# Flexboard.net
KiCad netlist of a schematic drawn in EAGLE
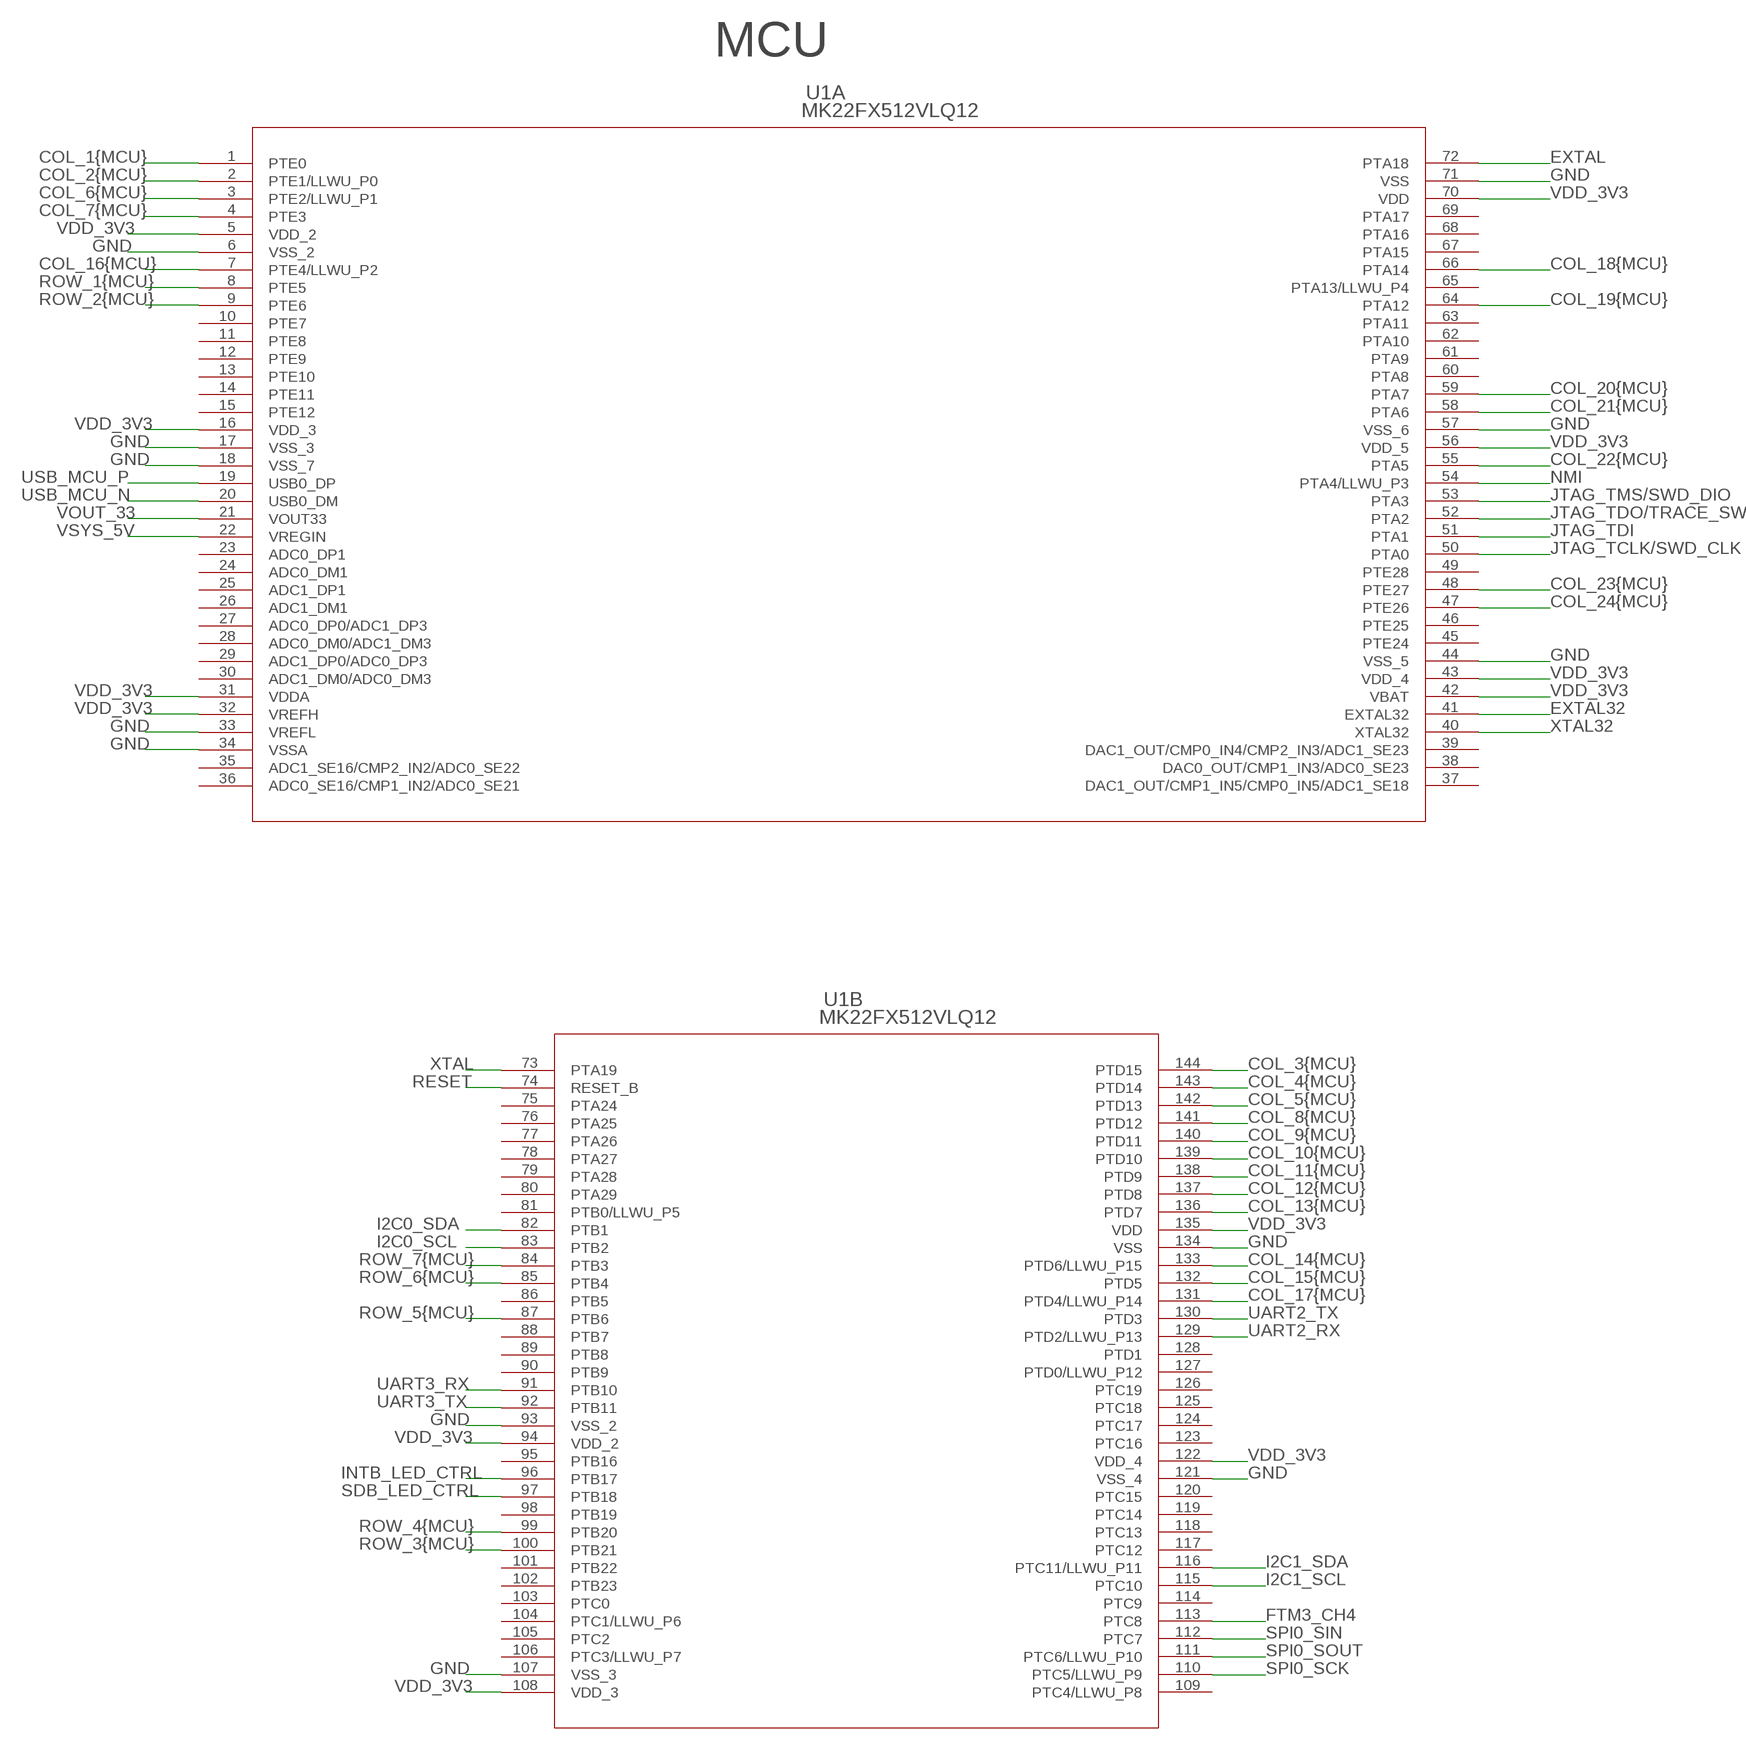
[diagram p0: schematic, sheet 1]
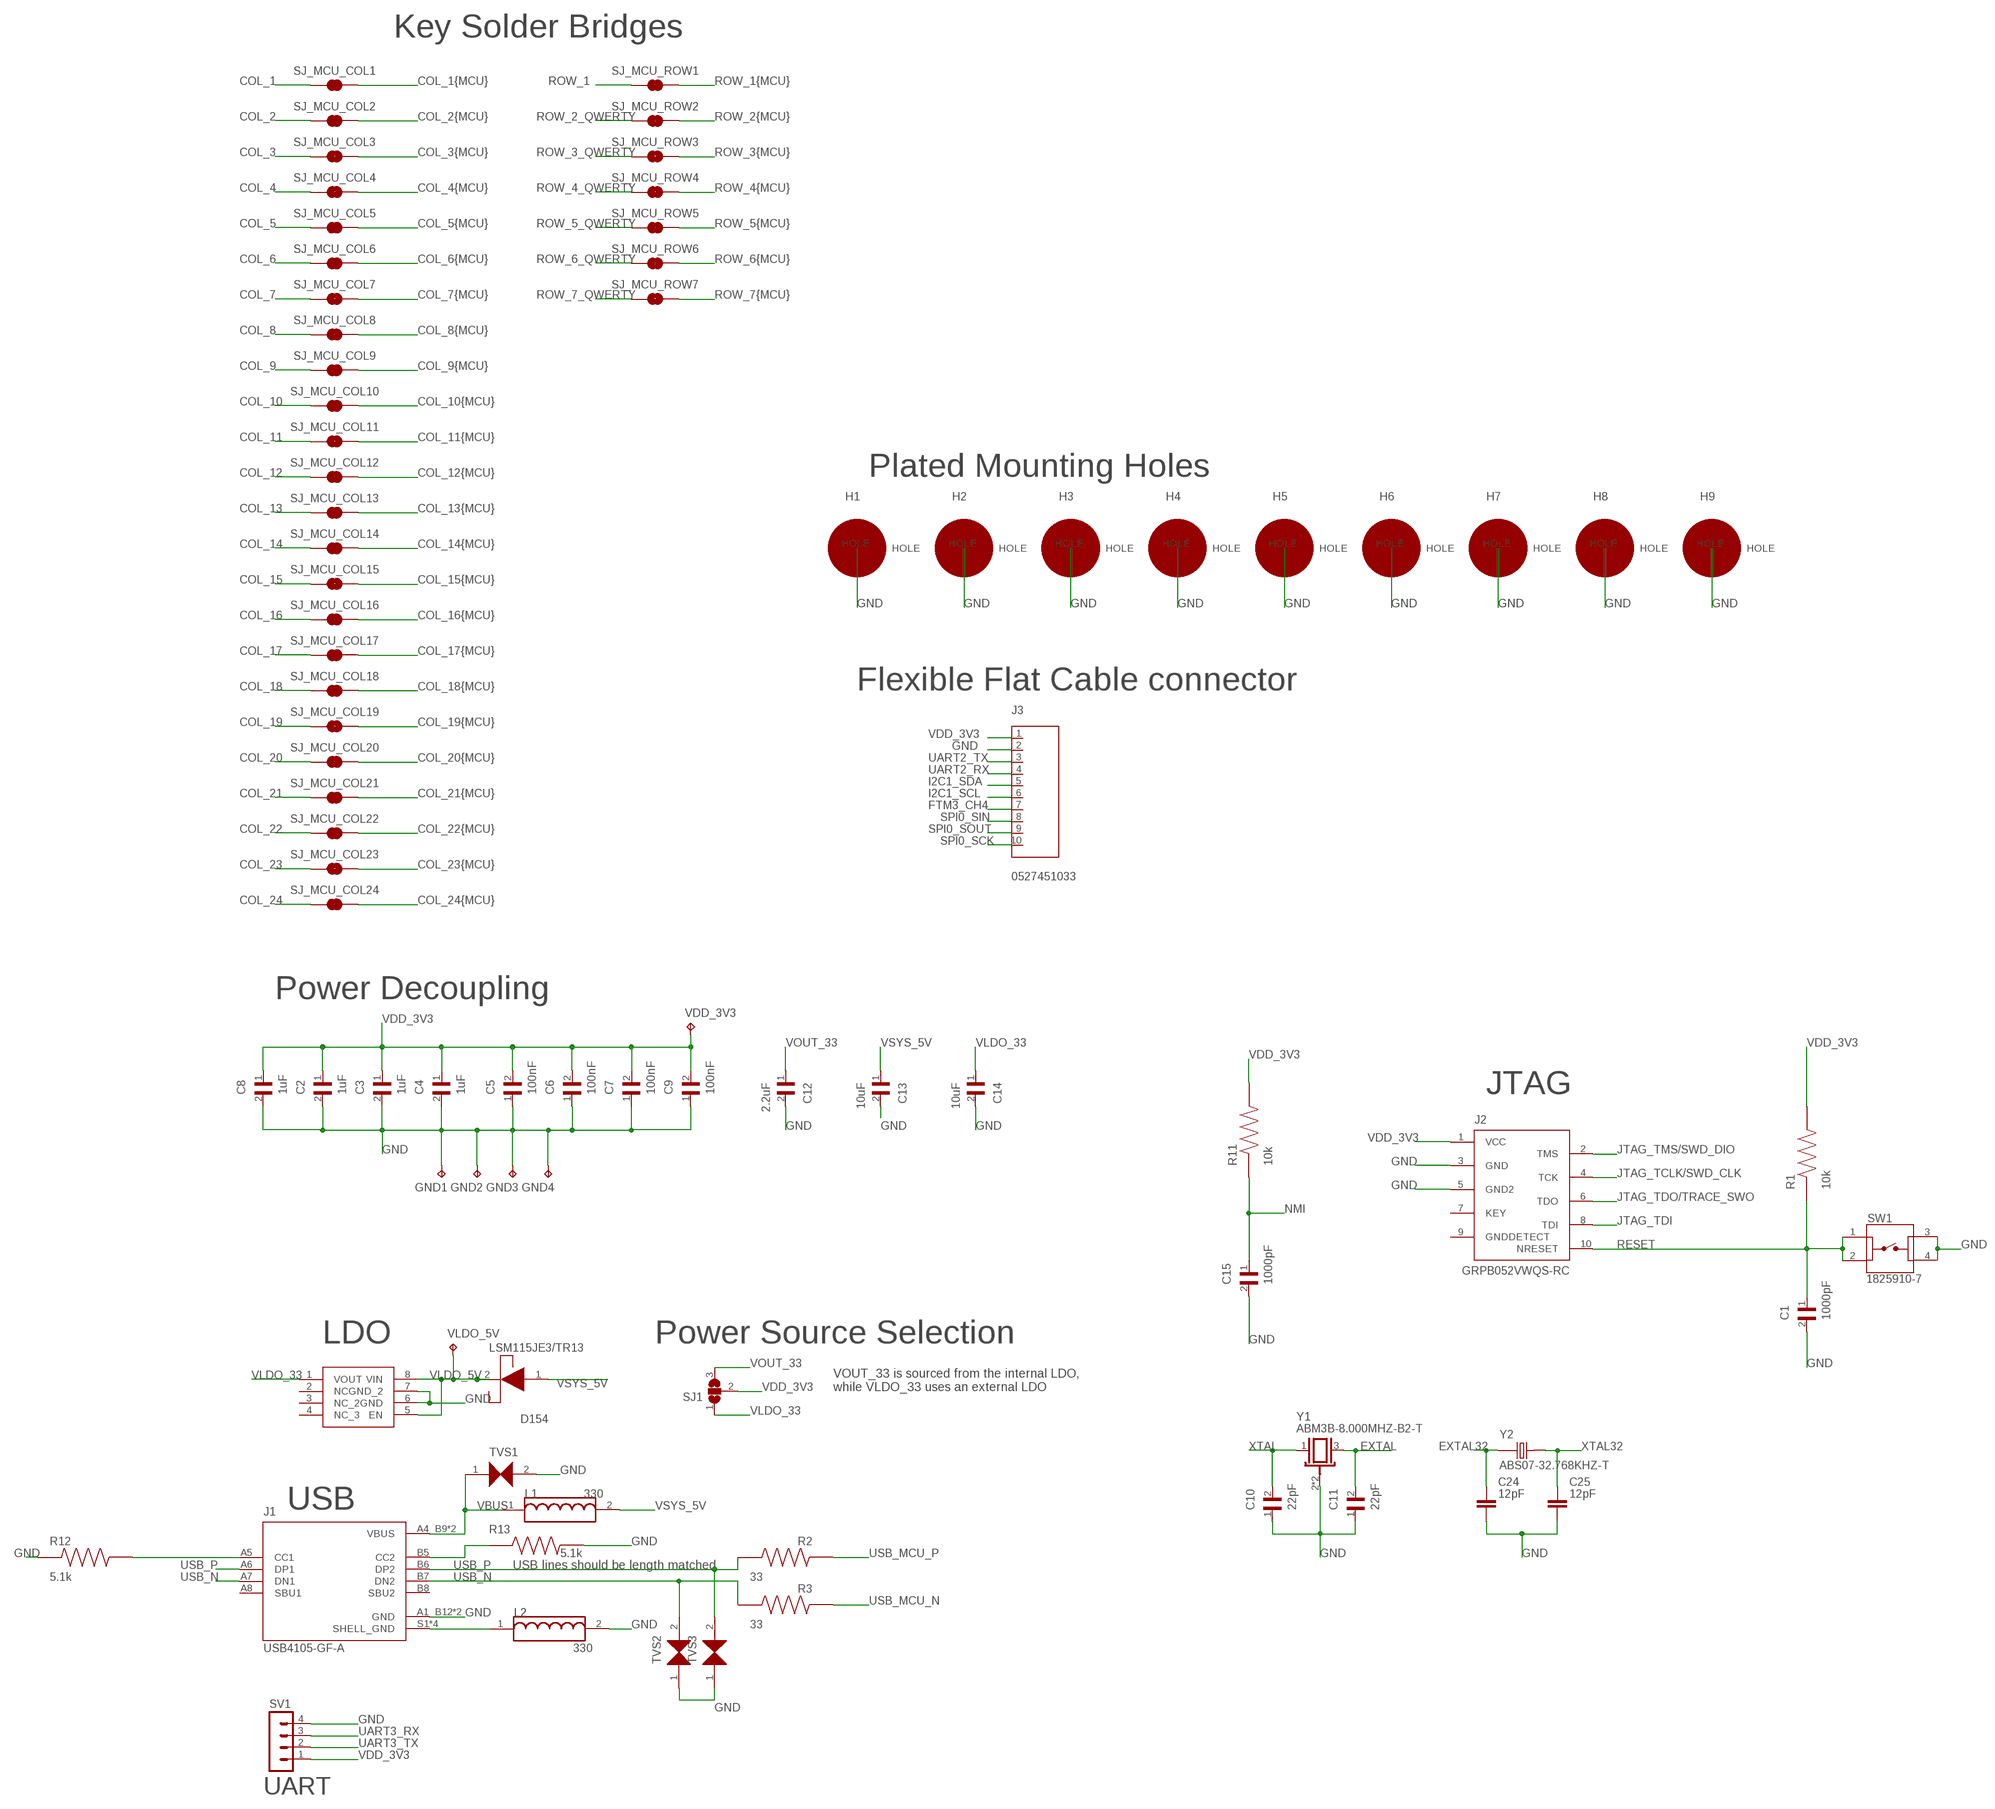
[diagram p1: schematic, sheet 2]
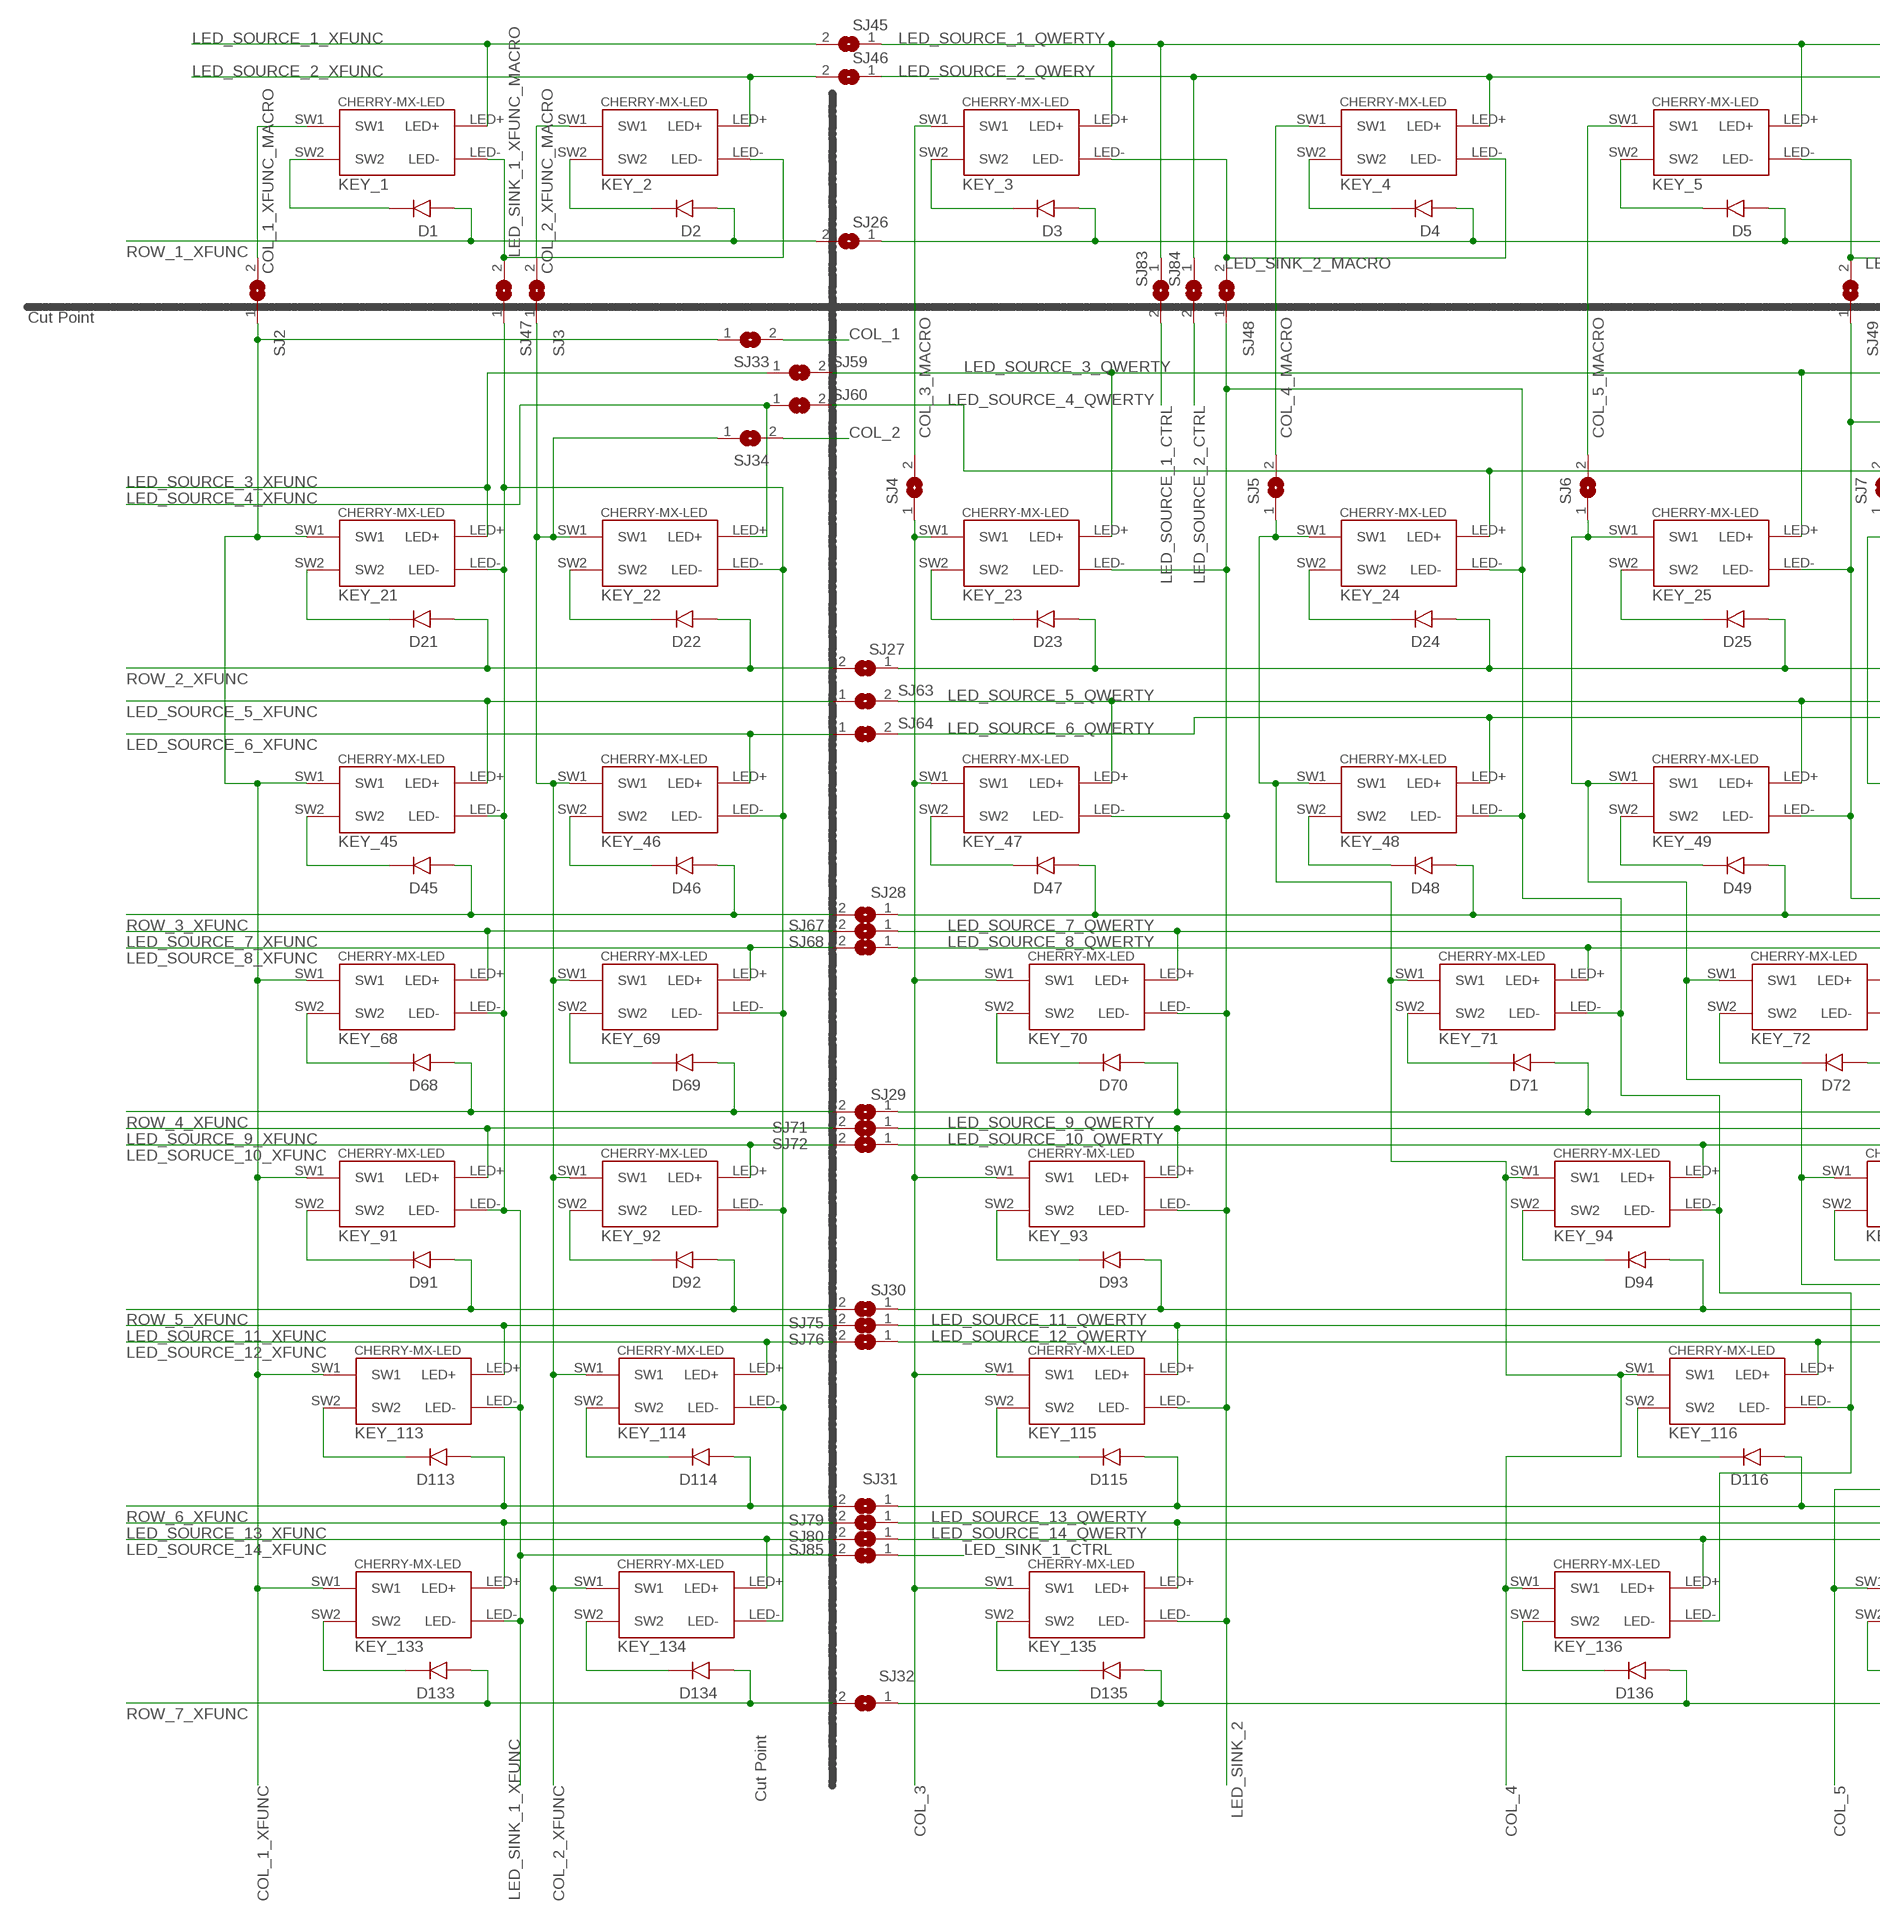
[diagram p2: schematic, sheet 3, part 1 of 3]
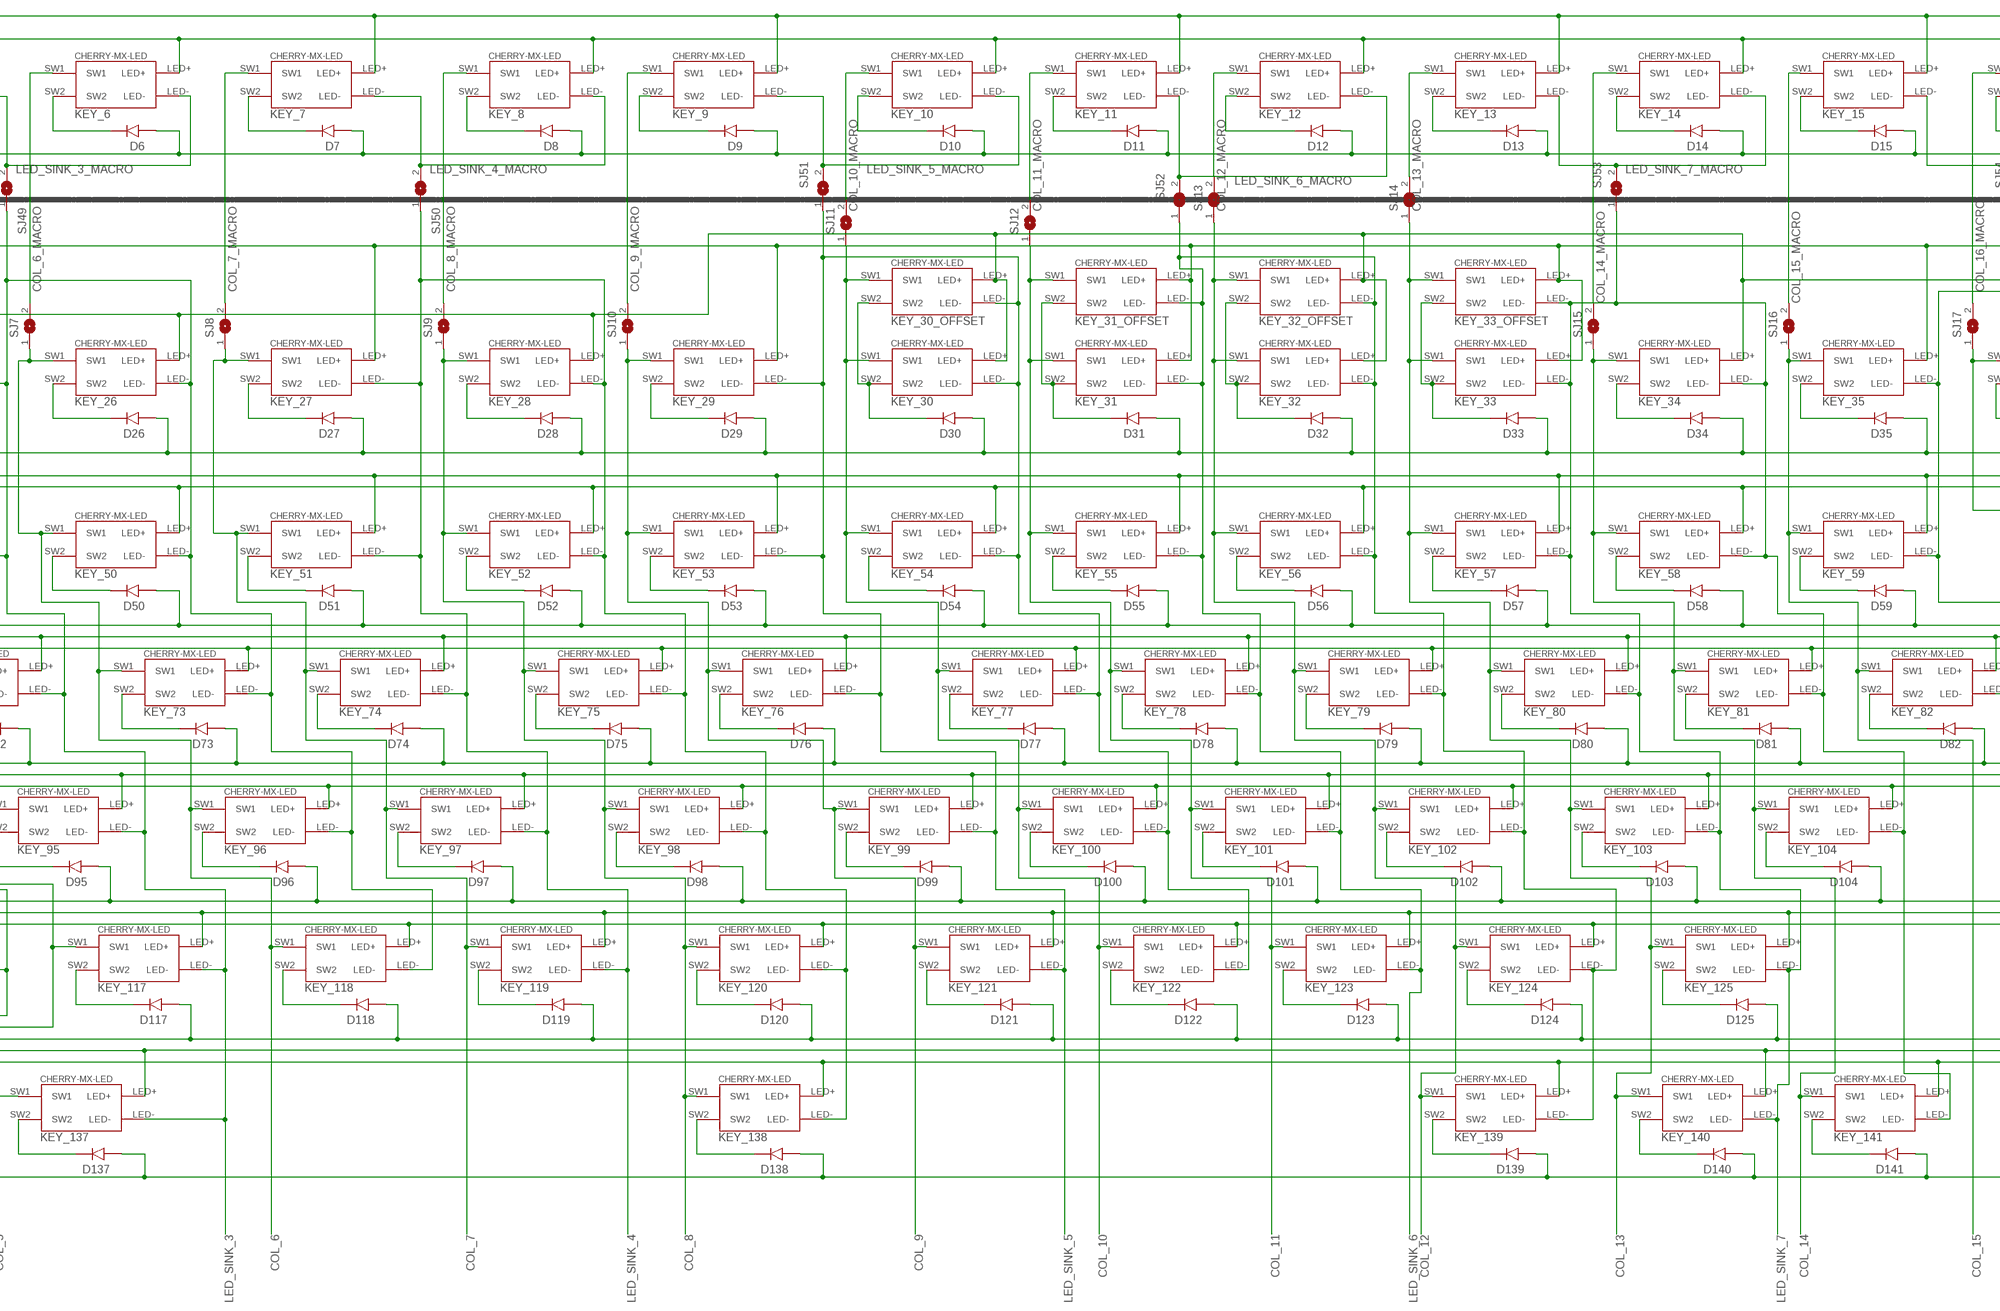
[diagram p3: schematic, sheet 3, part 2 of 3]
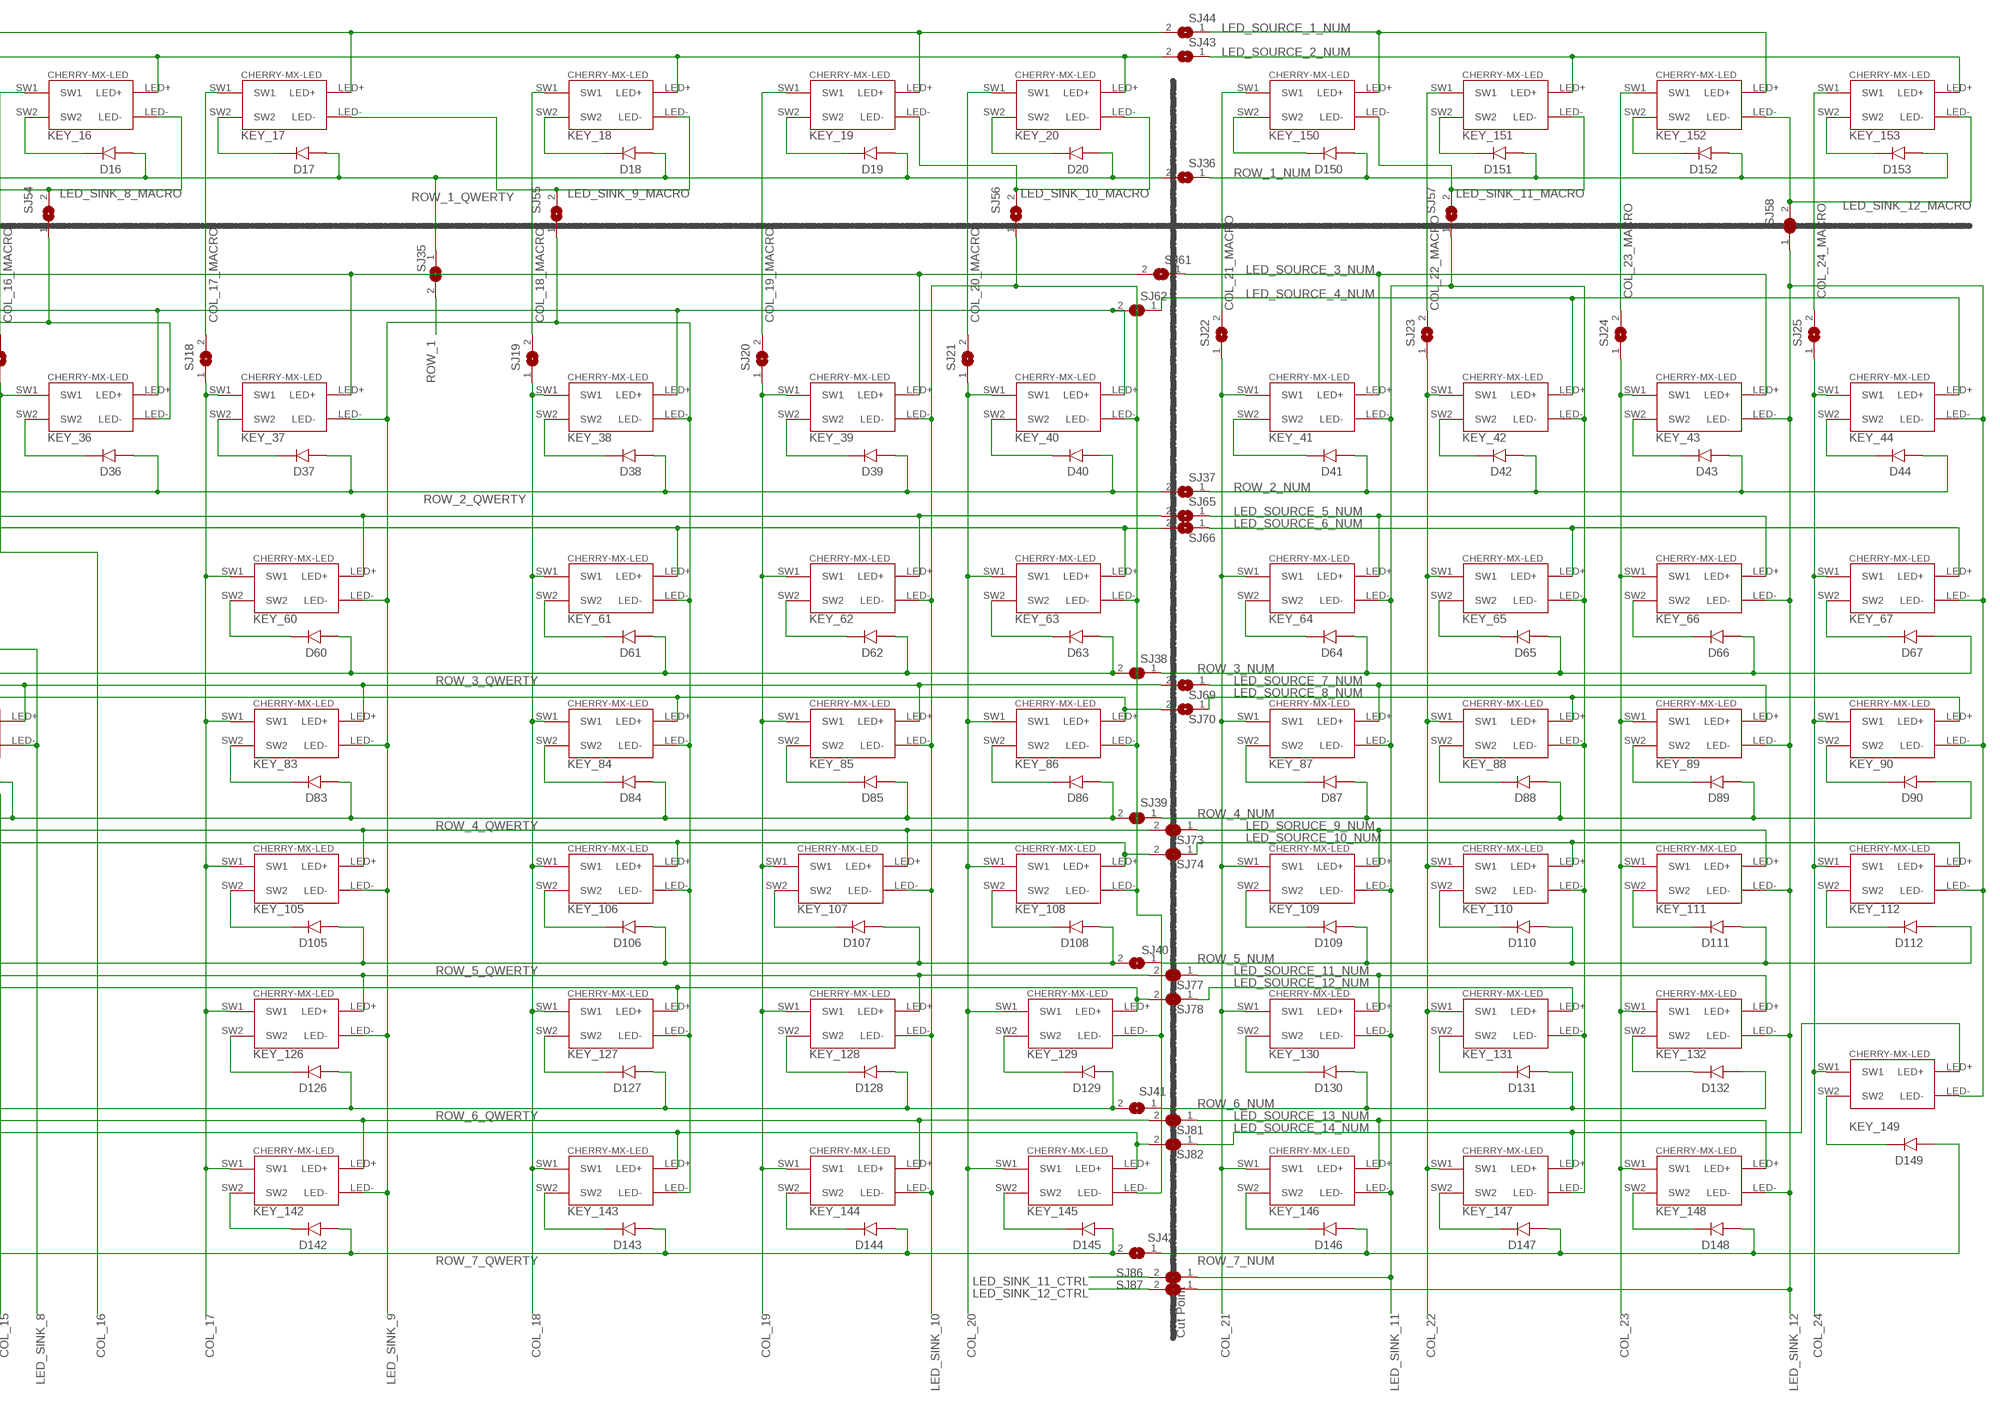
[diagram p4: schematic, sheet 3, part 3 of 3]
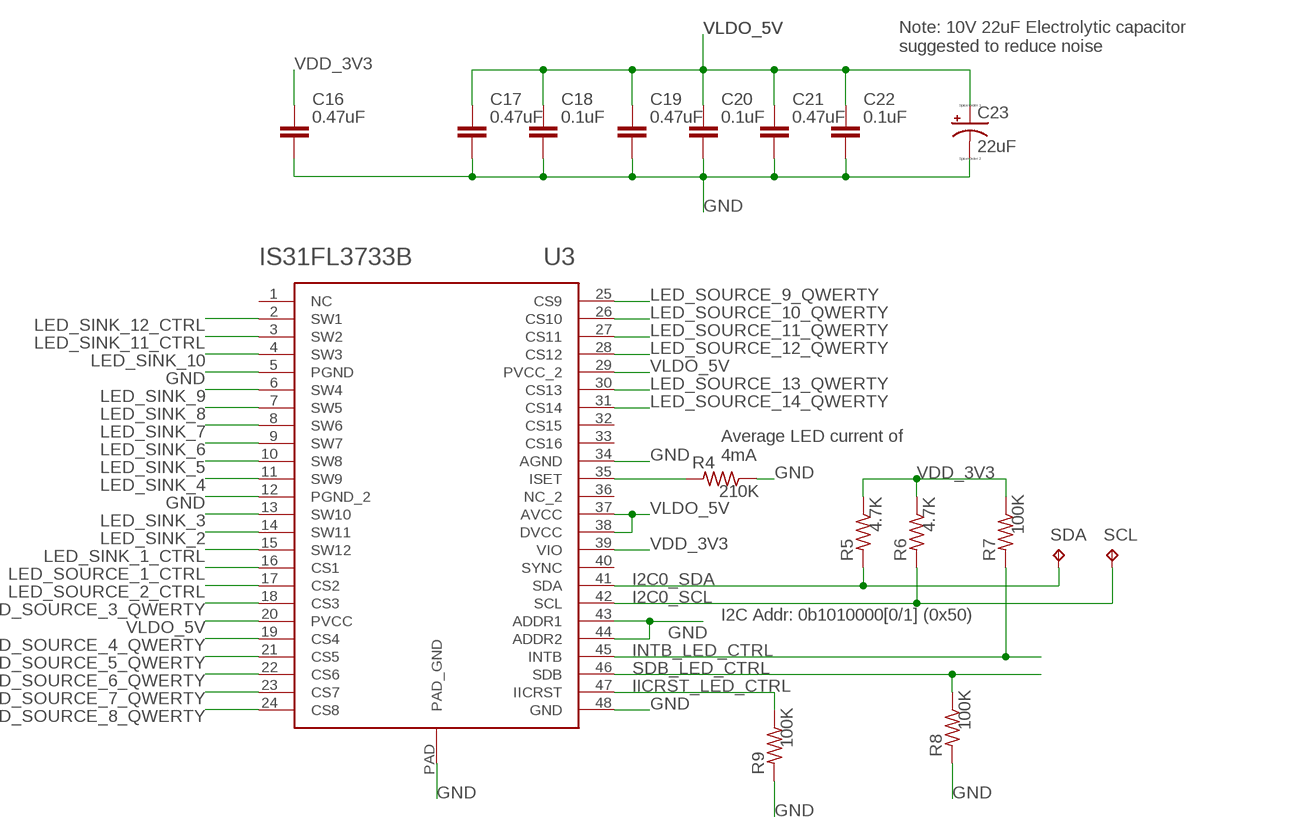
[diagram p5: schematic, sheet 4]

(export (version "E")
  (design (tool "Eeschema 10.0.6"))
  (components
    (comp (ref "C16")
      (value "0.47uF")
      (footprint "eagle-import:CAPC2012X110")
      (libsource (lib "eagle-import") (part "CCHIP-0805(2012-METRIC)_"))
    )
    (comp (ref "C17")
      (value "0.47uF")
      (footprint "eagle-import:CAPC2012X110")
      (libsource (lib "eagle-import") (part "CCHIP-0805(2012-METRIC)_"))
    )
    (comp (ref "C18")
      (value "0.1uF")
      (footprint "eagle-import:CAPC2012X110")
      (libsource (lib "eagle-import") (part "CCHIP-0805(2012-METRIC)_"))
    )
    (comp (ref "C19")
      (value "0.47uF")
      (footprint "eagle-import:CAPC2012X110")
      (libsource (lib "eagle-import") (part "CCHIP-0805(2012-METRIC)_"))
    )
    (comp (ref "C20")
      (value "0.1uF")
      (footprint "eagle-import:CAPC2012X110")
      (libsource (lib "eagle-import") (part "CCHIP-0805(2012-METRIC)_"))
    )
    (comp (ref "C21")
      (value "0.47uF")
      (footprint "eagle-import:CAPC2012X110")
      (libsource (lib "eagle-import") (part "CCHIP-0805(2012-METRIC)_"))
    )
    (comp (ref "C22")
      (value "0.1uF")
      (footprint "eagle-import:CAPC2012X110")
      (libsource (lib "eagle-import") (part "CCHIP-0805(2012-METRIC)_"))
    )
    (comp (ref "C23")
      (value "22uF")
      (footprint "eagle-import:860020672011")
      (libsource (lib "eagle-import") (part "860020672011"))
    )
    (comp (ref "R4")
      (value "210K")
      (footprint "eagle-import:RESC2012X65")
      (libsource (lib "eagle-import") (part "R-USCHIP-0805(2012-METRIC)_"))
    )
    (comp (ref "R5")
      (value "4.7K")
      (footprint "eagle-import:RESC2012X65")
      (libsource (lib "eagle-import") (part "R-USCHIP-0805(2012-METRIC)_"))
    )
    (comp (ref "R6")
      (value "4.7K")
      (footprint "eagle-import:RESC2012X65")
      (libsource (lib "eagle-import") (part "R-USCHIP-0805(2012-METRIC)_"))
    )
    (comp (ref "R7")
      (value "100K")
      (footprint "eagle-import:RESC2012X65")
      (libsource (lib "eagle-import") (part "R-USCHIP-0805(2012-METRIC)_"))
    )
    (comp (ref "R8")
      (value "100K")
      (footprint "eagle-import:RESC2012X65")
      (libsource (lib "eagle-import") (part "R-USCHIP-0805(2012-METRIC)_"))
    )
    (comp (ref "R9")
      (value "100K")
      (footprint "eagle-import:RESC2012X65")
      (libsource (lib "eagle-import") (part "R-USCHIP-0805(2012-METRIC)_"))
    )
    (comp (ref "SCL")
      (value "TPB2,54")
      (footprint "eagle-import:B2,54")
      (libsource (lib "eagle-import") (part "TPB2,54"))
    )
    (comp (ref "SDA")
      (value "TPB2,54")
      (footprint "eagle-import:B2,54")
      (libsource (lib "eagle-import") (part "TPB2,54"))
    )
    (comp (ref "U3")
      (value "IS31FL3733B-TQLS4")
      (footprint "eagle-import:IS31FL3733B-TQLS4")
      (libsource (lib "eagle-import") (part "IS31FL3733B-TQLS4"))
    )
    (comp (ref "C1")
      (value "1000pF")
      (footprint "eagle-import:CAPC3216X110N")
      (fields (field (name "MF") "KEMET") (field (name "MP") "C1206C102K1RACAUTO"))
      (libsource (lib "eagle-import") (part "C1206C102K1RACAUTO"))
    )
    (comp (ref "C2")
      (value "1uF")
      (footprint "eagle-import:CAPC3216X125N")
      (fields (field (name "MF") "Murata") (field (name "MP") "GCM31MR71H105KA55L"))
      (libsource (lib "eagle-import") (part "GCM31MR71H105KA55L"))
    )
    (comp (ref "C3")
      (value "1uF")
      (footprint "eagle-import:CAPC3216X125N")
      (fields (field (name "MF") "Murata") (field (name "MP") "GCM31MR71H105KA55L"))
      (libsource (lib "eagle-import") (part "GCM31MR71H105KA55L"))
    )
    (comp (ref "C4")
      (value "1uF")
      (footprint "eagle-import:CAPC3216X125N")
      (fields (field (name "MF") "Murata") (field (name "MP") "GCM31MR71H105KA55L"))
      (libsource (lib "eagle-import") (part "GCM31MR71H105KA55L"))
    )
    (comp (ref "C5")
      (value "100nF")
      (footprint "eagle-import:CAPC3216X88N")
      (fields (field (name "MF") "KEMET") (field (name "MP") "C1206C104K5RAC7800"))
      (libsource (lib "eagle-import") (part "C1206C104K5RAC7800"))
    )
    (comp (ref "C6")
      (value "100nF")
      (footprint "eagle-import:CAPC3216X88N")
      (fields (field (name "MF") "KEMET") (field (name "MP") "C1206C104K5RAC7800"))
      (libsource (lib "eagle-import") (part "C1206C104K5RAC7800"))
    )
    (comp (ref "C7")
      (value "100nF")
      (footprint "eagle-import:CAPC3216X88N")
      (fields (field (name "MF") "KEMET") (field (name "MP") "C1206C104K5RAC7800"))
      (libsource (lib "eagle-import") (part "C1206C104K5RAC7800"))
    )
    (comp (ref "C8")
      (value "1uF")
      (footprint "eagle-import:CAPC3216X125N")
      (fields (field (name "MF") "Murata") (field (name "MP") "GCM31MR71H105KA55L"))
      (libsource (lib "eagle-import") (part "GCM31MR71H105KA55L"))
    )
    (comp (ref "C9")
      (value "100nF")
      (footprint "eagle-import:CAPC3216X88N")
      (fields (field (name "MF") "KEMET") (field (name "MP") "C1206C104K5RAC7800"))
      (libsource (lib "eagle-import") (part "C1206C104K5RAC7800"))
    )
    (comp (ref "C10")
      (value "22pF")
      (footprint "eagle-import:CAPC3216X110N")
      (fields (field (name "MF") "KEMET") (field (name "MP") "C1206C220JGGAC7800"))
      (libsource (lib "eagle-import") (part "C1206C220JGGAC7800"))
    )
    (comp (ref "C11")
      (value "22pF")
      (footprint "eagle-import:CAPC3216X110N")
      (fields (field (name "MF") "KEMET") (field (name "MP") "C1206C220JGGAC7800"))
      (libsource (lib "eagle-import") (part "C1206C220JGGAC7800"))
    )
    (comp (ref "C12")
      (value "2.2uF")
      (footprint "eagle-import:CAPC3216X178N")
      (fields (field (name "MF") "AVX") (field (name "MP") "1206ZC225MAT2A"))
      (libsource (lib "eagle-import") (part "1206ZC225MAT2A"))
    )
    (comp (ref "C13")
      (value "10uF")
      (footprint "eagle-import:CAPC2012X145N")
      (fields
        (field (name "DIGI-KEY_PART_NUMBER") "490-10505-2-ND")
        (field (name "MF") "Murata")
        (field (name "MP") "GRM21BC8YA106ME11L")
      )
      (libsource (lib "eagle-import") (part "GRM21BC8YA106ME11L"))
    )
    (comp (ref "C14")
      (value "10uF")
      (footprint "eagle-import:CAPC2012X145N")
      (fields
        (field (name "DIGI-KEY_PART_NUMBER") "490-10505-2-ND")
        (field (name "MF") "Murata")
        (field (name "MP") "GRM21BC8YA106ME11L")
      )
      (libsource (lib "eagle-import") (part "GRM21BC8YA106ME11L"))
    )
    (comp (ref "C15")
      (value "1000pF")
      (footprint "eagle-import:CAPC3216X110N")
      (fields (field (name "MF") "KEMET") (field (name "MP") "C1206C102K1RACAUTO"))
      (libsource (lib "eagle-import") (part "C1206C102K1RACAUTO"))
    )
    (comp (ref "C24")
      (value "12pF")
      (footprint "eagle-import:CAPC2012X110")
      (libsource (lib "eagle-import") (part "CCHIP-0805(2012-METRIC)_"))
    )
    (comp (ref "C25")
      (value "12pF")
      (footprint "eagle-import:CAPC2012X110")
      (libsource (lib "eagle-import") (part "CCHIP-0805(2012-METRIC)_"))
    )
    (comp (ref "D154")
      (value "LSM115JE3/TR13")
      (footprint "eagle-import:LSM115JE3_TR13")
      (libsource (lib "eagle-import") (part "LSM115JE3/TR13"))
    )
    (comp (ref "GND1")
      (value "TPB2,54")
      (footprint "eagle-import:B2,54")
      (libsource (lib "eagle-import") (part "TPB2,54"))
    )
    (comp (ref "GND2")
      (value "TPB2,54")
      (footprint "eagle-import:B2,54")
      (libsource (lib "eagle-import") (part "TPB2,54"))
    )
    (comp (ref "GND3")
      (value "TPB2,54")
      (footprint "eagle-import:B2,54")
      (libsource (lib "eagle-import") (part "TPB2,54"))
    )
    (comp (ref "GND4")
      (value "TPB2,54")
      (footprint "eagle-import:B2,54")
      (libsource (lib "eagle-import") (part "TPB2,54"))
    )
    (comp (ref "H1")
      (value "PTH")
      (footprint "eagle-import:PTH")
      (libsource (lib "eagle-import") (part "PTH"))
    )
    (comp (ref "H2")
      (value "PTH")
      (footprint "eagle-import:PTH")
      (libsource (lib "eagle-import") (part "PTH"))
    )
    (comp (ref "H3")
      (value "PTH")
      (footprint "eagle-import:PTH")
      (libsource (lib "eagle-import") (part "PTH"))
    )
    (comp (ref "H4")
      (value "PTH")
      (footprint "eagle-import:PTH")
      (libsource (lib "eagle-import") (part "PTH"))
    )
    (comp (ref "H5")
      (value "PTH")
      (footprint "eagle-import:PTH")
      (libsource (lib "eagle-import") (part "PTH"))
    )
    (comp (ref "H6")
      (value "PTH")
      (footprint "eagle-import:PTH")
      (libsource (lib "eagle-import") (part "PTH"))
    )
    (comp (ref "H7")
      (value "PTH")
      (footprint "eagle-import:PTH")
      (libsource (lib "eagle-import") (part "PTH"))
    )
    (comp (ref "H8")
      (value "PTH")
      (footprint "eagle-import:PTH")
      (libsource (lib "eagle-import") (part "PTH"))
    )
    (comp (ref "H9")
      (value "PTH")
      (footprint "eagle-import:PTH")
      (libsource (lib "eagle-import") (part "PTH"))
    )
    (comp (ref "J1")
      (value "USB4105-GF-A")
      (footprint "eagle-import:GCT_USB4105-GF-A")
      (fields (field (name "MF") "GCT"))
      (libsource (lib "eagle-import") (part "USB4105-GF-A"))
    )
    (comp (ref "J2")
      (value "GRPB052VWQS-RC")
      (footprint "eagle-import:DEBUG")
      (fields (field (name "MF") "Sullins Connector"))
      (libsource (lib "eagle-import") (part "GRPB052VWQS-RC"))
    )
    (comp (ref "J3")
      (value "0527451033")
      (footprint "eagle-import:52745-1033")
      (libsource (lib "eagle-import") (part "0527451033"))
    )
    (comp (ref "L1")
      (value "330")
      (footprint "eagle-import:78285333")
      (libsource (lib "eagle-import") (part "782853331SMD"))
    )
    (comp (ref "L2")
      (value "330")
      (footprint "eagle-import:78285333")
      (libsource (lib "eagle-import") (part "782853331SMD"))
    )
    (comp (ref "R1")
      (value "10k")
      (footprint "eagle-import:RESC3115X65N")
      (fields
        (field (name "COMMENT") "2-2176344-5")
        (field (name "MF") "TE Connectivity")
        (field (name "MP") "CRGCQ1206J10K")
      )
      (libsource (lib "eagle-import") (part "CRGCQ1206J10K"))
    )
    (comp (ref "R2")
      (value "33")
      (footprint "eagle-import:RESC2012X65N")
      (fields
        (field (name "COMMENT") "1623198-1")
        (field (name "MF") "TE Connectivity")
        (field (name "MP") "CRG0805F33R")
      )
      (libsource (lib "eagle-import") (part "CRG0805F33R"))
    )
    (comp (ref "R3")
      (value "33")
      (footprint "eagle-import:RESC2012X65N")
      (fields
        (field (name "COMMENT") "1623198-1")
        (field (name "MF") "TE Connectivity")
        (field (name "MP") "CRG0805F33R")
      )
      (libsource (lib "eagle-import") (part "CRG0805F33R"))
    )
    (comp (ref "R11")
      (value "10k")
      (footprint "eagle-import:RESC3115X65N")
      (fields
        (field (name "COMMENT") "2-2176344-5")
        (field (name "MF") "TE Connectivity")
        (field (name "MP") "CRGCQ1206J10K")
      )
      (libsource (lib "eagle-import") (part "CRGCQ1206J10K"))
    )
    (comp (ref "R12")
      (value "5.1k")
      (footprint "eagle-import:RESC2012X60N")
      (fields (field (name "MF") "Stackpole Electronics Inc") (field (name "MP") "RNCP0805FTD20R0"))
      (libsource (lib "eagle-import") (part "RNCP0805FTD20R0"))
    )
    (comp (ref "R13")
      (value "5.1k")
      (footprint "eagle-import:RESC2012X60N")
      (fields (field (name "MF") "Stackpole Electronics Inc") (field (name "MP") "RNCP0805FTD20R0"))
      (libsource (lib "eagle-import") (part "RNCP0805FTD20R0"))
    )
    (comp (ref "SJ1")
      (value "SJ2W")
      (footprint "eagle-import:SJ_2")
      (libsource (lib "eagle-import") (part "SJ2W"))
    )
    (comp (ref "SJ_MCU_COL1")
      (value "JUMPER-SMT_2_NC_TRACE_NO-SILK")
      (footprint "eagle-import:SMT-JUMPER_2_NC_TRACE_NO-SILK")
      (libsource (lib "eagle-import") (part "JUMPER-SMT_2_NC_TRACE_NO-SILK"))
    )
    (comp (ref "SJ_MCU_COL2")
      (value "JUMPER-SMT_2_NC_TRACE_NO-SILK")
      (footprint "eagle-import:SMT-JUMPER_2_NC_TRACE_NO-SILK")
      (libsource (lib "eagle-import") (part "JUMPER-SMT_2_NC_TRACE_NO-SILK"))
    )
    (comp (ref "SJ_MCU_COL3")
      (value "JUMPER-SMT_2_NC_TRACE_NO-SILK")
      (footprint "eagle-import:SMT-JUMPER_2_NC_TRACE_NO-SILK")
      (libsource (lib "eagle-import") (part "JUMPER-SMT_2_NC_TRACE_NO-SILK"))
    )
    (comp (ref "SJ_MCU_COL4")
      (value "JUMPER-SMT_2_NC_TRACE_NO-SILK")
      (footprint "eagle-import:SMT-JUMPER_2_NC_TRACE_NO-SILK")
      (libsource (lib "eagle-import") (part "JUMPER-SMT_2_NC_TRACE_NO-SILK"))
    )
    (comp (ref "SJ_MCU_COL5")
      (value "JUMPER-SMT_2_NC_TRACE_NO-SILK")
      (footprint "eagle-import:SMT-JUMPER_2_NC_TRACE_NO-SILK")
      (libsource (lib "eagle-import") (part "JUMPER-SMT_2_NC_TRACE_NO-SILK"))
    )
    (comp (ref "SJ_MCU_COL6")
      (value "JUMPER-SMT_2_NC_TRACE_NO-SILK")
      (footprint "eagle-import:SMT-JUMPER_2_NC_TRACE_NO-SILK")
      (libsource (lib "eagle-import") (part "JUMPER-SMT_2_NC_TRACE_NO-SILK"))
    )
    (comp (ref "SJ_MCU_COL7")
      (value "JUMPER-SMT_2_NC_TRACE_NO-SILK")
      (footprint "eagle-import:SMT-JUMPER_2_NC_TRACE_NO-SILK")
      (libsource (lib "eagle-import") (part "JUMPER-SMT_2_NC_TRACE_NO-SILK"))
    )
    (comp (ref "SJ_MCU_COL8")
      (value "JUMPER-SMT_2_NC_TRACE_NO-SILK")
      (footprint "eagle-import:SMT-JUMPER_2_NC_TRACE_NO-SILK")
      (libsource (lib "eagle-import") (part "JUMPER-SMT_2_NC_TRACE_NO-SILK"))
    )
    (comp (ref "SJ_MCU_COL9")
      (value "JUMPER-SMT_2_NC_TRACE_NO-SILK")
      (footprint "eagle-import:SMT-JUMPER_2_NC_TRACE_NO-SILK")
      (libsource (lib "eagle-import") (part "JUMPER-SMT_2_NC_TRACE_NO-SILK"))
    )
    (comp (ref "SJ_MCU_COL10")
      (value "JUMPER-SMT_2_NC_TRACE_NO-SILK")
      (footprint "eagle-import:SMT-JUMPER_2_NC_TRACE_NO-SILK")
      (libsource (lib "eagle-import") (part "JUMPER-SMT_2_NC_TRACE_NO-SILK"))
    )
    (comp (ref "SJ_MCU_COL11")
      (value "JUMPER-SMT_2_NC_TRACE_NO-SILK")
      (footprint "eagle-import:SMT-JUMPER_2_NC_TRACE_NO-SILK")
      (libsource (lib "eagle-import") (part "JUMPER-SMT_2_NC_TRACE_NO-SILK"))
    )
    (comp (ref "SJ_MCU_COL12")
      (value "JUMPER-SMT_2_NC_TRACE_NO-SILK")
      (footprint "eagle-import:SMT-JUMPER_2_NC_TRACE_NO-SILK")
      (libsource (lib "eagle-import") (part "JUMPER-SMT_2_NC_TRACE_NO-SILK"))
    )
    (comp (ref "SJ_MCU_COL13")
      (value "JUMPER-SMT_2_NC_TRACE_NO-SILK")
      (footprint "eagle-import:SMT-JUMPER_2_NC_TRACE_NO-SILK")
      (libsource (lib "eagle-import") (part "JUMPER-SMT_2_NC_TRACE_NO-SILK"))
    )
    (comp (ref "SJ_MCU_COL14")
      (value "JUMPER-SMT_2_NC_TRACE_NO-SILK")
      (footprint "eagle-import:SMT-JUMPER_2_NC_TRACE_NO-SILK")
      (libsource (lib "eagle-import") (part "JUMPER-SMT_2_NC_TRACE_NO-SILK"))
    )
    (comp (ref "SJ_MCU_COL15")
      (value "JUMPER-SMT_2_NC_TRACE_NO-SILK")
      (footprint "eagle-import:SMT-JUMPER_2_NC_TRACE_NO-SILK")
      (libsource (lib "eagle-import") (part "JUMPER-SMT_2_NC_TRACE_NO-SILK"))
    )
    (comp (ref "SJ_MCU_COL16")
      (value "JUMPER-SMT_2_NC_TRACE_NO-SILK")
      (footprint "eagle-import:SMT-JUMPER_2_NC_TRACE_NO-SILK")
      (libsource (lib "eagle-import") (part "JUMPER-SMT_2_NC_TRACE_NO-SILK"))
    )
    (comp (ref "SJ_MCU_COL17")
      (value "JUMPER-SMT_2_NC_TRACE_NO-SILK")
      (footprint "eagle-import:SMT-JUMPER_2_NC_TRACE_NO-SILK")
      (libsource (lib "eagle-import") (part "JUMPER-SMT_2_NC_TRACE_NO-SILK"))
    )
    (comp (ref "SJ_MCU_COL18")
      (value "JUMPER-SMT_2_NC_TRACE_NO-SILK")
      (footprint "eagle-import:SMT-JUMPER_2_NC_TRACE_NO-SILK")
      (libsource (lib "eagle-import") (part "JUMPER-SMT_2_NC_TRACE_NO-SILK"))
    )
    (comp (ref "SJ_MCU_COL19")
      (value "JUMPER-SMT_2_NC_TRACE_NO-SILK")
      (footprint "eagle-import:SMT-JUMPER_2_NC_TRACE_NO-SILK")
      (libsource (lib "eagle-import") (part "JUMPER-SMT_2_NC_TRACE_NO-SILK"))
    )
    (comp (ref "SJ_MCU_COL20")
      (value "JUMPER-SMT_2_NC_TRACE_NO-SILK")
      (footprint "eagle-import:SMT-JUMPER_2_NC_TRACE_NO-SILK")
      (libsource (lib "eagle-import") (part "JUMPER-SMT_2_NC_TRACE_NO-SILK"))
    )
    (comp (ref "SJ_MCU_COL21")
      (value "JUMPER-SMT_2_NC_TRACE_NO-SILK")
      (footprint "eagle-import:SMT-JUMPER_2_NC_TRACE_NO-SILK")
      (libsource (lib "eagle-import") (part "JUMPER-SMT_2_NC_TRACE_NO-SILK"))
    )
    (comp (ref "SJ_MCU_COL22")
      (value "JUMPER-SMT_2_NC_TRACE_NO-SILK")
      (footprint "eagle-import:SMT-JUMPER_2_NC_TRACE_NO-SILK")
      (libsource (lib "eagle-import") (part "JUMPER-SMT_2_NC_TRACE_NO-SILK"))
    )
    (comp (ref "SJ_MCU_COL23")
      (value "JUMPER-SMT_2_NC_TRACE_NO-SILK")
      (footprint "eagle-import:SMT-JUMPER_2_NC_TRACE_NO-SILK")
      (libsource (lib "eagle-import") (part "JUMPER-SMT_2_NC_TRACE_NO-SILK"))
    )
    (comp (ref "SJ_MCU_COL24")
      (value "JUMPER-SMT_2_NC_TRACE_NO-SILK")
      (footprint "eagle-import:SMT-JUMPER_2_NC_TRACE_NO-SILK")
      (libsource (lib "eagle-import") (part "JUMPER-SMT_2_NC_TRACE_NO-SILK"))
    )
    (comp (ref "SJ_MCU_ROW1")
      (value "JUMPER-SMT_2_NC_TRACE_NO-SILK")
      (footprint "eagle-import:SMT-JUMPER_2_NC_TRACE_NO-SILK")
      (libsource (lib "eagle-import") (part "JUMPER-SMT_2_NC_TRACE_NO-SILK"))
    )
    (comp (ref "SJ_MCU_ROW2")
      (value "JUMPER-SMT_2_NC_TRACE_NO-SILK")
      (footprint "eagle-import:SMT-JUMPER_2_NC_TRACE_NO-SILK")
      (libsource (lib "eagle-import") (part "JUMPER-SMT_2_NC_TRACE_NO-SILK"))
    )
    (comp (ref "SJ_MCU_ROW3")
      (value "JUMPER-SMT_2_NC_TRACE_NO-SILK")
      (footprint "eagle-import:SMT-JUMPER_2_NC_TRACE_NO-SILK")
      (libsource (lib "eagle-import") (part "JUMPER-SMT_2_NC_TRACE_NO-SILK"))
    )
    (comp (ref "SJ_MCU_ROW4")
      (value "JUMPER-SMT_2_NC_TRACE_NO-SILK")
      (footprint "eagle-import:SMT-JUMPER_2_NC_TRACE_NO-SILK")
      (libsource (lib "eagle-import") (part "JUMPER-SMT_2_NC_TRACE_NO-SILK"))
    )
    (comp (ref "SJ_MCU_ROW5")
      (value "JUMPER-SMT_2_NC_TRACE_NO-SILK")
      (footprint "eagle-import:SMT-JUMPER_2_NC_TRACE_NO-SILK")
      (libsource (lib "eagle-import") (part "JUMPER-SMT_2_NC_TRACE_NO-SILK"))
    )
    (comp (ref "SJ_MCU_ROW6")
      (value "JUMPER-SMT_2_NC_TRACE_NO-SILK")
      (footprint "eagle-import:SMT-JUMPER_2_NC_TRACE_NO-SILK")
      (libsource (lib "eagle-import") (part "JUMPER-SMT_2_NC_TRACE_NO-SILK"))
    )
    (comp (ref "SJ_MCU_ROW7")
      (value "JUMPER-SMT_2_NC_TRACE_NO-SILK")
      (footprint "eagle-import:SMT-JUMPER_2_NC_TRACE_NO-SILK")
      (libsource (lib "eagle-import") (part "JUMPER-SMT_2_NC_TRACE_NO-SILK"))
    )
    (comp (ref "SV1")
      (value "MA04-1")
      (footprint "eagle-import:MA04-1")
      (libsource (lib "eagle-import") (part "MA04-1"))
    )
    (comp (ref "SW1")
      (value "1825910-7")
      (footprint "eagle-import:SW_1825910-7")
      (fields (field (name "MF") "TE Connectivity"))
      (libsource (lib "eagle-import") (part "1825910-7"))
    )
    (comp (ref "TVS1")
      (value "0603ESDA2-TR2")
      (footprint "eagle-import:0603ESDA2-TR2")
      (libsource (lib "eagle-import") (part "0603ESDA2-TR2"))
    )
    (comp (ref "TVS2")
      (value "0603ESDA2-TR2")
      (footprint "eagle-import:0603ESDA2-TR2")
      (libsource (lib "eagle-import") (part "0603ESDA2-TR2"))
    )
    (comp (ref "TVS3")
      (value "0603ESDA2-TR2")
      (footprint "eagle-import:0603ESDA2-TR2")
      (libsource (lib "eagle-import") (part "0603ESDA2-TR2"))
    )
    (comp (ref "U2")
      (value "AP2115M-3.3TRG1")
      (footprint "eagle-import:SOIC127P600X175-8N")
      (libsource (lib "eagle-import") (part "AP2115M-3.3TRG1"))
    )
    (comp (ref "VDD_3V3")
      (value "TPB2,54")
      (footprint "eagle-import:B2,54")
      (libsource (lib "eagle-import") (part "TPB2,54"))
    )
    (comp (ref "VLDO_5V")
      (value "TPB2,54")
      (footprint "eagle-import:B2,54")
      (libsource (lib "eagle-import") (part "TPB2,54"))
    )
    (comp (ref "Y1")
      (value "ABM3B-8.000MHZ-B2-T")
      (footprint "eagle-import:OSC_ABM3B-8.000MHZ-B2-T")
      (fields (field (name "MF") "Abracon"))
      (libsource (lib "eagle-import") (part "ABM3B-8.000MHZ-B2-T"))
    )
    (comp (ref "Y2")
      (value "ABS07-32.768KHZ-T")
      (footprint "eagle-import:XTAL_ABS07-32.768KHZ-T")
      (fields (field (name "MF") "Abracon"))
      (libsource (lib "eagle-import") (part "ABS07-32.768KHZ-T"))
    )
    (comp (ref "U1")
      (value "MK22FX512VLQ12")
      (footprint "eagle-import:LQFP-144_20X20X1.6")
      (fields (field (name "MANUFACTURER_PART_NUMBER") "MK22FX512AVLQ12"))
      (libsource (lib "eagle-import") (part "MK22FX512AVLQ12"))
    )
    (comp (ref "D1")
      (value "BAS16LT3G")
      (footprint "eagle-import:SOT95P240X111-3N")
      (fields (field (name "MF") "ON Semiconductor"))
      (libsource (lib "eagle-import") (part "BAS16LT3G"))
    )
    (comp (ref "D2")
      (value "BAS16LT3G")
      (footprint "eagle-import:SOT95P240X111-3N")
      (fields (field (name "MF") "ON Semiconductor"))
      (libsource (lib "eagle-import") (part "BAS16LT3G"))
    )
    (comp (ref "D3")
      (value "BAS16LT3G")
      (footprint "eagle-import:SOT95P240X111-3N")
      (fields (field (name "MF") "ON Semiconductor"))
      (libsource (lib "eagle-import") (part "BAS16LT3G"))
    )
    (comp (ref "D4")
      (value "BAS16LT3G")
      (footprint "eagle-import:SOT95P240X111-3N")
      (fields (field (name "MF") "ON Semiconductor"))
      (libsource (lib "eagle-import") (part "BAS16LT3G"))
    )
    (comp (ref "D5")
      (value "BAS16LT3G")
      (footprint "eagle-import:SOT95P240X111-3N")
      (fields (field (name "MF") "ON Semiconductor"))
      (libsource (lib "eagle-import") (part "BAS16LT3G"))
    )
    (comp (ref "D6")
      (value "BAS16LT3G")
      (footprint "eagle-import:SOT95P240X111-3N")
      (fields (field (name "MF") "ON Semiconductor"))
      (libsource (lib "eagle-import") (part "BAS16LT3G"))
    )
    (comp (ref "D7")
      (value "BAS16LT3G")
      (footprint "eagle-import:SOT95P240X111-3N")
      (fields (field (name "MF") "ON Semiconductor"))
      (libsource (lib "eagle-import") (part "BAS16LT3G"))
    )
    (comp (ref "D8")
      (value "BAS16LT3G")
      (footprint "eagle-import:SOT95P240X111-3N")
      (fields (field (name "MF") "ON Semiconductor"))
      (libsource (lib "eagle-import") (part "BAS16LT3G"))
    )
    (comp (ref "D9")
      (value "BAS16LT3G")
      (footprint "eagle-import:SOT95P240X111-3N")
      (fields (field (name "MF") "ON Semiconductor"))
      (libsource (lib "eagle-import") (part "BAS16LT3G"))
    )
    (comp (ref "D10")
      (value "BAS16LT3G")
      (footprint "eagle-import:SOT95P240X111-3N")
      (fields (field (name "MF") "ON Semiconductor"))
      (libsource (lib "eagle-import") (part "BAS16LT3G"))
    )
    (comp (ref "D11")
      (value "BAS16LT3G")
      (footprint "eagle-import:SOT95P240X111-3N")
      (fields (field (name "MF") "ON Semiconductor"))
      (libsource (lib "eagle-import") (part "BAS16LT3G"))
    )
    (comp (ref "D12")
      (value "BAS16LT3G")
      (footprint "eagle-import:SOT95P240X111-3N")
      (fields (field (name "MF") "ON Semiconductor"))
      (libsource (lib "eagle-import") (part "BAS16LT3G"))
    )
    (comp (ref "D13")
      (value "BAS16LT3G")
      (footprint "eagle-import:SOT95P240X111-3N")
      (fields (field (name "MF") "ON Semiconductor"))
      (libsource (lib "eagle-import") (part "BAS16LT3G"))
    )
    (comp (ref "D14")
      (value "BAS16LT3G")
      (footprint "eagle-import:SOT95P240X111-3N")
      (fields (field (name "MF") "ON Semiconductor"))
      (libsource (lib "eagle-import") (part "BAS16LT3G"))
    )
    (comp (ref "D15")
      (value "BAS16LT3G")
      (footprint "eagle-import:SOT95P240X111-3N")
      (fields (field (name "MF") "ON Semiconductor"))
      (libsource (lib "eagle-import") (part "BAS16LT3G"))
    )
    (comp (ref "D16")
      (value "BAS16LT3G")
      (footprint "eagle-import:SOT95P240X111-3N")
      (fields (field (name "MF") "ON Semiconductor"))
      (libsource (lib "eagle-import") (part "BAS16LT3G"))
    )
    (comp (ref "D17")
      (value "BAS16LT3G")
      (footprint "eagle-import:SOT95P240X111-3N")
      (fields (field (name "MF") "ON Semiconductor"))
      (libsource (lib "eagle-import") (part "BAS16LT3G"))
    )
    (comp (ref "D18")
      (value "BAS16LT3G")
      (footprint "eagle-import:SOT95P240X111-3N")
      (fields (field (name "MF") "ON Semiconductor"))
      (libsource (lib "eagle-import") (part "BAS16LT3G"))
    )
    (comp (ref "D19")
      (value "BAS16LT3G")
      (footprint "eagle-import:SOT95P240X111-3N")
      (fields (field (name "MF") "ON Semiconductor"))
      (libsource (lib "eagle-import") (part "BAS16LT3G"))
    )
    (comp (ref "D20")
      (value "BAS16LT3G")
      (footprint "eagle-import:SOT95P240X111-3N")
      (fields (field (name "MF") "ON Semiconductor"))
      (libsource (lib "eagle-import") (part "BAS16LT3G"))
    )
    (comp (ref "D21")
      (value "BAS16LT3G")
      (footprint "eagle-import:SOT95P240X111-3N")
      (fields (field (name "MF") "ON Semiconductor"))
      (libsource (lib "eagle-import") (part "BAS16LT3G"))
    )
    (comp (ref "D22")
      (value "BAS16LT3G")
      (footprint "eagle-import:SOT95P240X111-3N")
      (fields (field (name "MF") "ON Semiconductor"))
      (libsource (lib "eagle-import") (part "BAS16LT3G"))
    )
    (comp (ref "D23")
      (value "BAS16LT3G")
      (footprint "eagle-import:SOT95P240X111-3N")
      (fields (field (name "MF") "ON Semiconductor"))
      (libsource (lib "eagle-import") (part "BAS16LT3G"))
    )
    (comp (ref "D24")
      (value "BAS16LT3G")
      (footprint "eagle-import:SOT95P240X111-3N")
      (fields (field (name "MF") "ON Semiconductor"))
      (libsource (lib "eagle-import") (part "BAS16LT3G"))
    )
    (comp (ref "D25")
      (value "BAS16LT3G")
      (footprint "eagle-import:SOT95P240X111-3N")
      (fields (field (name "MF") "ON Semiconductor"))
      (libsource (lib "eagle-import") (part "BAS16LT3G"))
    )
    (comp (ref "D26")
      (value "BAS16LT3G")
      (footprint "eagle-import:SOT95P240X111-3N")
      (fields (field (name "MF") "ON Semiconductor"))
      (libsource (lib "eagle-import") (part "BAS16LT3G"))
    )
    (comp (ref "D27")
      (value "BAS16LT3G")
      (footprint "eagle-import:SOT95P240X111-3N")
      (fields (field (name "MF") "ON Semiconductor"))
      (libsource (lib "eagle-import") (part "BAS16LT3G"))
    )
    (comp (ref "D28")
      (value "BAS16LT3G")
      (footprint "eagle-import:SOT95P240X111-3N")
      (fields (field (name "MF") "ON Semiconductor"))
      (libsource (lib "eagle-import") (part "BAS16LT3G"))
    )
    (comp (ref "D29")
      (value "BAS16LT3G")
      (footprint "eagle-import:SOT95P240X111-3N")
      (fields (field (name "MF") "ON Semiconductor"))
      (libsource (lib "eagle-import") (part "BAS16LT3G"))
    )
    (comp (ref "D30")
      (value "BAS16LT3G")
      (footprint "eagle-import:SOT95P240X111-3N")
      (fields (field (name "MF") "ON Semiconductor"))
      (libsource (lib "eagle-import") (part "BAS16LT3G"))
    )
    (comp (ref "D31")
      (value "BAS16LT3G")
      (footprint "eagle-import:SOT95P240X111-3N")
      (fields (field (name "MF") "ON Semiconductor"))
      (libsource (lib "eagle-import") (part "BAS16LT3G"))
    )
    (comp (ref "D32")
      (value "BAS16LT3G")
      (footprint "eagle-import:SOT95P240X111-3N")
      (fields (field (name "MF") "ON Semiconductor"))
      (libsource (lib "eagle-import") (part "BAS16LT3G"))
    )
    (comp (ref "D33")
      (value "BAS16LT3G")
      (footprint "eagle-import:SOT95P240X111-3N")
      (fields (field (name "MF") "ON Semiconductor"))
      (libsource (lib "eagle-import") (part "BAS16LT3G"))
    )
    (comp (ref "D34")
      (value "BAS16LT3G")
      (footprint "eagle-import:SOT95P240X111-3N")
      (fields (field (name "MF") "ON Semiconductor"))
      (libsource (lib "eagle-import") (part "BAS16LT3G"))
    )
    (comp (ref "D35")
      (value "BAS16LT3G")
      (footprint "eagle-import:SOT95P240X111-3N")
      (fields (field (name "MF") "ON Semiconductor"))
      (libsource (lib "eagle-import") (part "BAS16LT3G"))
    )
    (comp (ref "D36")
      (value "BAS16LT3G")
      (footprint "eagle-import:SOT95P240X111-3N")
      (fields (field (name "MF") "ON Semiconductor"))
      (libsource (lib "eagle-import") (part "BAS16LT3G"))
    )
    (comp (ref "D37")
      (value "BAS16LT3G")
      (footprint "eagle-import:SOT95P240X111-3N")
      (fields (field (name "MF") "ON Semiconductor"))
      (libsource (lib "eagle-import") (part "BAS16LT3G"))
    )
    (comp (ref "D38")
      (value "BAS16LT3G")
      (footprint "eagle-import:SOT95P240X111-3N")
      (fields (field (name "MF") "ON Semiconductor"))
      (libsource (lib "eagle-import") (part "BAS16LT3G"))
    )
    (comp (ref "D39")
      (value "BAS16LT3G")
      (footprint "eagle-import:SOT95P240X111-3N")
      (fields (field (name "MF") "ON Semiconductor"))
      (libsource (lib "eagle-import") (part "BAS16LT3G"))
    )
    (comp (ref "D40")
      (value "BAS16LT3G")
      (footprint "eagle-import:SOT95P240X111-3N")
      (fields (field (name "MF") "ON Semiconductor"))
      (libsource (lib "eagle-import") (part "BAS16LT3G"))
    )
    (comp (ref "D41")
      (value "BAS16LT3G")
      (footprint "eagle-import:SOT95P240X111-3N")
      (fields (field (name "MF") "ON Semiconductor"))
      (libsource (lib "eagle-import") (part "BAS16LT3G"))
    )
    (comp (ref "D42")
      (value "BAS16LT3G")
      (footprint "eagle-import:SOT95P240X111-3N")
      (fields (field (name "MF") "ON Semiconductor"))
      (libsource (lib "eagle-import") (part "BAS16LT3G"))
    )
    (comp (ref "D43")
      (value "BAS16LT3G")
      (footprint "eagle-import:SOT95P240X111-3N")
      (fields (field (name "MF") "ON Semiconductor"))
      (libsource (lib "eagle-import") (part "BAS16LT3G"))
    )
    (comp (ref "D44")
      (value "BAS16LT3G")
      (footprint "eagle-import:SOT95P240X111-3N")
      (fields (field (name "MF") "ON Semiconductor"))
      (libsource (lib "eagle-import") (part "BAS16LT3G"))
    )
    (comp (ref "D45")
      (value "BAS16LT3G")
      (footprint "eagle-import:SOT95P240X111-3N")
      (fields (field (name "MF") "ON Semiconductor"))
      (libsource (lib "eagle-import") (part "BAS16LT3G"))
    )
    (comp (ref "D46")
      (value "BAS16LT3G")
      (footprint "eagle-import:SOT95P240X111-3N")
      (fields (field (name "MF") "ON Semiconductor"))
      (libsource (lib "eagle-import") (part "BAS16LT3G"))
    )
    (comp (ref "D47")
      (value "BAS16LT3G")
      (footprint "eagle-import:SOT95P240X111-3N")
      (fields (field (name "MF") "ON Semiconductor"))
      (libsource (lib "eagle-import") (part "BAS16LT3G"))
    )
    (comp (ref "D48")
      (value "BAS16LT3G")
      (footprint "eagle-import:SOT95P240X111-3N")
      (fields (field (name "MF") "ON Semiconductor"))
      (libsource (lib "eagle-import") (part "BAS16LT3G"))
    )
    (comp (ref "D49")
      (value "BAS16LT3G")
      (footprint "eagle-import:SOT95P240X111-3N")
      (fields (field (name "MF") "ON Semiconductor"))
      (libsource (lib "eagle-import") (part "BAS16LT3G"))
    )
    (comp (ref "D50")
      (value "BAS16LT3G")
      (footprint "eagle-import:SOT95P240X111-3N")
      (fields (field (name "MF") "ON Semiconductor"))
      (libsource (lib "eagle-import") (part "BAS16LT3G"))
    )
    (comp (ref "D51")
      (value "BAS16LT3G")
      (footprint "eagle-import:SOT95P240X111-3N")
      (fields (field (name "MF") "ON Semiconductor"))
      (libsource (lib "eagle-import") (part "BAS16LT3G"))
    )
    (comp (ref "D52")
      (value "BAS16LT3G")
      (footprint "eagle-import:SOT95P240X111-3N")
      (fields (field (name "MF") "ON Semiconductor"))
      (libsource (lib "eagle-import") (part "BAS16LT3G"))
    )
    (comp (ref "D53")
      (value "BAS16LT3G")
      (footprint "eagle-import:SOT95P240X111-3N")
      (fields (field (name "MF") "ON Semiconductor"))
      (libsource (lib "eagle-import") (part "BAS16LT3G"))
    )
    (comp (ref "D54")
      (value "BAS16LT3G")
      (footprint "eagle-import:SOT95P240X111-3N")
      (fields (field (name "MF") "ON Semiconductor"))
      (libsource (lib "eagle-import") (part "BAS16LT3G"))
    )
    (comp (ref "D55")
      (value "BAS16LT3G")
      (footprint "eagle-import:SOT95P240X111-3N")
      (fields (field (name "MF") "ON Semiconductor"))
      (libsource (lib "eagle-import") (part "BAS16LT3G"))
    )
    (comp (ref "D56")
      (value "BAS16LT3G")
      (footprint "eagle-import:SOT95P240X111-3N")
      (fields (field (name "MF") "ON Semiconductor"))
      (libsource (lib "eagle-import") (part "BAS16LT3G"))
    )
    (comp (ref "D57")
      (value "BAS16LT3G")
      (footprint "eagle-import:SOT95P240X111-3N")
      (fields (field (name "MF") "ON Semiconductor"))
      (libsource (lib "eagle-import") (part "BAS16LT3G"))
    )
    (comp (ref "D58")
      (value "BAS16LT3G")
      (footprint "eagle-import:SOT95P240X111-3N")
      (fields (field (name "MF") "ON Semiconductor"))
      (libsource (lib "eagle-import") (part "BAS16LT3G"))
    )
    (comp (ref "D59")
      (value "BAS16LT3G")
      (footprint "eagle-import:SOT95P240X111-3N")
      (fields (field (name "MF") "ON Semiconductor"))
      (libsource (lib "eagle-import") (part "BAS16LT3G"))
    )
    (comp (ref "D60")
      (value "BAS16LT3G")
      (footprint "eagle-import:SOT95P240X111-3N")
      (fields (field (name "MF") "ON Semiconductor"))
      (libsource (lib "eagle-import") (part "BAS16LT3G"))
    )
    (comp (ref "D61")
      (value "BAS16LT3G")
      (footprint "eagle-import:SOT95P240X111-3N")
      (fields (field (name "MF") "ON Semiconductor"))
      (libsource (lib "eagle-import") (part "BAS16LT3G"))
    )
    (comp (ref "D62")
      (value "BAS16LT3G")
      (footprint "eagle-import:SOT95P240X111-3N")
      (fields (field (name "MF") "ON Semiconductor"))
      (libsource (lib "eagle-import") (part "BAS16LT3G"))
    )
    (comp (ref "D63")
      (value "BAS16LT3G")
      (footprint "eagle-import:SOT95P240X111-3N")
      (fields (field (name "MF") "ON Semiconductor"))
      (libsource (lib "eagle-import") (part "BAS16LT3G"))
    )
    (comp (ref "D64")
      (value "BAS16LT3G")
      (footprint "eagle-import:SOT95P240X111-3N")
      (fields (field (name "MF") "ON Semiconductor"))
      (libsource (lib "eagle-import") (part "BAS16LT3G"))
    )
    (comp (ref "D65")
      (value "BAS16LT3G")
      (footprint "eagle-import:SOT95P240X111-3N")
      (fields (field (name "MF") "ON Semiconductor"))
      (libsource (lib "eagle-import") (part "BAS16LT3G"))
    )
    (comp (ref "D66")
      (value "BAS16LT3G")
      (footprint "eagle-import:SOT95P240X111-3N")
      (fields (field (name "MF") "ON Semiconductor"))
      (libsource (lib "eagle-import") (part "BAS16LT3G"))
    )
    (comp (ref "D67")
      (value "BAS16LT3G")
      (footprint "eagle-import:SOT95P240X111-3N")
      (fields (field (name "MF") "ON Semiconductor"))
      (libsource (lib "eagle-import") (part "BAS16LT3G"))
    )
    (comp (ref "D68")
      (value "BAS16LT3G")
      (footprint "eagle-import:SOT95P240X111-3N")
      (fields (field (name "MF") "ON Semiconductor"))
      (libsource (lib "eagle-import") (part "BAS16LT3G"))
    )
    (comp (ref "D69")
      (value "BAS16LT3G")
      (footprint "eagle-import:SOT95P240X111-3N")
      (fields (field (name "MF") "ON Semiconductor"))
      (libsource (lib "eagle-import") (part "BAS16LT3G"))
    )
    (comp (ref "D70")
      (value "BAS16LT3G")
      (footprint "eagle-import:SOT95P240X111-3N")
      (fields (field (name "MF") "ON Semiconductor"))
      (libsource (lib "eagle-import") (part "BAS16LT3G"))
    )
    (comp (ref "D71")
      (value "BAS16LT3G")
      (footprint "eagle-import:SOT95P240X111-3N")
      (fields (field (name "MF") "ON Semiconductor"))
      (libsource (lib "eagle-import") (part "BAS16LT3G"))
    )
    (comp (ref "D72")
      (value "BAS16LT3G")
      (footprint "eagle-import:SOT95P240X111-3N")
      (fields (field (name "MF") "ON Semiconductor"))
      (libsource (lib "eagle-import") (part "BAS16LT3G"))
    )
    (comp (ref "D73")
      (value "BAS16LT3G")
      (footprint "eagle-import:SOT95P240X111-3N")
      (fields (field (name "MF") "ON Semiconductor"))
      (libsource (lib "eagle-import") (part "BAS16LT3G"))
    )
    (comp (ref "D74")
      (value "BAS16LT3G")
      (footprint "eagle-import:SOT95P240X111-3N")
      (fields (field (name "MF") "ON Semiconductor"))
      (libsource (lib "eagle-import") (part "BAS16LT3G"))
    )
    (comp (ref "D75")
      (value "BAS16LT3G")
      (footprint "eagle-import:SOT95P240X111-3N")
      (fields (field (name "MF") "ON Semiconductor"))
      (libsource (lib "eagle-import") (part "BAS16LT3G"))
    )
    (comp (ref "D76")
      (value "BAS16LT3G")
      (footprint "eagle-import:SOT95P240X111-3N")
      (fields (field (name "MF") "ON Semiconductor"))
      (libsource (lib "eagle-import") (part "BAS16LT3G"))
    )
    (comp (ref "D77")
      (value "BAS16LT3G")
      (footprint "eagle-import:SOT95P240X111-3N")
      (fields (field (name "MF") "ON Semiconductor"))
      (libsource (lib "eagle-import") (part "BAS16LT3G"))
    )
    (comp (ref "D78")
      (value "BAS16LT3G")
      (footprint "eagle-import:SOT95P240X111-3N")
      (fields (field (name "MF") "ON Semiconductor"))
      (libsource (lib "eagle-import") (part "BAS16LT3G"))
    )
    (comp (ref "D79")
      (value "BAS16LT3G")
      (footprint "eagle-import:SOT95P240X111-3N")
      (fields (field (name "MF") "ON Semiconductor"))
      (libsource (lib "eagle-import") (part "BAS16LT3G"))
    )
    (comp (ref "D80")
      (value "BAS16LT3G")
      (footprint "eagle-import:SOT95P240X111-3N")
      (fields (field (name "MF") "ON Semiconductor"))
      (libsource (lib "eagle-import") (part "BAS16LT3G"))
    )
    (comp (ref "D81")
      (value "BAS16LT3G")
      (footprint "eagle-import:SOT95P240X111-3N")
      (fields (field (name "MF") "ON Semiconductor"))
      (libsource (lib "eagle-import") (part "BAS16LT3G"))
    )
    (comp (ref "D82")
      (value "BAS16LT3G")
      (footprint "eagle-import:SOT95P240X111-3N")
      (fields (field (name "MF") "ON Semiconductor"))
      (libsource (lib "eagle-import") (part "BAS16LT3G"))
    )
    (comp (ref "D83")
      (value "BAS16LT3G")
      (footprint "eagle-import:SOT95P240X111-3N")
      (fields (field (name "MF") "ON Semiconductor"))
      (libsource (lib "eagle-import") (part "BAS16LT3G"))
    )
    (comp (ref "D84")
      (value "BAS16LT3G")
      (footprint "eagle-import:SOT95P240X111-3N")
      (fields (field (name "MF") "ON Semiconductor"))
      (libsource (lib "eagle-import") (part "BAS16LT3G"))
    )
    (comp (ref "D85")
      (value "BAS16LT3G")
      (footprint "eagle-import:SOT95P240X111-3N")
      (fields (field (name "MF") "ON Semiconductor"))
      (libsource (lib "eagle-import") (part "BAS16LT3G"))
    )
    (comp (ref "D86")
      (value "BAS16LT3G")
      (footprint "eagle-import:SOT95P240X111-3N")
      (fields (field (name "MF") "ON Semiconductor"))
      (libsource (lib "eagle-import") (part "BAS16LT3G"))
    )
    (comp (ref "D87")
      (value "BAS16LT3G")
      (footprint "eagle-import:SOT95P240X111-3N")
      (fields (field (name "MF") "ON Semiconductor"))
      (libsource (lib "eagle-import") (part "BAS16LT3G"))
    )
    (comp (ref "D88")
      (value "BAS16LT3G")
      (footprint "eagle-import:SOT95P240X111-3N")
      (fields (field (name "MF") "ON Semiconductor"))
      (libsource (lib "eagle-import") (part "BAS16LT3G"))
    )
    (comp (ref "D89")
      (value "BAS16LT3G")
      (footprint "eagle-import:SOT95P240X111-3N")
      (fields (field (name "MF") "ON Semiconductor"))
      (libsource (lib "eagle-import") (part "BAS16LT3G"))
    )
    (comp (ref "D90")
      (value "BAS16LT3G")
      (footprint "eagle-import:SOT95P240X111-3N")
      (fields (field (name "MF") "ON Semiconductor"))
      (libsource (lib "eagle-import") (part "BAS16LT3G"))
    )
    (comp (ref "D91")
      (value "BAS16LT3G")
      (footprint "eagle-import:SOT95P240X111-3N")
      (fields (field (name "MF") "ON Semiconductor"))
      (libsource (lib "eagle-import") (part "BAS16LT3G"))
    )
    (comp (ref "D92")
      (value "BAS16LT3G")
      (footprint "eagle-import:SOT95P240X111-3N")
      (fields (field (name "MF") "ON Semiconductor"))
      (libsource (lib "eagle-import") (part "BAS16LT3G"))
    )
    (comp (ref "D93")
      (value "BAS16LT3G")
      (footprint "eagle-import:SOT95P240X111-3N")
      (fields (field (name "MF") "ON Semiconductor"))
      (libsource (lib "eagle-import") (part "BAS16LT3G"))
    )
    (comp (ref "D94")
      (value "BAS16LT3G")
      (footprint "eagle-import:SOT95P240X111-3N")
      (fields (field (name "MF") "ON Semiconductor"))
      (libsource (lib "eagle-import") (part "BAS16LT3G"))
    )
    (comp (ref "D95")
      (value "BAS16LT3G")
      (footprint "eagle-import:SOT95P240X111-3N")
      (fields (field (name "MF") "ON Semiconductor"))
      (libsource (lib "eagle-import") (part "BAS16LT3G"))
    )
    (comp (ref "D96")
      (value "BAS16LT3G")
      (footprint "eagle-import:SOT95P240X111-3N")
      (fields (field (name "MF") "ON Semiconductor"))
      (libsource (lib "eagle-import") (part "BAS16LT3G"))
    )
    (comp (ref "D97")
      (value "BAS16LT3G")
      (footprint "eagle-import:SOT95P240X111-3N")
      (fields (field (name "MF") "ON Semiconductor"))
      (libsource (lib "eagle-import") (part "BAS16LT3G"))
    )
    (comp (ref "D98")
      (value "BAS16LT3G")
      (footprint "eagle-import:SOT95P240X111-3N")
      (fields (field (name "MF") "ON Semiconductor"))
      (libsource (lib "eagle-import") (part "BAS16LT3G"))
    )
    (comp (ref "D99")
      (value "BAS16LT3G")
      (footprint "eagle-import:SOT95P240X111-3N")
      (fields (field (name "MF") "ON Semiconductor"))
      (libsource (lib "eagle-import") (part "BAS16LT3G"))
    )
    (comp (ref "D100")
      (value "BAS16LT3G")
      (footprint "eagle-import:SOT95P240X111-3N")
      (fields (field (name "MF") "ON Semiconductor"))
      (libsource (lib "eagle-import") (part "BAS16LT3G"))
    )
    (comp (ref "D101")
      (value "BAS16LT3G")
      (footprint "eagle-import:SOT95P240X111-3N")
      (fields (field (name "MF") "ON Semiconductor"))
      (libsource (lib "eagle-import") (part "BAS16LT3G"))
    )
    (comp (ref "D102")
      (value "BAS16LT3G")
      (footprint "eagle-import:SOT95P240X111-3N")
      (fields (field (name "MF") "ON Semiconductor"))
      (libsource (lib "eagle-import") (part "BAS16LT3G"))
    )
    (comp (ref "D103")
      (value "BAS16LT3G")
      (footprint "eagle-import:SOT95P240X111-3N")
      (fields (field (name "MF") "ON Semiconductor"))
      (libsource (lib "eagle-import") (part "BAS16LT3G"))
    )
    (comp (ref "D104")
      (value "BAS16LT3G")
      (footprint "eagle-import:SOT95P240X111-3N")
      (fields (field (name "MF") "ON Semiconductor"))
      (libsource (lib "eagle-import") (part "BAS16LT3G"))
    )
    (comp (ref "D105")
      (value "BAS16LT3G")
      (footprint "eagle-import:SOT95P240X111-3N")
      (fields (field (name "MF") "ON Semiconductor"))
      (libsource (lib "eagle-import") (part "BAS16LT3G"))
    )
    (comp (ref "D106")
      (value "BAS16LT3G")
      (footprint "eagle-import:SOT95P240X111-3N")
      (fields (field (name "MF") "ON Semiconductor"))
      (libsource (lib "eagle-import") (part "BAS16LT3G"))
    )
    (comp (ref "D107")
      (value "BAS16LT3G")
      (footprint "eagle-import:SOT95P240X111-3N")
      (fields (field (name "MF") "ON Semiconductor"))
      (libsource (lib "eagle-import") (part "BAS16LT3G"))
    )
    (comp (ref "D108")
      (value "BAS16LT3G")
      (footprint "eagle-import:SOT95P240X111-3N")
      (fields (field (name "MF") "ON Semiconductor"))
      (libsource (lib "eagle-import") (part "BAS16LT3G"))
    )
    (comp (ref "D109")
      (value "BAS16LT3G")
      (footprint "eagle-import:SOT95P240X111-3N")
      (fields (field (name "MF") "ON Semiconductor"))
      (libsource (lib "eagle-import") (part "BAS16LT3G"))
    )
    (comp (ref "D110")
      (value "BAS16LT3G")
      (footprint "eagle-import:SOT95P240X111-3N")
      (fields (field (name "MF") "ON Semiconductor"))
      (libsource (lib "eagle-import") (part "BAS16LT3G"))
    )
    (comp (ref "D111")
      (value "BAS16LT3G")
      (footprint "eagle-import:SOT95P240X111-3N")
      (fields (field (name "MF") "ON Semiconductor"))
      (libsource (lib "eagle-import") (part "BAS16LT3G"))
    )
    (comp (ref "D112")
      (value "BAS16LT3G")
      (footprint "eagle-import:SOT95P240X111-3N")
      (fields (field (name "MF") "ON Semiconductor"))
      (libsource (lib "eagle-import") (part "BAS16LT3G"))
    )
    (comp (ref "D113")
      (value "BAS16LT3G")
      (footprint "eagle-import:SOT95P240X111-3N")
      (fields (field (name "MF") "ON Semiconductor"))
      (libsource (lib "eagle-import") (part "BAS16LT3G"))
    )
    (comp (ref "D114")
      (value "BAS16LT3G")
      (footprint "eagle-import:SOT95P240X111-3N")
      (fields (field (name "MF") "ON Semiconductor"))
      (libsource (lib "eagle-import") (part "BAS16LT3G"))
    )
    (comp (ref "D115")
      (value "BAS16LT3G")
      (footprint "eagle-import:SOT95P240X111-3N")
      (fields (field (name "MF") "ON Semiconductor"))
      (libsource (lib "eagle-import") (part "BAS16LT3G"))
    )
    (comp (ref "D116")
      (value "BAS16LT3G")
      (footprint "eagle-import:SOT95P240X111-3N")
      (fields (field (name "MF") "ON Semiconductor"))
      (libsource (lib "eagle-import") (part "BAS16LT3G"))
    )
    (comp (ref "D117")
      (value "BAS16LT3G")
      (footprint "eagle-import:SOT95P240X111-3N")
      (fields (field (name "MF") "ON Semiconductor"))
      (libsource (lib "eagle-import") (part "BAS16LT3G"))
    )
    (comp (ref "D118")
      (value "BAS16LT3G")
      (footprint "eagle-import:SOT95P240X111-3N")
      (fields (field (name "MF") "ON Semiconductor"))
      (libsource (lib "eagle-import") (part "BAS16LT3G"))
    )
    (comp (ref "D119")
      (value "BAS16LT3G")
      (footprint "eagle-import:SOT95P240X111-3N")
      (fields (field (name "MF") "ON Semiconductor"))
      (libsource (lib "eagle-import") (part "BAS16LT3G"))
    )
    (comp (ref "D120")
      (value "BAS16LT3G")
      (footprint "eagle-import:SOT95P240X111-3N")
      (fields (field (name "MF") "ON Semiconductor"))
      (libsource (lib "eagle-import") (part "BAS16LT3G"))
    )
    (comp (ref "D121")
      (value "BAS16LT3G")
      (footprint "eagle-import:SOT95P240X111-3N")
      (fields (field (name "MF") "ON Semiconductor"))
      (libsource (lib "eagle-import") (part "BAS16LT3G"))
    )
    (comp (ref "D122")
      (value "BAS16LT3G")
      (footprint "eagle-import:SOT95P240X111-3N")
      (fields (field (name "MF") "ON Semiconductor"))
      (libsource (lib "eagle-import") (part "BAS16LT3G"))
    )
    (comp (ref "D123")
      (value "BAS16LT3G")
      (footprint "eagle-import:SOT95P240X111-3N")
      (fields (field (name "MF") "ON Semiconductor"))
      (libsource (lib "eagle-import") (part "BAS16LT3G"))
    )
    (comp (ref "D124")
      (value "BAS16LT3G")
      (footprint "eagle-import:SOT95P240X111-3N")
      (fields (field (name "MF") "ON Semiconductor"))
      (libsource (lib "eagle-import") (part "BAS16LT3G"))
    )
    (comp (ref "D125")
      (value "BAS16LT3G")
      (footprint "eagle-import:SOT95P240X111-3N")
      (fields (field (name "MF") "ON Semiconductor"))
      (libsource (lib "eagle-import") (part "BAS16LT3G"))
    )
    (comp (ref "D126")
      (value "BAS16LT3G")
      (footprint "eagle-import:SOT95P240X111-3N")
      (fields (field (name "MF") "ON Semiconductor"))
      (libsource (lib "eagle-import") (part "BAS16LT3G"))
    )
    (comp (ref "D127")
      (value "BAS16LT3G")
      (footprint "eagle-import:SOT95P240X111-3N")
      (fields (field (name "MF") "ON Semiconductor"))
      (libsource (lib "eagle-import") (part "BAS16LT3G"))
    )
    (comp (ref "D128")
      (value "BAS16LT3G")
      (footprint "eagle-import:SOT95P240X111-3N")
      (fields (field (name "MF") "ON Semiconductor"))
      (libsource (lib "eagle-import") (part "BAS16LT3G"))
    )
    (comp (ref "D129")
      (value "BAS16LT3G")
      (footprint "eagle-import:SOT95P240X111-3N")
      (fields (field (name "MF") "ON Semiconductor"))
      (libsource (lib "eagle-import") (part "BAS16LT3G"))
    )
    (comp (ref "D130")
      (value "BAS16LT3G")
      (footprint "eagle-import:SOT95P240X111-3N")
      (fields (field (name "MF") "ON Semiconductor"))
      (libsource (lib "eagle-import") (part "BAS16LT3G"))
    )
    (comp (ref "D131")
      (value "BAS16LT3G")
      (footprint "eagle-import:SOT95P240X111-3N")
      (fields (field (name "MF") "ON Semiconductor"))
      (libsource (lib "eagle-import") (part "BAS16LT3G"))
    )
    (comp (ref "D132")
      (value "BAS16LT3G")
      (footprint "eagle-import:SOT95P240X111-3N")
      (fields (field (name "MF") "ON Semiconductor"))
      (libsource (lib "eagle-import") (part "BAS16LT3G"))
    )
    (comp (ref "D133")
      (value "BAS16LT3G")
      (footprint "eagle-import:SOT95P240X111-3N")
      (fields (field (name "MF") "ON Semiconductor"))
      (libsource (lib "eagle-import") (part "BAS16LT3G"))
    )
    (comp (ref "D134")
      (value "BAS16LT3G")
      (footprint "eagle-import:SOT95P240X111-3N")
      (fields (field (name "MF") "ON Semiconductor"))
      (libsource (lib "eagle-import") (part "BAS16LT3G"))
    )
    (comp (ref "D135")
      (value "BAS16LT3G")
      (footprint "eagle-import:SOT95P240X111-3N")
      (fields (field (name "MF") "ON Semiconductor"))
      (libsource (lib "eagle-import") (part "BAS16LT3G"))
    )
    (comp (ref "D136")
      (value "BAS16LT3G")
      (footprint "eagle-import:SOT95P240X111-3N")
      (fields (field (name "MF") "ON Semiconductor"))
      (libsource (lib "eagle-import") (part "BAS16LT3G"))
    )
    (comp (ref "D137")
      (value "BAS16LT3G")
      (footprint "eagle-import:SOT95P240X111-3N")
      (fields (field (name "MF") "ON Semiconductor"))
      (libsource (lib "eagle-import") (part "BAS16LT3G"))
    )
    (comp (ref "D138")
      (value "BAS16LT3G")
      (footprint "eagle-import:SOT95P240X111-3N")
      (fields (field (name "MF") "ON Semiconductor"))
      (libsource (lib "eagle-import") (part "BAS16LT3G"))
    )
    (comp (ref "D139")
      (value "BAS16LT3G")
      (footprint "eagle-import:SOT95P240X111-3N")
      (fields (field (name "MF") "ON Semiconductor"))
      (libsource (lib "eagle-import") (part "BAS16LT3G"))
    )
    (comp (ref "D140")
      (value "BAS16LT3G")
      (footprint "eagle-import:SOT95P240X111-3N")
      (fields (field (name "MF") "ON Semiconductor"))
      (libsource (lib "eagle-import") (part "BAS16LT3G"))
    )
    (comp (ref "D141")
      (value "BAS16LT3G")
      (footprint "eagle-import:SOT95P240X111-3N")
      (fields (field (name "MF") "ON Semiconductor"))
      (libsource (lib "eagle-import") (part "BAS16LT3G"))
    )
    (comp (ref "D142")
      (value "BAS16LT3G")
      (footprint "eagle-import:SOT95P240X111-3N")
      (fields (field (name "MF") "ON Semiconductor"))
      (libsource (lib "eagle-import") (part "BAS16LT3G"))
    )
    (comp (ref "D143")
      (value "BAS16LT3G")
      (footprint "eagle-import:SOT95P240X111-3N")
      (fields (field (name "MF") "ON Semiconductor"))
      (libsource (lib "eagle-import") (part "BAS16LT3G"))
    )
    (comp (ref "D144")
      (value "BAS16LT3G")
      (footprint "eagle-import:SOT95P240X111-3N")
      (fields (field (name "MF") "ON Semiconductor"))
      (libsource (lib "eagle-import") (part "BAS16LT3G"))
    )
    (comp (ref "D145")
      (value "BAS16LT3G")
      (footprint "eagle-import:SOT95P240X111-3N")
      (fields (field (name "MF") "ON Semiconductor"))
      (libsource (lib "eagle-import") (part "BAS16LT3G"))
    )
    (comp (ref "D146")
      (value "BAS16LT3G")
      (footprint "eagle-import:SOT95P240X111-3N")
      (fields (field (name "MF") "ON Semiconductor"))
      (libsource (lib "eagle-import") (part "BAS16LT3G"))
    )
    (comp (ref "D147")
      (value "BAS16LT3G")
      (footprint "eagle-import:SOT95P240X111-3N")
      (fields (field (name "MF") "ON Semiconductor"))
      (libsource (lib "eagle-import") (part "BAS16LT3G"))
    )
    (comp (ref "D148")
      (value "BAS16LT3G")
      (footprint "eagle-import:SOT95P240X111-3N")
      (fields (field (name "MF") "ON Semiconductor"))
      (libsource (lib "eagle-import") (part "BAS16LT3G"))
    )
    (comp (ref "D149")
      (value "BAS16LT3G")
      (footprint "eagle-import:SOT95P240X111-3N")
      (fields (field (name "MF") "ON Semiconductor"))
      (libsource (lib "eagle-import") (part "BAS16LT3G"))
    )
    (comp (ref "D150")
      (value "BAS16LT3G")
      (footprint "eagle-import:SOT95P240X111-3N")
      (fields (field (name "MF") "ON Semiconductor"))
      (libsource (lib "eagle-import") (part "BAS16LT3G"))
    )
    (comp (ref "D151")
      (value "BAS16LT3G")
      (footprint "eagle-import:SOT95P240X111-3N")
      (fields (field (name "MF") "ON Semiconductor"))
      (libsource (lib "eagle-import") (part "BAS16LT3G"))
    )
    (comp (ref "D152")
      (value "BAS16LT3G")
      (footprint "eagle-import:SOT95P240X111-3N")
      (fields (field (name "MF") "ON Semiconductor"))
      (libsource (lib "eagle-import") (part "BAS16LT3G"))
    )
    (comp (ref "D153")
      (value "BAS16LT3G")
      (footprint "eagle-import:SOT95P240X111-3N")
      (fields (field (name "MF") "ON Semiconductor"))
      (libsource (lib "eagle-import") (part "BAS16LT3G"))
    )
    (comp (ref "KEY_1")
      (value "CHERRY-MX-LED")
      (footprint "eagle-import:CHERRY-MX-LED")
      (libsource (lib "eagle-import") (part "CHERRY-MX-LED"))
    )
    (comp (ref "KEY_2")
      (value "CHERRY-MX-LED")
      (footprint "eagle-import:CHERRY-MX-LED")
      (libsource (lib "eagle-import") (part "CHERRY-MX-LED"))
    )
    (comp (ref "KEY_3")
      (value "CHERRY-MX-LED")
      (footprint "eagle-import:CHERRY-MX-LED")
      (libsource (lib "eagle-import") (part "CHERRY-MX-LED"))
    )
    (comp (ref "KEY_4")
      (value "CHERRY-MX-LED")
      (footprint "eagle-import:CHERRY-MX-LED")
      (libsource (lib "eagle-import") (part "CHERRY-MX-LED"))
    )
    (comp (ref "KEY_5")
      (value "CHERRY-MX-LED")
      (footprint "eagle-import:CHERRY-MX-LED")
      (libsource (lib "eagle-import") (part "CHERRY-MX-LED"))
    )
    (comp (ref "KEY_6")
      (value "CHERRY-MX-LED")
      (footprint "eagle-import:CHERRY-MX-LED")
      (libsource (lib "eagle-import") (part "CHERRY-MX-LED"))
    )
    (comp (ref "KEY_7")
      (value "CHERRY-MX-LED")
      (footprint "eagle-import:CHERRY-MX-LED")
      (libsource (lib "eagle-import") (part "CHERRY-MX-LED"))
    )
    (comp (ref "KEY_8")
      (value "CHERRY-MX-LED")
      (footprint "eagle-import:CHERRY-MX-LED")
      (libsource (lib "eagle-import") (part "CHERRY-MX-LED"))
    )
    (comp (ref "KEY_9")
      (value "CHERRY-MX-LED")
      (footprint "eagle-import:CHERRY-MX-LED")
      (libsource (lib "eagle-import") (part "CHERRY-MX-LED"))
    )
    (comp (ref "KEY_10")
      (value "CHERRY-MX-LED")
      (footprint "eagle-import:CHERRY-MX-LED")
      (libsource (lib "eagle-import") (part "CHERRY-MX-LED"))
    )
    (comp (ref "KEY_11")
      (value "CHERRY-MX-LED")
      (footprint "eagle-import:CHERRY-MX-LED")
      (libsource (lib "eagle-import") (part "CHERRY-MX-LED"))
    )
    (comp (ref "KEY_12")
      (value "CHERRY-MX-LED")
      (footprint "eagle-import:CHERRY-MX-LED")
      (libsource (lib "eagle-import") (part "CHERRY-MX-LED"))
    )
    (comp (ref "KEY_13")
      (value "CHERRY-MX-LED")
      (footprint "eagle-import:CHERRY-MX-LED")
      (libsource (lib "eagle-import") (part "CHERRY-MX-LED"))
    )
    (comp (ref "KEY_14")
      (value "CHERRY-MX-LED")
      (footprint "eagle-import:CHERRY-MX-LED")
      (libsource (lib "eagle-import") (part "CHERRY-MX-LED"))
    )
    (comp (ref "KEY_15")
      (value "CHERRY-MX-LED")
      (footprint "eagle-import:CHERRY-MX-LED")
      (libsource (lib "eagle-import") (part "CHERRY-MX-LED"))
    )
    (comp (ref "KEY_16")
      (value "CHERRY-MX-LED")
      (footprint "eagle-import:CHERRY-MX-LED")
      (libsource (lib "eagle-import") (part "CHERRY-MX-LED"))
    )
    (comp (ref "KEY_17")
      (value "CHERRY-MX-LED")
      (footprint "eagle-import:CHERRY-MX-LED")
      (libsource (lib "eagle-import") (part "CHERRY-MX-LED"))
    )
    (comp (ref "KEY_18")
      (value "CHERRY-MX-LED")
      (footprint "eagle-import:CHERRY-MX-LED")
      (libsource (lib "eagle-import") (part "CHERRY-MX-LED"))
    )
    (comp (ref "KEY_19")
      (value "CHERRY-MX-LED")
      (footprint "eagle-import:CHERRY-MX-LED")
      (libsource (lib "eagle-import") (part "CHERRY-MX-LED"))
    )
    (comp (ref "KEY_20")
      (value "CHERRY-MX-LED")
      (footprint "eagle-import:CHERRY-MX-LED")
      (libsource (lib "eagle-import") (part "CHERRY-MX-LED"))
    )
    (comp (ref "KEY_21")
      (value "CHERRY-MX-LED")
      (footprint "eagle-import:CHERRY-MX-LED")
      (libsource (lib "eagle-import") (part "CHERRY-MX-LED"))
    )
    (comp (ref "KEY_22")
      (value "CHERRY-MX-LED")
      (footprint "eagle-import:CHERRY-MX-LED")
      (libsource (lib "eagle-import") (part "CHERRY-MX-LED"))
    )
    (comp (ref "KEY_23")
      (value "CHERRY-MX-LED")
      (footprint "eagle-import:CHERRY-MX-LED")
      (libsource (lib "eagle-import") (part "CHERRY-MX-LED"))
    )
    (comp (ref "KEY_24")
      (value "CHERRY-MX-LED")
      (footprint "eagle-import:CHERRY-MX-LED")
      (libsource (lib "eagle-import") (part "CHERRY-MX-LED"))
    )
    (comp (ref "KEY_25")
      (value "CHERRY-MX-LED")
      (footprint "eagle-import:CHERRY-MX-LED")
      (libsource (lib "eagle-import") (part "CHERRY-MX-LED"))
    )
    (comp (ref "KEY_26")
      (value "CHERRY-MX-LED")
      (footprint "eagle-import:CHERRY-MX-LED")
      (libsource (lib "eagle-import") (part "CHERRY-MX-LED"))
    )
    (comp (ref "KEY_27")
      (value "CHERRY-MX-LED")
      (footprint "eagle-import:CHERRY-MX-LED")
      (libsource (lib "eagle-import") (part "CHERRY-MX-LED"))
    )
    (comp (ref "KEY_28")
      (value "CHERRY-MX-LED")
      (footprint "eagle-import:CHERRY-MX-LED")
      (libsource (lib "eagle-import") (part "CHERRY-MX-LED"))
    )
    (comp (ref "KEY_29")
      (value "CHERRY-MX-LED")
      (footprint "eagle-import:CHERRY-MX-LED")
      (libsource (lib "eagle-import") (part "CHERRY-MX-LED"))
    )
    (comp (ref "KEY_30")
      (value "CHERRY-MX-LED")
      (footprint "eagle-import:CHERRY-MX-LED")
      (libsource (lib "eagle-import") (part "CHERRY-MX-LED"))
    )
    (comp (ref "KEY_30_OFFSET")
      (value "CHERRY-MX-LED-NOPIN")
      (footprint "eagle-import:CHERRY-MX-LED-NOPIN")
      (libsource (lib "eagle-import") (part "CHERRY-MX-LED-NOPIN"))
    )
    (comp (ref "KEY_31")
      (value "CHERRY-MX-LED")
      (footprint "eagle-import:CHERRY-MX-LED")
      (libsource (lib "eagle-import") (part "CHERRY-MX-LED"))
    )
    (comp (ref "KEY_31_OFFSET")
      (value "CHERRY-MX-LED-NOPIN")
      (footprint "eagle-import:CHERRY-MX-LED-NOPIN")
      (libsource (lib "eagle-import") (part "CHERRY-MX-LED-NOPIN"))
    )
    (comp (ref "KEY_32")
      (value "CHERRY-MX-LED")
      (footprint "eagle-import:CHERRY-MX-LED")
      (libsource (lib "eagle-import") (part "CHERRY-MX-LED"))
    )
    (comp (ref "KEY_32_OFFSET")
      (value "CHERRY-MX-LED-NOPIN")
      (footprint "eagle-import:CHERRY-MX-LED-NOPIN")
      (libsource (lib "eagle-import") (part "CHERRY-MX-LED-NOPIN"))
    )
    (comp (ref "KEY_33")
      (value "CHERRY-MX-LED")
      (footprint "eagle-import:CHERRY-MX-LED")
      (libsource (lib "eagle-import") (part "CHERRY-MX-LED"))
    )
    (comp (ref "KEY_33_OFFSET")
      (value "CHERRY-MX-LED-NOPIN")
      (footprint "eagle-import:CHERRY-MX-LED-NOPIN")
      (libsource (lib "eagle-import") (part "CHERRY-MX-LED-NOPIN"))
    )
    (comp (ref "KEY_34")
      (value "CHERRY-MX-LED")
      (footprint "eagle-import:CHERRY-MX-LED")
      (libsource (lib "eagle-import") (part "CHERRY-MX-LED"))
    )
    (comp (ref "KEY_35")
      (value "CHERRY-MX-LED")
      (footprint "eagle-import:CHERRY-MX-LED")
      (libsource (lib "eagle-import") (part "CHERRY-MX-LED"))
    )
    (comp (ref "KEY_36")
      (value "CHERRY-MX-LED")
      (footprint "eagle-import:CHERRY-MX-LED")
      (libsource (lib "eagle-import") (part "CHERRY-MX-LED"))
    )
    (comp (ref "KEY_37")
      (value "CHERRY-MX-LED")
      (footprint "eagle-import:CHERRY-MX-LED")
      (libsource (lib "eagle-import") (part "CHERRY-MX-LED"))
    )
    (comp (ref "KEY_38")
      (value "CHERRY-MX-LED")
      (footprint "eagle-import:CHERRY-MX-LED")
      (libsource (lib "eagle-import") (part "CHERRY-MX-LED"))
    )
    (comp (ref "KEY_39")
      (value "CHERRY-MX-LED")
      (footprint "eagle-import:CHERRY-MX-LED")
      (libsource (lib "eagle-import") (part "CHERRY-MX-LED"))
    )
    (comp (ref "KEY_40")
      (value "CHERRY-MX-LED")
      (footprint "eagle-import:CHERRY-MX-LED")
      (libsource (lib "eagle-import") (part "CHERRY-MX-LED"))
    )
    (comp (ref "KEY_41")
      (value "CHERRY-MX-LED")
      (footprint "eagle-import:CHERRY-MX-LED")
      (libsource (lib "eagle-import") (part "CHERRY-MX-LED"))
    )
    (comp (ref "KEY_42")
      (value "CHERRY-MX-LED")
      (footprint "eagle-import:CHERRY-MX-LED")
      (libsource (lib "eagle-import") (part "CHERRY-MX-LED"))
    )
    (comp (ref "KEY_43")
      (value "CHERRY-MX-LED")
      (footprint "eagle-import:CHERRY-MX-LED")
      (libsource (lib "eagle-import") (part "CHERRY-MX-LED"))
    )
    (comp (ref "KEY_44")
      (value "CHERRY-MX-LED")
      (footprint "eagle-import:CHERRY-MX-LED")
      (libsource (lib "eagle-import") (part "CHERRY-MX-LED"))
    )
    (comp (ref "KEY_45")
      (value "CHERRY-MX-LED")
      (footprint "eagle-import:CHERRY-MX-LED")
      (libsource (lib "eagle-import") (part "CHERRY-MX-LED"))
    )
    (comp (ref "KEY_46")
      (value "CHERRY-MX-LED")
      (footprint "eagle-import:CHERRY-MX-LED")
      (libsource (lib "eagle-import") (part "CHERRY-MX-LED"))
    )
    (comp (ref "KEY_47")
      (value "CHERRY-MX-LED")
      (footprint "eagle-import:CHERRY-MX-LED")
      (libsource (lib "eagle-import") (part "CHERRY-MX-LED"))
    )
    (comp (ref "KEY_48")
      (value "CHERRY-MX-LED")
      (footprint "eagle-import:CHERRY-MX-LED")
      (libsource (lib "eagle-import") (part "CHERRY-MX-LED"))
    )
    (comp (ref "KEY_49")
      (value "CHERRY-MX-LED")
      (footprint "eagle-import:CHERRY-MX-LED")
      (libsource (lib "eagle-import") (part "CHERRY-MX-LED"))
    )
    (comp (ref "KEY_50")
      (value "CHERRY-MX-LED")
      (footprint "eagle-import:CHERRY-MX-LED")
      (libsource (lib "eagle-import") (part "CHERRY-MX-LED"))
    )
    (comp (ref "KEY_51")
      (value "CHERRY-MX-LED")
      (footprint "eagle-import:CHERRY-MX-LED")
      (libsource (lib "eagle-import") (part "CHERRY-MX-LED"))
    )
    (comp (ref "KEY_52")
      (value "CHERRY-MX-LED")
      (footprint "eagle-import:CHERRY-MX-LED")
      (libsource (lib "eagle-import") (part "CHERRY-MX-LED"))
    )
    (comp (ref "KEY_53")
      (value "CHERRY-MX-LED")
      (footprint "eagle-import:CHERRY-MX-LED")
      (libsource (lib "eagle-import") (part "CHERRY-MX-LED"))
    )
    (comp (ref "KEY_54")
      (value "CHERRY-MX-LED")
      (footprint "eagle-import:CHERRY-MX-LED")
      (libsource (lib "eagle-import") (part "CHERRY-MX-LED"))
    )
    (comp (ref "KEY_55")
      (value "CHERRY-MX-LED")
      (footprint "eagle-import:CHERRY-MX-LED")
      (libsource (lib "eagle-import") (part "CHERRY-MX-LED"))
    )
    (comp (ref "KEY_56")
      (value "CHERRY-MX-LED")
      (footprint "eagle-import:CHERRY-MX-LED")
      (libsource (lib "eagle-import") (part "CHERRY-MX-LED"))
    )
    (comp (ref "KEY_57")
      (value "CHERRY-MX-LED")
      (footprint "eagle-import:CHERRY-MX-LED")
      (libsource (lib "eagle-import") (part "CHERRY-MX-LED"))
    )
    (comp (ref "KEY_58")
      (value "CHERRY-MX-LED")
      (footprint "eagle-import:CHERRY-MX-LED")
      (libsource (lib "eagle-import") (part "CHERRY-MX-LED"))
    )
    (comp (ref "KEY_59")
      (value "CHERRY-MX-LED")
      (footprint "eagle-import:CHERRY-MX-LED")
      (libsource (lib "eagle-import") (part "CHERRY-MX-LED"))
    )
    (comp (ref "KEY_60")
      (value "CHERRY-MX-LED")
      (footprint "eagle-import:CHERRY-MX-LED")
      (libsource (lib "eagle-import") (part "CHERRY-MX-LED"))
    )
    (comp (ref "KEY_61")
      (value "CHERRY-MX-LED")
      (footprint "eagle-import:CHERRY-MX-LED")
      (libsource (lib "eagle-import") (part "CHERRY-MX-LED"))
    )
    (comp (ref "KEY_62")
      (value "CHERRY-MX-LED")
      (footprint "eagle-import:CHERRY-MX-LED")
      (libsource (lib "eagle-import") (part "CHERRY-MX-LED"))
    )
    (comp (ref "KEY_63")
      (value "CHERRY-MX-LED")
      (footprint "eagle-import:CHERRY-MX-LED")
      (libsource (lib "eagle-import") (part "CHERRY-MX-LED"))
    )
    (comp (ref "KEY_64")
      (value "CHERRY-MX-LED")
      (footprint "eagle-import:CHERRY-MX-LED")
      (libsource (lib "eagle-import") (part "CHERRY-MX-LED"))
    )
    (comp (ref "KEY_65")
      (value "CHERRY-MX-LED")
      (footprint "eagle-import:CHERRY-MX-LED")
      (libsource (lib "eagle-import") (part "CHERRY-MX-LED"))
    )
    (comp (ref "KEY_66")
      (value "CHERRY-MX-LED")
      (footprint "eagle-import:CHERRY-MX-LED")
      (libsource (lib "eagle-import") (part "CHERRY-MX-LED"))
    )
    (comp (ref "KEY_67")
      (value "CHERRY-MX-LED")
      (footprint "eagle-import:CHERRY-MX-LED")
      (libsource (lib "eagle-import") (part "CHERRY-MX-LED"))
    )
    (comp (ref "KEY_68")
      (value "CHERRY-MX-LED")
      (footprint "eagle-import:CHERRY-MX-LED")
      (libsource (lib "eagle-import") (part "CHERRY-MX-LED"))
    )
    (comp (ref "KEY_69")
      (value "CHERRY-MX-LED")
      (footprint "eagle-import:CHERRY-MX-LED")
      (libsource (lib "eagle-import") (part "CHERRY-MX-LED"))
    )
    (comp (ref "KEY_70")
      (value "CHERRY-MX-LED")
      (footprint "eagle-import:CHERRY-MX-LED")
      (libsource (lib "eagle-import") (part "CHERRY-MX-LED"))
    )
    (comp (ref "KEY_71")
      (value "CHERRY-MX-LED")
      (footprint "eagle-import:CHERRY-MX-LED")
      (libsource (lib "eagle-import") (part "CHERRY-MX-LED"))
    )
    (comp (ref "KEY_72")
      (value "CHERRY-MX-LED")
      (footprint "eagle-import:CHERRY-MX-LED")
      (libsource (lib "eagle-import") (part "CHERRY-MX-LED"))
    )
    (comp (ref "KEY_73")
      (value "CHERRY-MX-LED")
      (footprint "eagle-import:CHERRY-MX-LED")
      (libsource (lib "eagle-import") (part "CHERRY-MX-LED"))
    )
    (comp (ref "KEY_74")
      (value "CHERRY-MX-LED")
      (footprint "eagle-import:CHERRY-MX-LED")
      (libsource (lib "eagle-import") (part "CHERRY-MX-LED"))
    )
    (comp (ref "KEY_75")
      (value "CHERRY-MX-LED")
      (footprint "eagle-import:CHERRY-MX-LED")
      (libsource (lib "eagle-import") (part "CHERRY-MX-LED"))
    )
    (comp (ref "KEY_76")
      (value "CHERRY-MX-LED")
      (footprint "eagle-import:CHERRY-MX-LED")
      (libsource (lib "eagle-import") (part "CHERRY-MX-LED"))
    )
    (comp (ref "KEY_77")
      (value "CHERRY-MX-LED")
      (footprint "eagle-import:CHERRY-MX-LED")
      (libsource (lib "eagle-import") (part "CHERRY-MX-LED"))
    )
    (comp (ref "KEY_78")
      (value "CHERRY-MX-LED")
      (footprint "eagle-import:CHERRY-MX-LED")
      (libsource (lib "eagle-import") (part "CHERRY-MX-LED"))
    )
    (comp (ref "KEY_79")
      (value "CHERRY-MX-LED")
      (footprint "eagle-import:CHERRY-MX-LED")
      (libsource (lib "eagle-import") (part "CHERRY-MX-LED"))
    )
    (comp (ref "KEY_80")
      (value "CHERRY-MX-LED")
      (footprint "eagle-import:CHERRY-MX-LED")
      (libsource (lib "eagle-import") (part "CHERRY-MX-LED"))
    )
    (comp (ref "KEY_81")
      (value "CHERRY-MX-LED")
      (footprint "eagle-import:CHERRY-MX-LED")
      (libsource (lib "eagle-import") (part "CHERRY-MX-LED"))
    )
    (comp (ref "KEY_82")
      (value "CHERRY-MX-LED")
      (footprint "eagle-import:CHERRY-MX-LED")
      (libsource (lib "eagle-import") (part "CHERRY-MX-LED"))
    )
    (comp (ref "KEY_83")
      (value "CHERRY-MX-LED")
      (footprint "eagle-import:CHERRY-MX-LED")
      (libsource (lib "eagle-import") (part "CHERRY-MX-LED"))
    )
    (comp (ref "KEY_84")
      (value "CHERRY-MX-LED")
      (footprint "eagle-import:CHERRY-MX-LED")
      (libsource (lib "eagle-import") (part "CHERRY-MX-LED"))
    )
    (comp (ref "KEY_85")
      (value "CHERRY-MX-LED")
      (footprint "eagle-import:CHERRY-MX-LED")
      (libsource (lib "eagle-import") (part "CHERRY-MX-LED"))
    )
    (comp (ref "KEY_86")
      (value "CHERRY-MX-LED")
      (footprint "eagle-import:CHERRY-MX-LED")
      (libsource (lib "eagle-import") (part "CHERRY-MX-LED"))
    )
    (comp (ref "KEY_87")
      (value "CHERRY-MX-LED")
      (footprint "eagle-import:CHERRY-MX-LED")
      (libsource (lib "eagle-import") (part "CHERRY-MX-LED"))
    )
    (comp (ref "KEY_88")
      (value "CHERRY-MX-LED")
      (footprint "eagle-import:CHERRY-MX-LED")
      (libsource (lib "eagle-import") (part "CHERRY-MX-LED"))
    )
    (comp (ref "KEY_89")
      (value "CHERRY-MX-LED")
      (footprint "eagle-import:CHERRY-MX-LED")
      (libsource (lib "eagle-import") (part "CHERRY-MX-LED"))
    )
    (comp (ref "KEY_90")
      (value "CHERRY-MX-LED")
      (footprint "eagle-import:CHERRY-MX-LED")
      (libsource (lib "eagle-import") (part "CHERRY-MX-LED"))
    )
    (comp (ref "KEY_91")
      (value "CHERRY-MX-LED")
      (footprint "eagle-import:CHERRY-MX-LED")
      (libsource (lib "eagle-import") (part "CHERRY-MX-LED"))
    )
    (comp (ref "KEY_92")
      (value "CHERRY-MX-LED")
      (footprint "eagle-import:CHERRY-MX-LED")
      (libsource (lib "eagle-import") (part "CHERRY-MX-LED"))
    )
    (comp (ref "KEY_93")
      (value "CHERRY-MX-LED")
      (footprint "eagle-import:CHERRY-MX-LED")
      (libsource (lib "eagle-import") (part "CHERRY-MX-LED"))
    )
    (comp (ref "KEY_94")
      (value "CHERRY-MX-LED")
      (footprint "eagle-import:CHERRY-MX-LED")
      (libsource (lib "eagle-import") (part "CHERRY-MX-LED"))
    )
    (comp (ref "KEY_95")
      (value "CHERRY-MX-LED")
      (footprint "eagle-import:CHERRY-MX-LED")
      (libsource (lib "eagle-import") (part "CHERRY-MX-LED"))
    )
    (comp (ref "KEY_96")
      (value "CHERRY-MX-LED")
      (footprint "eagle-import:CHERRY-MX-LED")
      (libsource (lib "eagle-import") (part "CHERRY-MX-LED"))
    )
    (comp (ref "KEY_97")
      (value "CHERRY-MX-LED")
      (footprint "eagle-import:CHERRY-MX-LED")
      (libsource (lib "eagle-import") (part "CHERRY-MX-LED"))
    )
    (comp (ref "KEY_98")
      (value "CHERRY-MX-LED")
      (footprint "eagle-import:CHERRY-MX-LED")
      (libsource (lib "eagle-import") (part "CHERRY-MX-LED"))
    )
    (comp (ref "KEY_99")
      (value "CHERRY-MX-LED")
      (footprint "eagle-import:CHERRY-MX-LED")
      (libsource (lib "eagle-import") (part "CHERRY-MX-LED"))
    )
    (comp (ref "KEY_100")
      (value "CHERRY-MX-LED")
      (footprint "eagle-import:CHERRY-MX-LED")
      (libsource (lib "eagle-import") (part "CHERRY-MX-LED"))
    )
    (comp (ref "KEY_101")
      (value "CHERRY-MX-LED")
      (footprint "eagle-import:CHERRY-MX-LED")
      (libsource (lib "eagle-import") (part "CHERRY-MX-LED"))
    )
    (comp (ref "KEY_102")
      (value "CHERRY-MX-LED")
      (footprint "eagle-import:CHERRY-MX-LED")
      (libsource (lib "eagle-import") (part "CHERRY-MX-LED"))
    )
    (comp (ref "KEY_103")
      (value "CHERRY-MX-LED")
      (footprint "eagle-import:CHERRY-MX-LED")
      (libsource (lib "eagle-import") (part "CHERRY-MX-LED"))
    )
    (comp (ref "KEY_104")
      (value "CHERRY-MX-LED")
      (footprint "eagle-import:CHERRY-MX-LED")
      (libsource (lib "eagle-import") (part "CHERRY-MX-LED"))
    )
    (comp (ref "KEY_105")
      (value "CHERRY-MX-LED")
      (footprint "eagle-import:CHERRY-MX-LED")
      (libsource (lib "eagle-import") (part "CHERRY-MX-LED"))
    )
    (comp (ref "KEY_106")
      (value "CHERRY-MX-LED")
      (footprint "eagle-import:CHERRY-MX-LED")
      (libsource (lib "eagle-import") (part "CHERRY-MX-LED"))
    )
    (comp (ref "KEY_107")
      (value "CHERRY-MX-LED")
      (footprint "eagle-import:CHERRY-MX-LED")
      (libsource (lib "eagle-import") (part "CHERRY-MX-LED"))
    )
    (comp (ref "KEY_108")
      (value "CHERRY-MX-LED")
      (footprint "eagle-import:CHERRY-MX-LED")
      (libsource (lib "eagle-import") (part "CHERRY-MX-LED"))
    )
    (comp (ref "KEY_109")
      (value "CHERRY-MX-LED")
      (footprint "eagle-import:CHERRY-MX-LED")
      (libsource (lib "eagle-import") (part "CHERRY-MX-LED"))
    )
    (comp (ref "KEY_110")
      (value "CHERRY-MX-LED")
      (footprint "eagle-import:CHERRY-MX-LED")
      (libsource (lib "eagle-import") (part "CHERRY-MX-LED"))
    )
    (comp (ref "KEY_111")
      (value "CHERRY-MX-LED")
      (footprint "eagle-import:CHERRY-MX-LED")
      (libsource (lib "eagle-import") (part "CHERRY-MX-LED"))
    )
    (comp (ref "KEY_112")
      (value "CHERRY-MX-LED")
      (footprint "eagle-import:CHERRY-MX-LED")
      (libsource (lib "eagle-import") (part "CHERRY-MX-LED"))
    )
    (comp (ref "KEY_113")
      (value "CHERRY-MX-LED")
      (footprint "eagle-import:CHERRY-MX-LED")
      (libsource (lib "eagle-import") (part "CHERRY-MX-LED"))
    )
    (comp (ref "KEY_114")
      (value "CHERRY-MX-LED")
      (footprint "eagle-import:CHERRY-MX-LED")
      (libsource (lib "eagle-import") (part "CHERRY-MX-LED"))
    )
    (comp (ref "KEY_115")
      (value "CHERRY-MX-LED")
      (footprint "eagle-import:CHERRY-MX-LED")
      (libsource (lib "eagle-import") (part "CHERRY-MX-LED"))
    )
    (comp (ref "KEY_116")
      (value "CHERRY-MX-LED")
      (footprint "eagle-import:CHERRY-MX-LED")
      (libsource (lib "eagle-import") (part "CHERRY-MX-LED"))
    )
    (comp (ref "KEY_117")
      (value "CHERRY-MX-LED")
      (footprint "eagle-import:CHERRY-MX-LED")
      (libsource (lib "eagle-import") (part "CHERRY-MX-LED"))
    )
    (comp (ref "KEY_118")
      (value "CHERRY-MX-LED")
      (footprint "eagle-import:CHERRY-MX-LED")
      (libsource (lib "eagle-import") (part "CHERRY-MX-LED"))
    )
    (comp (ref "KEY_119")
      (value "CHERRY-MX-LED")
      (footprint "eagle-import:CHERRY-MX-LED")
      (libsource (lib "eagle-import") (part "CHERRY-MX-LED"))
    )
    (comp (ref "KEY_120")
      (value "CHERRY-MX-LED")
      (footprint "eagle-import:CHERRY-MX-LED")
      (libsource (lib "eagle-import") (part "CHERRY-MX-LED"))
    )
    (comp (ref "KEY_121")
      (value "CHERRY-MX-LED")
      (footprint "eagle-import:CHERRY-MX-LED")
      (libsource (lib "eagle-import") (part "CHERRY-MX-LED"))
    )
    (comp (ref "KEY_122")
      (value "CHERRY-MX-LED")
      (footprint "eagle-import:CHERRY-MX-LED")
      (libsource (lib "eagle-import") (part "CHERRY-MX-LED"))
    )
    (comp (ref "KEY_123")
      (value "CHERRY-MX-LED")
      (footprint "eagle-import:CHERRY-MX-LED")
      (libsource (lib "eagle-import") (part "CHERRY-MX-LED"))
    )
    (comp (ref "KEY_124")
      (value "CHERRY-MX-LED")
      (footprint "eagle-import:CHERRY-MX-LED")
      (libsource (lib "eagle-import") (part "CHERRY-MX-LED"))
    )
    (comp (ref "KEY_125")
      (value "CHERRY-MX-LED")
      (footprint "eagle-import:CHERRY-MX-LED")
      (libsource (lib "eagle-import") (part "CHERRY-MX-LED"))
    )
    (comp (ref "KEY_126")
      (value "CHERRY-MX-LED")
      (footprint "eagle-import:CHERRY-MX-LED")
      (libsource (lib "eagle-import") (part "CHERRY-MX-LED"))
    )
    (comp (ref "KEY_127")
      (value "CHERRY-MX-LED")
      (footprint "eagle-import:CHERRY-MX-LED")
      (libsource (lib "eagle-import") (part "CHERRY-MX-LED"))
    )
    (comp (ref "KEY_128")
      (value "CHERRY-MX-LED")
      (footprint "eagle-import:CHERRY-MX-LED")
      (libsource (lib "eagle-import") (part "CHERRY-MX-LED"))
    )
    (comp (ref "KEY_129")
      (value "CHERRY-MX-LED")
      (footprint "eagle-import:CHERRY-MX-LED")
      (libsource (lib "eagle-import") (part "CHERRY-MX-LED"))
    )
    (comp (ref "KEY_130")
      (value "CHERRY-MX-LED")
      (footprint "eagle-import:CHERRY-MX-LED")
      (libsource (lib "eagle-import") (part "CHERRY-MX-LED"))
    )
    (comp (ref "KEY_131")
      (value "CHERRY-MX-LED")
      (footprint "eagle-import:CHERRY-MX-LED")
      (libsource (lib "eagle-import") (part "CHERRY-MX-LED"))
    )
    (comp (ref "KEY_132")
      (value "CHERRY-MX-LED")
      (footprint "eagle-import:CHERRY-MX-LED")
      (libsource (lib "eagle-import") (part "CHERRY-MX-LED"))
    )
    (comp (ref "KEY_133")
      (value "CHERRY-MX-LED")
      (footprint "eagle-import:CHERRY-MX-LED")
      (libsource (lib "eagle-import") (part "CHERRY-MX-LED"))
    )
    (comp (ref "KEY_134")
      (value "CHERRY-MX-LED")
      (footprint "eagle-import:CHERRY-MX-LED")
      (libsource (lib "eagle-import") (part "CHERRY-MX-LED"))
    )
    (comp (ref "KEY_135")
      (value "CHERRY-MX-LED")
      (footprint "eagle-import:CHERRY-MX-LED")
      (libsource (lib "eagle-import") (part "CHERRY-MX-LED"))
    )
    (comp (ref "KEY_136")
      (value "CHERRY-MX-LED")
      (footprint "eagle-import:CHERRY-MX-LED")
      (libsource (lib "eagle-import") (part "CHERRY-MX-LED"))
    )
    (comp (ref "KEY_137")
      (value "CHERRY-MX-LED")
      (footprint "eagle-import:CHERRY-MX-LED")
      (libsource (lib "eagle-import") (part "CHERRY-MX-LED"))
    )
    (comp (ref "KEY_138")
      (value "CHERRY-MX-LED")
      (footprint "eagle-import:CHERRY-MX-LED")
      (libsource (lib "eagle-import") (part "CHERRY-MX-LED"))
    )
    (comp (ref "KEY_139")
      (value "CHERRY-MX-LED")
      (footprint "eagle-import:CHERRY-MX-LED")
      (libsource (lib "eagle-import") (part "CHERRY-MX-LED"))
    )
    (comp (ref "KEY_140")
      (value "CHERRY-MX-LED")
      (footprint "eagle-import:CHERRY-MX-LED")
      (libsource (lib "eagle-import") (part "CHERRY-MX-LED"))
    )
    (comp (ref "KEY_141")
      (value "CHERRY-MX-LED")
      (footprint "eagle-import:CHERRY-MX-LED")
      (libsource (lib "eagle-import") (part "CHERRY-MX-LED"))
    )
    (comp (ref "KEY_142")
      (value "CHERRY-MX-LED")
      (footprint "eagle-import:CHERRY-MX-LED")
      (libsource (lib "eagle-import") (part "CHERRY-MX-LED"))
    )
    (comp (ref "KEY_143")
      (value "CHERRY-MX-LED")
      (footprint "eagle-import:CHERRY-MX-LED")
      (libsource (lib "eagle-import") (part "CHERRY-MX-LED"))
    )
    (comp (ref "KEY_144")
      (value "CHERRY-MX-LED")
      (footprint "eagle-import:CHERRY-MX-LED")
      (libsource (lib "eagle-import") (part "CHERRY-MX-LED"))
    )
    (comp (ref "KEY_145")
      (value "CHERRY-MX-LED")
      (footprint "eagle-import:CHERRY-MX-LED")
      (libsource (lib "eagle-import") (part "CHERRY-MX-LED"))
    )
    (comp (ref "KEY_146")
      (value "CHERRY-MX-LED")
      (footprint "eagle-import:CHERRY-MX-LED")
      (libsource (lib "eagle-import") (part "CHERRY-MX-LED"))
    )
    (comp (ref "KEY_147")
      (value "CHERRY-MX-LED")
      (footprint "eagle-import:CHERRY-MX-LED")
      (libsource (lib "eagle-import") (part "CHERRY-MX-LED"))
    )
    (comp (ref "KEY_148")
      (value "CHERRY-MX-LED")
      (footprint "eagle-import:CHERRY-MX-LED")
      (libsource (lib "eagle-import") (part "CHERRY-MX-LED"))
    )
    (comp (ref "KEY_149")
      (value "CHERRY-MX-LED")
      (footprint "eagle-import:CHERRY-MX-LED")
      (libsource (lib "eagle-import") (part "CHERRY-MX-LED"))
    )
    (comp (ref "KEY_150")
      (value "CHERRY-MX-LED")
      (footprint "eagle-import:CHERRY-MX-LED")
      (libsource (lib "eagle-import") (part "CHERRY-MX-LED"))
    )
    (comp (ref "KEY_151")
      (value "CHERRY-MX-LED")
      (footprint "eagle-import:CHERRY-MX-LED")
      (libsource (lib "eagle-import") (part "CHERRY-MX-LED"))
    )
    (comp (ref "KEY_152")
      (value "CHERRY-MX-LED")
      (footprint "eagle-import:CHERRY-MX-LED")
      (libsource (lib "eagle-import") (part "CHERRY-MX-LED"))
    )
    (comp (ref "KEY_153")
      (value "CHERRY-MX-LED")
      (footprint "eagle-import:CHERRY-MX-LED")
      (libsource (lib "eagle-import") (part "CHERRY-MX-LED"))
    )
    (comp (ref "SJ2")
      (value "SJW")
      (footprint "eagle-import:SJW")
      (libsource (lib "eagle-import") (part "SJW"))
    )
    (comp (ref "SJ3")
      (value "SJW")
      (footprint "eagle-import:SJW")
      (libsource (lib "eagle-import") (part "SJW"))
    )
    (comp (ref "SJ4")
      (value "SJW")
      (footprint "eagle-import:SJW")
      (libsource (lib "eagle-import") (part "SJW"))
    )
    (comp (ref "SJ5")
      (value "SJW")
      (footprint "eagle-import:SJW")
      (libsource (lib "eagle-import") (part "SJW"))
    )
    (comp (ref "SJ6")
      (value "SJW")
      (footprint "eagle-import:SJW")
      (libsource (lib "eagle-import") (part "SJW"))
    )
    (comp (ref "SJ7")
      (value "SJW")
      (footprint "eagle-import:SJW")
      (libsource (lib "eagle-import") (part "SJW"))
    )
    (comp (ref "SJ8")
      (value "SJW")
      (footprint "eagle-import:SJW")
      (libsource (lib "eagle-import") (part "SJW"))
    )
    (comp (ref "SJ9")
      (value "SJW")
      (footprint "eagle-import:SJW")
      (libsource (lib "eagle-import") (part "SJW"))
    )
    (comp (ref "SJ10")
      (value "SJW")
      (footprint "eagle-import:SJW")
      (libsource (lib "eagle-import") (part "SJW"))
    )
    (comp (ref "SJ11")
      (value "SJW")
      (footprint "eagle-import:SJW")
      (libsource (lib "eagle-import") (part "SJW"))
    )
    (comp (ref "SJ12")
      (value "SJW")
      (footprint "eagle-import:SJW")
      (libsource (lib "eagle-import") (part "SJW"))
    )
    (comp (ref "SJ13")
      (value "SJW")
      (footprint "eagle-import:SJW")
      (libsource (lib "eagle-import") (part "SJW"))
    )
    (comp (ref "SJ14")
      (value "SJW")
      (footprint "eagle-import:SJW")
      (libsource (lib "eagle-import") (part "SJW"))
    )
    (comp (ref "SJ15")
      (value "SJW")
      (footprint "eagle-import:SJW")
      (libsource (lib "eagle-import") (part "SJW"))
    )
    (comp (ref "SJ16")
      (value "SJW")
      (footprint "eagle-import:SJW")
      (libsource (lib "eagle-import") (part "SJW"))
    )
    (comp (ref "SJ17")
      (value "SJW")
      (footprint "eagle-import:SJW")
      (libsource (lib "eagle-import") (part "SJW"))
    )
    (comp (ref "SJ18")
      (value "SJW")
      (footprint "eagle-import:SJW")
      (libsource (lib "eagle-import") (part "SJW"))
    )
    (comp (ref "SJ19")
      (value "SJW")
      (footprint "eagle-import:SJW")
      (libsource (lib "eagle-import") (part "SJW"))
    )
    (comp (ref "SJ20")
      (value "SJW")
      (footprint "eagle-import:SJW")
      (libsource (lib "eagle-import") (part "SJW"))
    )
    (comp (ref "SJ21")
      (value "SJW")
      (footprint "eagle-import:SJW")
      (libsource (lib "eagle-import") (part "SJW"))
    )
    (comp (ref "SJ22")
      (value "SJW")
      (footprint "eagle-import:SJW")
      (libsource (lib "eagle-import") (part "SJW"))
    )
    (comp (ref "SJ23")
      (value "SJW")
      (footprint "eagle-import:SJW")
      (libsource (lib "eagle-import") (part "SJW"))
    )
    (comp (ref "SJ24")
      (value "SJW")
      (footprint "eagle-import:SJW")
      (libsource (lib "eagle-import") (part "SJW"))
    )
    (comp (ref "SJ25")
      (value "SJW")
      (footprint "eagle-import:SJW")
      (libsource (lib "eagle-import") (part "SJW"))
    )
    (comp (ref "SJ26")
      (value "SJW")
      (footprint "eagle-import:SJW")
      (libsource (lib "eagle-import") (part "SJW"))
    )
    (comp (ref "SJ27")
      (value "SJW")
      (footprint "eagle-import:SJW")
      (libsource (lib "eagle-import") (part "SJW"))
    )
    (comp (ref "SJ28")
      (value "SJW")
      (footprint "eagle-import:SJW")
      (libsource (lib "eagle-import") (part "SJW"))
    )
    (comp (ref "SJ29")
      (value "SJW")
      (footprint "eagle-import:SJW")
      (libsource (lib "eagle-import") (part "SJW"))
    )
    (comp (ref "SJ30")
      (value "SJW")
      (footprint "eagle-import:SJW")
      (libsource (lib "eagle-import") (part "SJW"))
    )
    (comp (ref "SJ31")
      (value "SJW")
      (footprint "eagle-import:SJW")
      (libsource (lib "eagle-import") (part "SJW"))
    )
    (comp (ref "SJ32")
      (value "SJW")
      (footprint "eagle-import:SJW")
      (libsource (lib "eagle-import") (part "SJW"))
    )
    (comp (ref "SJ33")
      (value "SJW")
      (footprint "eagle-import:SJW")
      (libsource (lib "eagle-import") (part "SJW"))
    )
    (comp (ref "SJ34")
      (value "SJW")
      (footprint "eagle-import:SJW")
      (libsource (lib "eagle-import") (part "SJW"))
    )
    (comp (ref "SJ35")
      (value "SJW")
      (footprint "eagle-import:SJW")
      (libsource (lib "eagle-import") (part "SJW"))
    )
    (comp (ref "SJ36")
      (value "SJW")
      (footprint "eagle-import:SJW")
      (libsource (lib "eagle-import") (part "SJW"))
    )
    (comp (ref "SJ37")
      (value "SJW")
      (footprint "eagle-import:SJW")
      (libsource (lib "eagle-import") (part "SJW"))
    )
    (comp (ref "SJ38")
      (value "SJW")
      (footprint "eagle-import:SJW")
      (libsource (lib "eagle-import") (part "SJW"))
    )
    (comp (ref "SJ39")
      (value "SJW")
      (footprint "eagle-import:SJW")
      (libsource (lib "eagle-import") (part "SJW"))
    )
    (comp (ref "SJ40")
      (value "SJW")
      (footprint "eagle-import:SJW")
      (libsource (lib "eagle-import") (part "SJW"))
    )
    (comp (ref "SJ41")
      (value "SJW")
      (footprint "eagle-import:SJW")
      (libsource (lib "eagle-import") (part "SJW"))
    )
    (comp (ref "SJ42")
      (value "SJW")
      (footprint "eagle-import:SJW")
      (libsource (lib "eagle-import") (part "SJW"))
    )
    (comp (ref "SJ43")
      (value "SJW")
      (footprint "eagle-import:SJW")
      (libsource (lib "eagle-import") (part "SJW"))
    )
    (comp (ref "SJ44")
      (value "SJW")
      (footprint "eagle-import:SJW")
      (libsource (lib "eagle-import") (part "SJW"))
    )
    (comp (ref "SJ45")
      (value "SJW")
      (footprint "eagle-import:SJW")
      (libsource (lib "eagle-import") (part "SJW"))
    )
    (comp (ref "SJ46")
      (value "SJW")
      (footprint "eagle-import:SJW")
      (libsource (lib "eagle-import") (part "SJW"))
    )
    (comp (ref "SJ47")
      (value "SJW")
      (footprint "eagle-import:SJW")
      (libsource (lib "eagle-import") (part "SJW"))
    )
    (comp (ref "SJ48")
      (value "SJW")
      (footprint "eagle-import:SJW")
      (libsource (lib "eagle-import") (part "SJW"))
    )
    (comp (ref "SJ49")
      (value "SJW")
      (footprint "eagle-import:SJW")
      (libsource (lib "eagle-import") (part "SJW"))
    )
    (comp (ref "SJ50")
      (value "SJW")
      (footprint "eagle-import:SJW")
      (libsource (lib "eagle-import") (part "SJW"))
    )
    (comp (ref "SJ51")
      (value "SJW")
      (footprint "eagle-import:SJW")
      (libsource (lib "eagle-import") (part "SJW"))
    )
    (comp (ref "SJ52")
      (value "SJW")
      (footprint "eagle-import:SJW")
      (libsource (lib "eagle-import") (part "SJW"))
    )
    (comp (ref "SJ53")
      (value "SJW")
      (footprint "eagle-import:SJW")
      (libsource (lib "eagle-import") (part "SJW"))
    )
    (comp (ref "SJ54")
      (value "SJW")
      (footprint "eagle-import:SJW")
      (libsource (lib "eagle-import") (part "SJW"))
    )
    (comp (ref "SJ55")
      (value "SJW")
      (footprint "eagle-import:SJW")
      (libsource (lib "eagle-import") (part "SJW"))
    )
    (comp (ref "SJ56")
      (value "SJW")
      (footprint "eagle-import:SJW")
      (libsource (lib "eagle-import") (part "SJW"))
    )
    (comp (ref "SJ57")
      (value "SJW")
      (footprint "eagle-import:SJW")
      (libsource (lib "eagle-import") (part "SJW"))
    )
    (comp (ref "SJ58")
      (value "SJW")
      (footprint "eagle-import:SJW")
      (libsource (lib "eagle-import") (part "SJW"))
    )
    (comp (ref "SJ59")
      (value "SJW")
      (footprint "eagle-import:SJW")
      (libsource (lib "eagle-import") (part "SJW"))
    )
    (comp (ref "SJ60")
      (value "SJW")
      (footprint "eagle-import:SJW")
      (libsource (lib "eagle-import") (part "SJW"))
    )
    (comp (ref "SJ61")
      (value "SJW")
      (footprint "eagle-import:SJW")
      (libsource (lib "eagle-import") (part "SJW"))
    )
    (comp (ref "SJ62")
      (value "SJW")
      (footprint "eagle-import:SJW")
      (libsource (lib "eagle-import") (part "SJW"))
    )
    (comp (ref "SJ63")
      (value "SJW")
      (footprint "eagle-import:SJW")
      (libsource (lib "eagle-import") (part "SJW"))
    )
    (comp (ref "SJ64")
      (value "SJW")
      (footprint "eagle-import:SJW")
      (libsource (lib "eagle-import") (part "SJW"))
    )
    (comp (ref "SJ65")
      (value "SJW")
      (footprint "eagle-import:SJW")
      (libsource (lib "eagle-import") (part "SJW"))
    )
    (comp (ref "SJ66")
      (value "SJW")
      (footprint "eagle-import:SJW")
      (libsource (lib "eagle-import") (part "SJW"))
    )
    (comp (ref "SJ67")
      (value "SJW")
      (footprint "eagle-import:SJW")
      (libsource (lib "eagle-import") (part "SJW"))
    )
    (comp (ref "SJ68")
      (value "SJW")
      (footprint "eagle-import:SJW")
      (libsource (lib "eagle-import") (part "SJW"))
    )
    (comp (ref "SJ69")
      (value "SJW")
      (footprint "eagle-import:SJW")
      (libsource (lib "eagle-import") (part "SJW"))
    )
    (comp (ref "SJ70")
      (value "SJW")
      (footprint "eagle-import:SJW")
      (libsource (lib "eagle-import") (part "SJW"))
    )
    (comp (ref "SJ71")
      (value "SJW")
      (footprint "eagle-import:SJW")
      (libsource (lib "eagle-import") (part "SJW"))
    )
    (comp (ref "SJ72")
      (value "SJW")
      (footprint "eagle-import:SJW")
      (libsource (lib "eagle-import") (part "SJW"))
    )
    (comp (ref "SJ73")
      (value "SJW")
      (footprint "eagle-import:SJW")
      (libsource (lib "eagle-import") (part "SJW"))
    )
    (comp (ref "SJ74")
      (value "SJW")
      (footprint "eagle-import:SJW")
      (libsource (lib "eagle-import") (part "SJW"))
    )
    (comp (ref "SJ75")
      (value "SJW")
      (footprint "eagle-import:SJW")
      (libsource (lib "eagle-import") (part "SJW"))
    )
    (comp (ref "SJ76")
      (value "SJW")
      (footprint "eagle-import:SJW")
      (libsource (lib "eagle-import") (part "SJW"))
    )
    (comp (ref "SJ77")
      (value "SJW")
      (footprint "eagle-import:SJW")
      (libsource (lib "eagle-import") (part "SJW"))
    )
    (comp (ref "SJ78")
      (value "SJW")
      (footprint "eagle-import:SJW")
      (libsource (lib "eagle-import") (part "SJW"))
    )
    (comp (ref "SJ79")
      (value "SJW")
      (footprint "eagle-import:SJW")
      (libsource (lib "eagle-import") (part "SJW"))
    )
    (comp (ref "SJ80")
      (value "SJW")
      (footprint "eagle-import:SJW")
      (libsource (lib "eagle-import") (part "SJW"))
    )
    (comp (ref "SJ81")
      (value "SJW")
      (footprint "eagle-import:SJW")
      (libsource (lib "eagle-import") (part "SJW"))
    )
    (comp (ref "SJ82")
      (value "SJW")
      (footprint "eagle-import:SJW")
      (libsource (lib "eagle-import") (part "SJW"))
    )
    (comp (ref "SJ83")
      (value "SJW")
      (footprint "eagle-import:SJW")
      (libsource (lib "eagle-import") (part "SJW"))
    )
    (comp (ref "SJ84")
      (value "SJW")
      (footprint "eagle-import:SJW")
      (libsource (lib "eagle-import") (part "SJW"))
    )
    (comp (ref "SJ85")
      (value "SJW")
      (footprint "eagle-import:SJW")
      (libsource (lib "eagle-import") (part "SJW"))
    )
    (comp (ref "SJ86")
      (value "SJW")
      (footprint "eagle-import:SJW")
      (libsource (lib "eagle-import") (part "SJW"))
    )
    (comp (ref "SJ87")
      (value "SJW")
      (footprint "eagle-import:SJW")
      (libsource (lib "eagle-import") (part "SJW"))
    )
  )
  (nets
    (net (code "32") (name "COL_1") (class "Default")
      (node (ref "SJ33") (pin "2") (pinfunction "2_2") (pintype "passive"))
      (node (ref "SJ_MCU_COL1") (pin "1") (pinfunction "1_1") (pintype "passive"))
    )
    (net (code "33") (name "COL_1_XFUNC") (class "Default")
      (node (ref "KEY_113") (pin "SW1") (pinfunction "SW1_SW1") (pintype "bidirectional"))
      (node (ref "KEY_133") (pin "SW1") (pinfunction "SW1_SW1") (pintype "bidirectional"))
      (node (ref "KEY_21") (pin "SW1") (pinfunction "SW1_SW1") (pintype "bidirectional"))
      (node (ref "KEY_45") (pin "SW1") (pinfunction "SW1_SW1") (pintype "bidirectional"))
      (node (ref "KEY_68") (pin "SW1") (pinfunction "SW1_SW1") (pintype "bidirectional"))
      (node (ref "KEY_91") (pin "SW1") (pinfunction "SW1_SW1") (pintype "bidirectional"))
      (node (ref "SJ2") (pin "1") (pinfunction "1_1") (pintype "passive"))
      (node (ref "SJ33") (pin "1") (pinfunction "1_1") (pintype "passive"))
    )
    (net (code "34") (name "COL_1_XFUNC_MACRO") (class "Default")
      (node (ref "KEY_1") (pin "SW1") (pinfunction "SW1_SW1") (pintype "bidirectional"))
      (node (ref "SJ2") (pin "2") (pinfunction "2_2") (pintype "passive"))
    )
    (net (code "35") (name "COL_1{MCU}") (class "Default")
      (node (ref "SJ_MCU_COL1") (pin "2") (pinfunction "2_2") (pintype "passive"))
      (node (ref "U1") (pin "1") (pinfunction "PTE0_1") (pintype "bidirectional"))
    )
    (net (code "36") (name "COL_2") (class "Default")
      (node (ref "SJ34") (pin "2") (pinfunction "2_2") (pintype "passive"))
      (node (ref "SJ_MCU_COL2") (pin "1") (pinfunction "1_1") (pintype "passive"))
    )
    (net (code "37") (name "COL_2_XFUNC") (class "Default")
      (node (ref "KEY_114") (pin "SW1") (pinfunction "SW1_SW1") (pintype "bidirectional"))
      (node (ref "KEY_134") (pin "SW1") (pinfunction "SW1_SW1") (pintype "bidirectional"))
      (node (ref "KEY_22") (pin "SW1") (pinfunction "SW1_SW1") (pintype "bidirectional"))
      (node (ref "KEY_46") (pin "SW1") (pinfunction "SW1_SW1") (pintype "bidirectional"))
      (node (ref "KEY_69") (pin "SW1") (pinfunction "SW1_SW1") (pintype "bidirectional"))
      (node (ref "KEY_92") (pin "SW1") (pinfunction "SW1_SW1") (pintype "bidirectional"))
      (node (ref "SJ3") (pin "1") (pinfunction "1_1") (pintype "passive"))
      (node (ref "SJ34") (pin "1") (pinfunction "1_1") (pintype "passive"))
    )
    (net (code "38") (name "COL_2_XFUNC_MACRO") (class "Default")
      (node (ref "KEY_2") (pin "SW1") (pinfunction "SW1_SW1") (pintype "bidirectional"))
      (node (ref "SJ3") (pin "2") (pinfunction "2_2") (pintype "passive"))
    )
    (net (code "39") (name "COL_2{MCU}") (class "Default")
      (node (ref "SJ_MCU_COL2") (pin "2") (pinfunction "2_2") (pintype "passive"))
      (node (ref "U1") (pin "2") (pinfunction "PTE1/LLWU_P0_2") (pintype "bidirectional"))
    )
    (net (code "40") (name "COL_3") (class "Default")
      (node (ref "KEY_115") (pin "SW1") (pinfunction "SW1_SW1") (pintype "bidirectional"))
      (node (ref "KEY_135") (pin "SW1") (pinfunction "SW1_SW1") (pintype "bidirectional"))
      (node (ref "KEY_23") (pin "SW1") (pinfunction "SW1_SW1") (pintype "bidirectional"))
      (node (ref "KEY_47") (pin "SW1") (pinfunction "SW1_SW1") (pintype "bidirectional"))
      (node (ref "KEY_70") (pin "SW1") (pinfunction "SW1_SW1") (pintype "bidirectional"))
      (node (ref "KEY_93") (pin "SW1") (pinfunction "SW1_SW1") (pintype "bidirectional"))
      (node (ref "SJ4") (pin "1") (pinfunction "1_1") (pintype "passive"))
      (node (ref "SJ_MCU_COL3") (pin "1") (pinfunction "1_1") (pintype "passive"))
    )
    (net (code "41") (name "COL_3_MACRO") (class "Default")
      (node (ref "KEY_3") (pin "SW1") (pinfunction "SW1_SW1") (pintype "bidirectional"))
      (node (ref "SJ4") (pin "2") (pinfunction "2_2") (pintype "passive"))
    )
    (net (code "42") (name "COL_3{MCU}") (class "Default")
      (node (ref "SJ_MCU_COL3") (pin "2") (pinfunction "2_2") (pintype "passive"))
      (node (ref "U1") (pin "144") (pinfunction "PTD15_144") (pintype "bidirectional"))
    )
    (net (code "43") (name "COL_4") (class "Default")
      (node (ref "KEY_116") (pin "SW1") (pinfunction "SW1_SW1") (pintype "bidirectional"))
      (node (ref "KEY_136") (pin "SW1") (pinfunction "SW1_SW1") (pintype "bidirectional"))
      (node (ref "KEY_24") (pin "SW1") (pinfunction "SW1_SW1") (pintype "bidirectional"))
      (node (ref "KEY_48") (pin "SW1") (pinfunction "SW1_SW1") (pintype "bidirectional"))
      (node (ref "KEY_71") (pin "SW1") (pinfunction "SW1_SW1") (pintype "bidirectional"))
      (node (ref "KEY_94") (pin "SW1") (pinfunction "SW1_SW1") (pintype "bidirectional"))
      (node (ref "SJ5") (pin "1") (pinfunction "1_1") (pintype "passive"))
      (node (ref "SJ_MCU_COL4") (pin "1") (pinfunction "1_1") (pintype "passive"))
    )
    (net (code "44") (name "COL_4_MACRO") (class "Default")
      (node (ref "KEY_4") (pin "SW1") (pinfunction "SW1_SW1") (pintype "bidirectional"))
      (node (ref "SJ5") (pin "2") (pinfunction "2_2") (pintype "passive"))
    )
    (net (code "45") (name "COL_4{MCU}") (class "Default")
      (node (ref "SJ_MCU_COL4") (pin "2") (pinfunction "2_2") (pintype "passive"))
      (node (ref "U1") (pin "143") (pinfunction "PTD14_143") (pintype "bidirectional"))
    )
    (net (code "46") (name "COL_5") (class "Default")
      (node (ref "KEY_117") (pin "SW1") (pinfunction "SW1_SW1") (pintype "bidirectional"))
      (node (ref "KEY_137") (pin "SW1") (pinfunction "SW1_SW1") (pintype "bidirectional"))
      (node (ref "KEY_25") (pin "SW1") (pinfunction "SW1_SW1") (pintype "bidirectional"))
      (node (ref "KEY_49") (pin "SW1") (pinfunction "SW1_SW1") (pintype "bidirectional"))
      (node (ref "KEY_72") (pin "SW1") (pinfunction "SW1_SW1") (pintype "bidirectional"))
      (node (ref "KEY_95") (pin "SW1") (pinfunction "SW1_SW1") (pintype "bidirectional"))
      (node (ref "SJ6") (pin "1") (pinfunction "1_1") (pintype "passive"))
      (node (ref "SJ_MCU_COL5") (pin "1") (pinfunction "1_1") (pintype "passive"))
    )
    (net (code "47") (name "COL_5_MACRO") (class "Default")
      (node (ref "KEY_5") (pin "SW1") (pinfunction "SW1_SW1") (pintype "bidirectional"))
      (node (ref "SJ6") (pin "2") (pinfunction "2_2") (pintype "passive"))
    )
    (net (code "48") (name "COL_5{MCU}") (class "Default")
      (node (ref "SJ_MCU_COL5") (pin "2") (pinfunction "2_2") (pintype "passive"))
      (node (ref "U1") (pin "142") (pinfunction "PTD13_142") (pintype "bidirectional"))
    )
    (net (code "49") (name "COL_6") (class "Default")
      (node (ref "KEY_118") (pin "SW1") (pinfunction "SW1_SW1") (pintype "bidirectional"))
      (node (ref "KEY_26") (pin "SW1") (pinfunction "SW1_SW1") (pintype "bidirectional"))
      (node (ref "KEY_50") (pin "SW1") (pinfunction "SW1_SW1") (pintype "bidirectional"))
      (node (ref "KEY_73") (pin "SW1") (pinfunction "SW1_SW1") (pintype "bidirectional"))
      (node (ref "KEY_96") (pin "SW1") (pinfunction "SW1_SW1") (pintype "bidirectional"))
      (node (ref "SJ7") (pin "1") (pinfunction "1_1") (pintype "passive"))
      (node (ref "SJ_MCU_COL6") (pin "1") (pinfunction "1_1") (pintype "passive"))
    )
    (net (code "50") (name "COL_6_MACRO") (class "Default")
      (node (ref "KEY_6") (pin "SW1") (pinfunction "SW1_SW1") (pintype "bidirectional"))
      (node (ref "SJ7") (pin "2") (pinfunction "2_2") (pintype "passive"))
    )
    (net (code "51") (name "COL_6{MCU}") (class "Default")
      (node (ref "SJ_MCU_COL6") (pin "2") (pinfunction "2_2") (pintype "passive"))
      (node (ref "U1") (pin "3") (pinfunction "PTE2/LLWU_P1_3") (pintype "bidirectional"))
    )
    (net (code "52") (name "COL_7") (class "Default")
      (node (ref "KEY_119") (pin "SW1") (pinfunction "SW1_SW1") (pintype "bidirectional"))
      (node (ref "KEY_27") (pin "SW1") (pinfunction "SW1_SW1") (pintype "bidirectional"))
      (node (ref "KEY_51") (pin "SW1") (pinfunction "SW1_SW1") (pintype "bidirectional"))
      (node (ref "KEY_74") (pin "SW1") (pinfunction "SW1_SW1") (pintype "bidirectional"))
      (node (ref "KEY_97") (pin "SW1") (pinfunction "SW1_SW1") (pintype "bidirectional"))
      (node (ref "SJ8") (pin "1") (pinfunction "1_1") (pintype "passive"))
      (node (ref "SJ_MCU_COL7") (pin "1") (pinfunction "1_1") (pintype "passive"))
    )
    (net (code "53") (name "COL_7_MACRO") (class "Default")
      (node (ref "KEY_7") (pin "SW1") (pinfunction "SW1_SW1") (pintype "bidirectional"))
      (node (ref "SJ8") (pin "2") (pinfunction "2_2") (pintype "passive"))
    )
    (net (code "54") (name "COL_7{MCU}") (class "Default")
      (node (ref "SJ_MCU_COL7") (pin "2") (pinfunction "2_2") (pintype "passive"))
      (node (ref "U1") (pin "4") (pinfunction "PTE3_4") (pintype "bidirectional"))
    )
    (net (code "55") (name "COL_8") (class "Default")
      (node (ref "KEY_120") (pin "SW1") (pinfunction "SW1_SW1") (pintype "bidirectional"))
      (node (ref "KEY_138") (pin "SW1") (pinfunction "SW1_SW1") (pintype "bidirectional"))
      (node (ref "KEY_28") (pin "SW1") (pinfunction "SW1_SW1") (pintype "bidirectional"))
      (node (ref "KEY_52") (pin "SW1") (pinfunction "SW1_SW1") (pintype "bidirectional"))
      (node (ref "KEY_75") (pin "SW1") (pinfunction "SW1_SW1") (pintype "bidirectional"))
      (node (ref "KEY_98") (pin "SW1") (pinfunction "SW1_SW1") (pintype "bidirectional"))
      (node (ref "SJ9") (pin "1") (pinfunction "1_1") (pintype "passive"))
      (node (ref "SJ_MCU_COL8") (pin "1") (pinfunction "1_1") (pintype "passive"))
    )
    (net (code "56") (name "COL_8_MACRO") (class "Default")
      (node (ref "KEY_8") (pin "SW1") (pinfunction "SW1_SW1") (pintype "bidirectional"))
      (node (ref "SJ9") (pin "2") (pinfunction "2_2") (pintype "passive"))
    )
    (net (code "57") (name "COL_8{MCU}") (class "Default")
      (node (ref "SJ_MCU_COL8") (pin "2") (pinfunction "2_2") (pintype "passive"))
      (node (ref "U1") (pin "141") (pinfunction "PTD12_141") (pintype "bidirectional"))
    )
    (net (code "58") (name "COL_9") (class "Default")
      (node (ref "KEY_121") (pin "SW1") (pinfunction "SW1_SW1") (pintype "bidirectional"))
      (node (ref "KEY_29") (pin "SW1") (pinfunction "SW1_SW1") (pintype "bidirectional"))
      (node (ref "KEY_53") (pin "SW1") (pinfunction "SW1_SW1") (pintype "bidirectional"))
      (node (ref "KEY_76") (pin "SW1") (pinfunction "SW1_SW1") (pintype "bidirectional"))
      (node (ref "KEY_99") (pin "SW1") (pinfunction "SW1_SW1") (pintype "bidirectional"))
      (node (ref "SJ10") (pin "1") (pinfunction "1_1") (pintype "passive"))
      (node (ref "SJ_MCU_COL9") (pin "1") (pinfunction "1_1") (pintype "passive"))
    )
    (net (code "59") (name "COL_9_MACRO") (class "Default")
      (node (ref "KEY_9") (pin "SW1") (pinfunction "SW1_SW1") (pintype "bidirectional"))
      (node (ref "SJ10") (pin "2") (pinfunction "2_2") (pintype "passive"))
    )
    (net (code "60") (name "COL_9{MCU}") (class "Default")
      (node (ref "SJ_MCU_COL9") (pin "2") (pinfunction "2_2") (pintype "passive"))
      (node (ref "U1") (pin "140") (pinfunction "PTD11_140") (pintype "bidirectional"))
    )
    (net (code "61") (name "COL_10") (class "Default")
      (node (ref "KEY_100") (pin "SW1") (pinfunction "SW1_SW1") (pintype "bidirectional"))
      (node (ref "KEY_122") (pin "SW1") (pinfunction "SW1_SW1") (pintype "bidirectional"))
      (node (ref "KEY_30") (pin "SW1") (pinfunction "SW1_SW1") (pintype "bidirectional"))
      (node (ref "KEY_30_OFFSET") (pin "SW1") (pinfunction "SW1_SW1") (pintype "bidirectional"))
      (node (ref "KEY_54") (pin "SW1") (pinfunction "SW1_SW1") (pintype "bidirectional"))
      (node (ref "KEY_77") (pin "SW1") (pinfunction "SW1_SW1") (pintype "bidirectional"))
      (node (ref "SJ11") (pin "1") (pinfunction "1_1") (pintype "passive"))
      (node (ref "SJ_MCU_COL10") (pin "1") (pinfunction "1_1") (pintype "passive"))
    )
    (net (code "62") (name "COL_10_MACRO") (class "Default")
      (node (ref "KEY_10") (pin "SW1") (pinfunction "SW1_SW1") (pintype "bidirectional"))
      (node (ref "SJ11") (pin "2") (pinfunction "2_2") (pintype "passive"))
    )
    (net (code "63") (name "COL_10{MCU}") (class "Default")
      (node (ref "SJ_MCU_COL10") (pin "2") (pinfunction "2_2") (pintype "passive"))
      (node (ref "U1") (pin "139") (pinfunction "PTD10_139") (pintype "bidirectional"))
    )
    (net (code "64") (name "COL_11") (class "Default")
      (node (ref "KEY_101") (pin "SW1") (pinfunction "SW1_SW1") (pintype "bidirectional"))
      (node (ref "KEY_123") (pin "SW1") (pinfunction "SW1_SW1") (pintype "bidirectional"))
      (node (ref "KEY_31") (pin "SW1") (pinfunction "SW1_SW1") (pintype "bidirectional"))
      (node (ref "KEY_31_OFFSET") (pin "SW1") (pinfunction "SW1_SW1") (pintype "bidirectional"))
      (node (ref "KEY_55") (pin "SW1") (pinfunction "SW1_SW1") (pintype "bidirectional"))
      (node (ref "KEY_78") (pin "SW1") (pinfunction "SW1_SW1") (pintype "bidirectional"))
      (node (ref "SJ12") (pin "1") (pinfunction "1_1") (pintype "passive"))
      (node (ref "SJ_MCU_COL11") (pin "1") (pinfunction "1_1") (pintype "passive"))
    )
    (net (code "65") (name "COL_11_MACRO") (class "Default")
      (node (ref "KEY_11") (pin "SW1") (pinfunction "SW1_SW1") (pintype "bidirectional"))
      (node (ref "SJ12") (pin "2") (pinfunction "2_2") (pintype "passive"))
    )
    (net (code "66") (name "COL_11{MCU}") (class "Default")
      (node (ref "SJ_MCU_COL11") (pin "2") (pinfunction "2_2") (pintype "passive"))
      (node (ref "U1") (pin "138") (pinfunction "PTD9_138") (pintype "bidirectional"))
    )
    (net (code "67") (name "COL_12") (class "Default")
      (node (ref "KEY_102") (pin "SW1") (pinfunction "SW1_SW1") (pintype "bidirectional"))
      (node (ref "KEY_124") (pin "SW1") (pinfunction "SW1_SW1") (pintype "bidirectional"))
      (node (ref "KEY_139") (pin "SW1") (pinfunction "SW1_SW1") (pintype "bidirectional"))
      (node (ref "KEY_32") (pin "SW1") (pinfunction "SW1_SW1") (pintype "bidirectional"))
      (node (ref "KEY_32_OFFSET") (pin "SW1") (pinfunction "SW1_SW1") (pintype "bidirectional"))
      (node (ref "KEY_56") (pin "SW1") (pinfunction "SW1_SW1") (pintype "bidirectional"))
      (node (ref "KEY_79") (pin "SW1") (pinfunction "SW1_SW1") (pintype "bidirectional"))
      (node (ref "SJ13") (pin "1") (pinfunction "1_1") (pintype "passive"))
      (node (ref "SJ_MCU_COL12") (pin "1") (pinfunction "1_1") (pintype "passive"))
    )
    (net (code "68") (name "COL_12_MACRO") (class "Default")
      (node (ref "KEY_12") (pin "SW1") (pinfunction "SW1_SW1") (pintype "bidirectional"))
      (node (ref "SJ13") (pin "2") (pinfunction "2_2") (pintype "passive"))
    )
    (net (code "69") (name "COL_12{MCU}") (class "Default")
      (node (ref "SJ_MCU_COL12") (pin "2") (pinfunction "2_2") (pintype "passive"))
      (node (ref "U1") (pin "137") (pinfunction "PTD8_137") (pintype "bidirectional"))
    )
    (net (code "70") (name "COL_13") (class "Default")
      (node (ref "KEY_103") (pin "SW1") (pinfunction "SW1_SW1") (pintype "bidirectional"))
      (node (ref "KEY_125") (pin "SW1") (pinfunction "SW1_SW1") (pintype "bidirectional"))
      (node (ref "KEY_140") (pin "SW1") (pinfunction "SW1_SW1") (pintype "bidirectional"))
      (node (ref "KEY_33") (pin "SW1") (pinfunction "SW1_SW1") (pintype "bidirectional"))
      (node (ref "KEY_33_OFFSET") (pin "SW1") (pinfunction "SW1_SW1") (pintype "bidirectional"))
      (node (ref "KEY_57") (pin "SW1") (pinfunction "SW1_SW1") (pintype "bidirectional"))
      (node (ref "KEY_80") (pin "SW1") (pinfunction "SW1_SW1") (pintype "bidirectional"))
      (node (ref "SJ14") (pin "1") (pinfunction "1_1") (pintype "passive"))
      (node (ref "SJ_MCU_COL13") (pin "1") (pinfunction "1_1") (pintype "passive"))
    )
    (net (code "71") (name "COL_13_MACRO") (class "Default")
      (node (ref "KEY_13") (pin "SW1") (pinfunction "SW1_SW1") (pintype "bidirectional"))
      (node (ref "SJ14") (pin "2") (pinfunction "2_2") (pintype "passive"))
    )
    (net (code "72") (name "COL_13{MCU}") (class "Default")
      (node (ref "SJ_MCU_COL13") (pin "2") (pinfunction "2_2") (pintype "passive"))
      (node (ref "U1") (pin "136") (pinfunction "PTD7_136") (pintype "bidirectional"))
    )
    (net (code "73") (name "COL_14") (class "Default")
      (node (ref "KEY_104") (pin "SW1") (pinfunction "SW1_SW1") (pintype "bidirectional"))
      (node (ref "KEY_141") (pin "SW1") (pinfunction "SW1_SW1") (pintype "bidirectional"))
      (node (ref "KEY_34") (pin "SW1") (pinfunction "SW1_SW1") (pintype "bidirectional"))
      (node (ref "KEY_58") (pin "SW1") (pinfunction "SW1_SW1") (pintype "bidirectional"))
      (node (ref "KEY_81") (pin "SW1") (pinfunction "SW1_SW1") (pintype "bidirectional"))
      (node (ref "SJ15") (pin "1") (pinfunction "1_1") (pintype "passive"))
      (node (ref "SJ_MCU_COL14") (pin "1") (pinfunction "1_1") (pintype "passive"))
    )
    (net (code "74") (name "COL_14_MACRO") (class "Default")
      (node (ref "KEY_14") (pin "SW1") (pinfunction "SW1_SW1") (pintype "bidirectional"))
      (node (ref "SJ15") (pin "2") (pinfunction "2_2") (pintype "passive"))
    )
    (net (code "75") (name "COL_14{MCU}") (class "Default")
      (node (ref "SJ_MCU_COL14") (pin "2") (pinfunction "2_2") (pintype "passive"))
      (node (ref "U1") (pin "133") (pinfunction "PTD6/LLWU_P15_133") (pintype "bidirectional"))
    )
    (net (code "76") (name "COL_15") (class "Default")
      (node (ref "KEY_35") (pin "SW1") (pinfunction "SW1_SW1") (pintype "bidirectional"))
      (node (ref "KEY_59") (pin "SW1") (pinfunction "SW1_SW1") (pintype "bidirectional"))
      (node (ref "KEY_82") (pin "SW1") (pinfunction "SW1_SW1") (pintype "bidirectional"))
      (node (ref "SJ16") (pin "1") (pinfunction "1_1") (pintype "passive"))
      (node (ref "SJ_MCU_COL15") (pin "1") (pinfunction "1_1") (pintype "passive"))
    )
    (net (code "77") (name "COL_15_MACRO") (class "Default")
      (node (ref "KEY_15") (pin "SW1") (pinfunction "SW1_SW1") (pintype "bidirectional"))
      (node (ref "SJ16") (pin "2") (pinfunction "2_2") (pintype "passive"))
    )
    (net (code "78") (name "COL_15{MCU}") (class "Default")
      (node (ref "SJ_MCU_COL15") (pin "2") (pinfunction "2_2") (pintype "passive"))
      (node (ref "U1") (pin "132") (pinfunction "PTD5_132") (pintype "bidirectional"))
    )
    (net (code "79") (name "COL_16") (class "Default")
      (node (ref "KEY_36") (pin "SW1") (pinfunction "SW1_SW1") (pintype "bidirectional"))
      (node (ref "SJ17") (pin "1") (pinfunction "1_1") (pintype "passive"))
      (node (ref "SJ_MCU_COL16") (pin "1") (pinfunction "1_1") (pintype "passive"))
    )
    (net (code "80") (name "COL_16_MACRO") (class "Default")
      (node (ref "KEY_16") (pin "SW1") (pinfunction "SW1_SW1") (pintype "bidirectional"))
      (node (ref "SJ17") (pin "2") (pinfunction "2_2") (pintype "passive"))
    )
    (net (code "81") (name "COL_16{MCU}") (class "Default")
      (node (ref "SJ_MCU_COL16") (pin "2") (pinfunction "2_2") (pintype "passive"))
      (node (ref "U1") (pin "7") (pinfunction "PTE4/LLWU_P2_7") (pintype "bidirectional"))
    )
    (net (code "82") (name "COL_17") (class "Default")
      (node (ref "KEY_105") (pin "SW1") (pinfunction "SW1_SW1") (pintype "bidirectional"))
      (node (ref "KEY_126") (pin "SW1") (pinfunction "SW1_SW1") (pintype "bidirectional"))
      (node (ref "KEY_142") (pin "SW1") (pinfunction "SW1_SW1") (pintype "bidirectional"))
      (node (ref "KEY_37") (pin "SW1") (pinfunction "SW1_SW1") (pintype "bidirectional"))
      (node (ref "KEY_60") (pin "SW1") (pinfunction "SW1_SW1") (pintype "bidirectional"))
      (node (ref "KEY_83") (pin "SW1") (pinfunction "SW1_SW1") (pintype "bidirectional"))
      (node (ref "SJ18") (pin "1") (pinfunction "1_1") (pintype "passive"))
      (node (ref "SJ_MCU_COL17") (pin "1") (pinfunction "1_1") (pintype "passive"))
    )
    (net (code "83") (name "COL_17_MACRO") (class "Default")
      (node (ref "KEY_17") (pin "SW1") (pinfunction "SW1_SW1") (pintype "bidirectional"))
      (node (ref "SJ18") (pin "2") (pinfunction "2_2") (pintype "passive"))
    )
    (net (code "84") (name "COL_17{MCU}") (class "Default")
      (node (ref "SJ_MCU_COL17") (pin "2") (pinfunction "2_2") (pintype "passive"))
      (node (ref "U1") (pin "131") (pinfunction "PTD4/LLWU_P14_131") (pintype "bidirectional"))
    )
    (net (code "85") (name "COL_18") (class "Default")
      (node (ref "KEY_106") (pin "SW1") (pinfunction "SW1_SW1") (pintype "bidirectional"))
      (node (ref "KEY_127") (pin "SW1") (pinfunction "SW1_SW1") (pintype "bidirectional"))
      (node (ref "KEY_143") (pin "SW1") (pinfunction "SW1_SW1") (pintype "bidirectional"))
      (node (ref "KEY_38") (pin "SW1") (pinfunction "SW1_SW1") (pintype "bidirectional"))
      (node (ref "KEY_61") (pin "SW1") (pinfunction "SW1_SW1") (pintype "bidirectional"))
      (node (ref "KEY_84") (pin "SW1") (pinfunction "SW1_SW1") (pintype "bidirectional"))
      (node (ref "SJ19") (pin "1") (pinfunction "1_1") (pintype "passive"))
      (node (ref "SJ_MCU_COL18") (pin "1") (pinfunction "1_1") (pintype "passive"))
    )
    (net (code "86") (name "COL_18_MACRO") (class "Default")
      (node (ref "KEY_18") (pin "SW1") (pinfunction "SW1_SW1") (pintype "bidirectional"))
      (node (ref "SJ19") (pin "2") (pinfunction "2_2") (pintype "passive"))
    )
    (net (code "87") (name "COL_18{MCU}") (class "Default")
      (node (ref "SJ_MCU_COL18") (pin "2") (pinfunction "2_2") (pintype "passive"))
      (node (ref "U1") (pin "66") (pinfunction "PTA14_66") (pintype "bidirectional"))
    )
    (net (code "88") (name "COL_19") (class "Default")
      (node (ref "KEY_107") (pin "SW1") (pinfunction "SW1_SW1") (pintype "bidirectional"))
      (node (ref "KEY_128") (pin "SW1") (pinfunction "SW1_SW1") (pintype "bidirectional"))
      (node (ref "KEY_144") (pin "SW1") (pinfunction "SW1_SW1") (pintype "bidirectional"))
      (node (ref "KEY_39") (pin "SW1") (pinfunction "SW1_SW1") (pintype "bidirectional"))
      (node (ref "KEY_62") (pin "SW1") (pinfunction "SW1_SW1") (pintype "bidirectional"))
      (node (ref "KEY_85") (pin "SW1") (pinfunction "SW1_SW1") (pintype "bidirectional"))
      (node (ref "SJ20") (pin "1") (pinfunction "1_1") (pintype "passive"))
      (node (ref "SJ_MCU_COL19") (pin "1") (pinfunction "1_1") (pintype "passive"))
    )
    (net (code "89") (name "COL_19_MACRO") (class "Default")
      (node (ref "KEY_19") (pin "SW1") (pinfunction "SW1_SW1") (pintype "bidirectional"))
      (node (ref "SJ20") (pin "2") (pinfunction "2_2") (pintype "passive"))
    )
    (net (code "90") (name "COL_19{MCU}") (class "Default")
      (node (ref "SJ_MCU_COL19") (pin "2") (pinfunction "2_2") (pintype "passive"))
      (node (ref "U1") (pin "64") (pinfunction "PTA12_64") (pintype "bidirectional"))
    )
    (net (code "91") (name "COL_20") (class "Default")
      (node (ref "KEY_108") (pin "SW1") (pinfunction "SW1_SW1") (pintype "bidirectional"))
      (node (ref "KEY_129") (pin "SW1") (pinfunction "SW1_SW1") (pintype "bidirectional"))
      (node (ref "KEY_145") (pin "SW1") (pinfunction "SW1_SW1") (pintype "bidirectional"))
      (node (ref "KEY_40") (pin "SW1") (pinfunction "SW1_SW1") (pintype "bidirectional"))
      (node (ref "KEY_63") (pin "SW1") (pinfunction "SW1_SW1") (pintype "bidirectional"))
      (node (ref "KEY_86") (pin "SW1") (pinfunction "SW1_SW1") (pintype "bidirectional"))
      (node (ref "SJ21") (pin "1") (pinfunction "1_1") (pintype "passive"))
      (node (ref "SJ_MCU_COL20") (pin "1") (pinfunction "1_1") (pintype "passive"))
    )
    (net (code "92") (name "COL_20_MACRO") (class "Default")
      (node (ref "KEY_20") (pin "SW1") (pinfunction "SW1_SW1") (pintype "bidirectional"))
      (node (ref "SJ21") (pin "2") (pinfunction "2_2") (pintype "passive"))
    )
    (net (code "93") (name "COL_20{MCU}") (class "Default")
      (node (ref "SJ_MCU_COL20") (pin "2") (pinfunction "2_2") (pintype "passive"))
      (node (ref "U1") (pin "59") (pinfunction "PTA7_59") (pintype "bidirectional"))
    )
    (net (code "94") (name "COL_21") (class "Default")
      (node (ref "KEY_109") (pin "SW1") (pinfunction "SW1_SW1") (pintype "bidirectional"))
      (node (ref "KEY_130") (pin "SW1") (pinfunction "SW1_SW1") (pintype "bidirectional"))
      (node (ref "KEY_146") (pin "SW1") (pinfunction "SW1_SW1") (pintype "bidirectional"))
      (node (ref "KEY_41") (pin "SW1") (pinfunction "SW1_SW1") (pintype "bidirectional"))
      (node (ref "KEY_64") (pin "SW1") (pinfunction "SW1_SW1") (pintype "bidirectional"))
      (node (ref "KEY_87") (pin "SW1") (pinfunction "SW1_SW1") (pintype "bidirectional"))
      (node (ref "SJ22") (pin "1") (pinfunction "1_1") (pintype "passive"))
      (node (ref "SJ_MCU_COL21") (pin "1") (pinfunction "1_1") (pintype "passive"))
    )
    (net (code "95") (name "COL_21_MACRO") (class "Default")
      (node (ref "KEY_150") (pin "SW1") (pinfunction "SW1_SW1") (pintype "bidirectional"))
      (node (ref "SJ22") (pin "2") (pinfunction "2_2") (pintype "passive"))
    )
    (net (code "96") (name "COL_21{MCU}") (class "Default")
      (node (ref "SJ_MCU_COL21") (pin "2") (pinfunction "2_2") (pintype "passive"))
      (node (ref "U1") (pin "58") (pinfunction "PTA6_58") (pintype "bidirectional"))
    )
    (net (code "97") (name "COL_22") (class "Default")
      (node (ref "KEY_110") (pin "SW1") (pinfunction "SW1_SW1") (pintype "bidirectional"))
      (node (ref "KEY_131") (pin "SW1") (pinfunction "SW1_SW1") (pintype "bidirectional"))
      (node (ref "KEY_147") (pin "SW1") (pinfunction "SW1_SW1") (pintype "bidirectional"))
      (node (ref "KEY_42") (pin "SW1") (pinfunction "SW1_SW1") (pintype "bidirectional"))
      (node (ref "KEY_65") (pin "SW1") (pinfunction "SW1_SW1") (pintype "bidirectional"))
      (node (ref "KEY_88") (pin "SW1") (pinfunction "SW1_SW1") (pintype "bidirectional"))
      (node (ref "SJ23") (pin "1") (pinfunction "1_1") (pintype "passive"))
      (node (ref "SJ_MCU_COL22") (pin "1") (pinfunction "1_1") (pintype "passive"))
    )
    (net (code "98") (name "COL_22_MACRO") (class "Default")
      (node (ref "KEY_151") (pin "SW1") (pinfunction "SW1_SW1") (pintype "bidirectional"))
      (node (ref "SJ23") (pin "2") (pinfunction "2_2") (pintype "passive"))
    )
    (net (code "99") (name "COL_22{MCU}") (class "Default")
      (node (ref "SJ_MCU_COL22") (pin "2") (pinfunction "2_2") (pintype "passive"))
      (node (ref "U1") (pin "55") (pinfunction "PTA5_55") (pintype "bidirectional"))
    )
    (net (code "100") (name "COL_23") (class "Default")
      (node (ref "KEY_111") (pin "SW1") (pinfunction "SW1_SW1") (pintype "bidirectional"))
      (node (ref "KEY_132") (pin "SW1") (pinfunction "SW1_SW1") (pintype "bidirectional"))
      (node (ref "KEY_148") (pin "SW1") (pinfunction "SW1_SW1") (pintype "bidirectional"))
      (node (ref "KEY_43") (pin "SW1") (pinfunction "SW1_SW1") (pintype "bidirectional"))
      (node (ref "KEY_66") (pin "SW1") (pinfunction "SW1_SW1") (pintype "bidirectional"))
      (node (ref "KEY_89") (pin "SW1") (pinfunction "SW1_SW1") (pintype "bidirectional"))
      (node (ref "SJ24") (pin "1") (pinfunction "1_1") (pintype "passive"))
      (node (ref "SJ_MCU_COL23") (pin "1") (pinfunction "1_1") (pintype "passive"))
    )
    (net (code "101") (name "COL_23_MACRO") (class "Default")
      (node (ref "KEY_152") (pin "SW1") (pinfunction "SW1_SW1") (pintype "bidirectional"))
      (node (ref "SJ24") (pin "2") (pinfunction "2_2") (pintype "passive"))
    )
    (net (code "102") (name "COL_23{MCU}") (class "Default")
      (node (ref "SJ_MCU_COL23") (pin "2") (pinfunction "2_2") (pintype "passive"))
      (node (ref "U1") (pin "48") (pinfunction "PTE27_48") (pintype "bidirectional"))
    )
    (net (code "103") (name "COL_24") (class "Default")
      (node (ref "KEY_112") (pin "SW1") (pinfunction "SW1_SW1") (pintype "bidirectional"))
      (node (ref "KEY_149") (pin "SW1") (pinfunction "SW1_SW1") (pintype "bidirectional"))
      (node (ref "KEY_44") (pin "SW1") (pinfunction "SW1_SW1") (pintype "bidirectional"))
      (node (ref "KEY_67") (pin "SW1") (pinfunction "SW1_SW1") (pintype "bidirectional"))
      (node (ref "KEY_90") (pin "SW1") (pinfunction "SW1_SW1") (pintype "bidirectional"))
      (node (ref "SJ25") (pin "1") (pinfunction "1_1") (pintype "passive"))
      (node (ref "SJ_MCU_COL24") (pin "1") (pinfunction "1_1") (pintype "passive"))
    )
    (net (code "104") (name "COL_24_MACRO") (class "Default")
      (node (ref "KEY_153") (pin "SW1") (pinfunction "SW1_SW1") (pintype "bidirectional"))
      (node (ref "SJ25") (pin "2") (pinfunction "2_2") (pintype "passive"))
    )
    (net (code "105") (name "COL_24{MCU}") (class "Default")
      (node (ref "SJ_MCU_COL24") (pin "2") (pinfunction "2_2") (pintype "passive"))
      (node (ref "U1") (pin "47") (pinfunction "PTE26_47") (pintype "bidirectional"))
    )
    (net (code "106") (name "EXTAL") (class "Default")
      (node (ref "C11") (pin "2") (pinfunction "2_2") (pintype "passive"))
      (node (ref "U1") (pin "72") (pinfunction "PTA18_72") (pintype "bidirectional"))
      (node (ref "Y1") (pin "3") (pinfunction "3_3") (pintype "passive"))
    )
    (net (code "107") (name "EXTAL32") (class "Default")
      (node (ref "C24") (pin "1") (pinfunction "1_1") (pintype "passive"))
      (node (ref "U1") (pin "41") (pinfunction "EXTAL32_41") (pintype "passive"))
      (node (ref "Y2") (pin "1") (pinfunction "1_1") (pintype "passive"))
    )
    (net (code "108") (name "FTM3_CH4") (class "Default")
      (node (ref "J3") (pin "7") (pinfunction "P$7_7") (pintype "bidirectional"))
      (node (ref "U1") (pin "113") (pinfunction "PTC8_113") (pintype "bidirectional"))
    )
    (net (code "109") (name "GND") (class "Default")
      (node (ref "C1") (pin "2") (pinfunction "2_2") (pintype "passive"))
      (node (ref "C10") (pin "1") (pinfunction "1_1") (pintype "passive"))
      (node (ref "C11") (pin "1") (pinfunction "1_1") (pintype "passive"))
      (node (ref "C12") (pin "2") (pinfunction "2_2") (pintype "passive"))
      (node (ref "C13") (pin "2") (pinfunction "2_2") (pintype "passive"))
      (node (ref "C14") (pin "2") (pinfunction "2_2") (pintype "passive"))
      (node (ref "C15") (pin "2") (pinfunction "2_2") (pintype "passive"))
      (node (ref "C16") (pin "2") (pinfunction "2_2") (pintype "passive"))
      (node (ref "C17") (pin "2") (pinfunction "2_2") (pintype "passive"))
      (node (ref "C18") (pin "2") (pinfunction "2_2") (pintype "passive"))
      (node (ref "C19") (pin "2") (pinfunction "2_2") (pintype "passive"))
      (node (ref "C2") (pin "2") (pinfunction "2_2") (pintype "passive"))
      (node (ref "C20") (pin "2") (pinfunction "2_2") (pintype "passive"))
      (node (ref "C21") (pin "2") (pinfunction "2_2") (pintype "passive"))
      (node (ref "C22") (pin "2") (pinfunction "2_2") (pintype "passive"))
      (node (ref "C23") (pin "-") (pinfunction "-_-") (pintype "passive"))
      (node (ref "C24") (pin "2") (pinfunction "2_2") (pintype "passive"))
      (node (ref "C25") (pin "2") (pinfunction "2_2") (pintype "passive"))
      (node (ref "C3") (pin "2") (pinfunction "2_2") (pintype "passive"))
      (node (ref "C4") (pin "2") (pinfunction "2_2") (pintype "passive"))
      (node (ref "C5") (pin "1") (pinfunction "1_1") (pintype "passive"))
      (node (ref "C6") (pin "1") (pinfunction "1_1") (pintype "passive"))
      (node (ref "C7") (pin "1") (pinfunction "1_1") (pintype "passive"))
      (node (ref "C8") (pin "2") (pinfunction "2_2") (pintype "passive"))
      (node (ref "C9") (pin "1") (pinfunction "1_1") (pintype "passive"))
      (node (ref "GND1") (pin "TP") (pinfunction "TP_TP") (pintype "input"))
      (node (ref "GND2") (pin "TP") (pinfunction "TP_TP") (pintype "input"))
      (node (ref "GND3") (pin "TP") (pinfunction "TP_TP") (pintype "input"))
      (node (ref "GND4") (pin "TP") (pinfunction "TP_TP") (pintype "input"))
      (node (ref "H1") (pin "HOLE") (pinfunction "HOLE_HOLE") (pintype "bidirectional"))
      (node (ref "H2") (pin "HOLE") (pinfunction "HOLE_HOLE") (pintype "bidirectional"))
      (node (ref "H3") (pin "HOLE") (pinfunction "HOLE_HOLE") (pintype "bidirectional"))
      (node (ref "H4") (pin "HOLE") (pinfunction "HOLE_HOLE") (pintype "bidirectional"))
      (node (ref "H5") (pin "HOLE") (pinfunction "HOLE_HOLE") (pintype "bidirectional"))
      (node (ref "H6") (pin "HOLE") (pinfunction "HOLE_HOLE") (pintype "bidirectional"))
      (node (ref "H7") (pin "HOLE") (pinfunction "HOLE_HOLE") (pintype "bidirectional"))
      (node (ref "H8") (pin "HOLE") (pinfunction "HOLE_HOLE") (pintype "bidirectional"))
      (node (ref "H9") (pin "HOLE") (pinfunction "HOLE_HOLE") (pintype "bidirectional"))
      (node (ref "J1") (pin "A1_B12") (pinfunction "GND_A1_B12") (pintype "power_in"))
      (node (ref "J1") (pin "B1_A12") (pinfunction "GND_B1_A12") (pintype "power_in"))
      (node (ref "J2") (pin "3") (pinfunction "GND_3") (pintype "bidirectional"))
      (node (ref "J2") (pin "5") (pinfunction "GND2_5") (pintype "bidirectional"))
      (node (ref "J3") (pin "2") (pinfunction "P$2_2") (pintype "bidirectional"))
      (node (ref "L2") (pin "2") (pinfunction "2_2") (pintype "bidirectional"))
      (node (ref "R12") (pin "1") (pinfunction "1_1") (pintype "passive"))
      (node (ref "R13") (pin "2") (pinfunction "2_2") (pintype "passive"))
      (node (ref "R4") (pin "1") (pinfunction "1_1") (pintype "passive"))
      (node (ref "R8") (pin "2") (pinfunction "2_2") (pintype "passive"))
      (node (ref "R9") (pin "2") (pinfunction "2_2") (pintype "passive"))
      (node (ref "SV1") (pin "4") (pinfunction "4_4") (pintype "passive"))
      (node (ref "SW1") (pin "3") (pinfunction "3_3") (pintype "passive"))
      (node (ref "SW1") (pin "4") (pinfunction "4_4") (pintype "passive"))
      (node (ref "TVS1") (pin "2") (pinfunction "2_2") (pintype "bidirectional"))
      (node (ref "TVS2") (pin "1") (pinfunction "1_1") (pintype "bidirectional"))
      (node (ref "TVS3") (pin "1") (pinfunction "1_1") (pintype "bidirectional"))
      (node (ref "U1") (pin "107") (pinfunction "VSS_3_107") (pintype "power_in"))
      (node (ref "U1") (pin "121") (pinfunction "VSS_4_121") (pintype "power_in"))
      (node (ref "U1") (pin "134") (pinfunction "VSS_134") (pintype "power_in"))
      (node (ref "U1") (pin "17") (pinfunction "VSS_3_17") (pintype "power_in"))
      (node (ref "U1") (pin "18") (pinfunction "VSS_7_18") (pintype "power_in"))
      (node (ref "U1") (pin "33") (pinfunction "VREFL_33") (pintype "power_in"))
      (node (ref "U1") (pin "34") (pinfunction "VSSA_34") (pintype "power_in"))
      (node (ref "U1") (pin "44") (pinfunction "VSS_5_44") (pintype "power_in"))
      (node (ref "U1") (pin "57") (pinfunction "VSS_6_57") (pintype "power_in"))
      (node (ref "U1") (pin "6") (pinfunction "VSS_2_6") (pintype "power_in"))
      (node (ref "U1") (pin "71") (pinfunction "VSS_71") (pintype "power_in"))
      (node (ref "U1") (pin "93") (pinfunction "VSS_2_93") (pintype "power_in"))
      (node (ref "U2") (pin "6") (pinfunction "GND_6") (pintype "bidirectional"))
      (node (ref "U2") (pin "7") (pinfunction "GND_2_7") (pintype "bidirectional"))
      (node (ref "U3") (pin "12") (pinfunction "PGND_2_12") (pintype "bidirectional"))
      (node (ref "U3") (pin "34") (pinfunction "AGND_34") (pintype "bidirectional"))
      (node (ref "U3") (pin "43") (pinfunction "ADDR1_43") (pintype "bidirectional"))
      (node (ref "U3") (pin "44") (pinfunction "ADDR2_44") (pintype "bidirectional"))
      (node (ref "U3") (pin "48") (pinfunction "GND_48") (pintype "bidirectional"))
      (node (ref "U3") (pin "5") (pinfunction "PGND_5") (pintype "bidirectional"))
      (node (ref "U3") (pin "PAD") (pinfunction "PAD_GND_PAD") (pintype "bidirectional"))
      (node (ref "Y1") (pin "2") (pinfunction "GND_2") (pintype "power_in"))
      (node (ref "Y1") (pin "4") (pinfunction "GND_4") (pintype "power_in"))
    )
    (net (code "110") (name "I2C0_SCL") (class "Default")
      (node (ref "R6") (pin "2") (pinfunction "2_2") (pintype "passive"))
      (node (ref "SCL") (pin "TP") (pinfunction "TP_TP") (pintype "input"))
      (node (ref "U1") (pin "83") (pinfunction "PTB2_83") (pintype "bidirectional"))
      (node (ref "U3") (pin "42") (pinfunction "SCL_42") (pintype "bidirectional"))
    )
    (net (code "111") (name "I2C0_SDA") (class "Default")
      (node (ref "R5") (pin "2") (pinfunction "2_2") (pintype "passive"))
      (node (ref "SDA") (pin "TP") (pinfunction "TP_TP") (pintype "input"))
      (node (ref "U1") (pin "82") (pinfunction "PTB1_82") (pintype "bidirectional"))
      (node (ref "U3") (pin "41") (pinfunction "SDA_41") (pintype "bidirectional"))
    )
    (net (code "112") (name "I2C1_SCL") (class "Default")
      (node (ref "J3") (pin "6") (pinfunction "P$6_6") (pintype "bidirectional"))
      (node (ref "U1") (pin "115") (pinfunction "PTC10_115") (pintype "bidirectional"))
    )
    (net (code "113") (name "I2C1_SDA") (class "Default")
      (node (ref "J3") (pin "5") (pinfunction "P$5_5") (pintype "bidirectional"))
      (node (ref "U1") (pin "116") (pinfunction "PTC11/LLWU_P11_116") (pintype "bidirectional"))
    )
    (net (code "114") (name "IICRST_LED_CTRL") (class "Default")
      (node (ref "R9") (pin "1") (pinfunction "1_1") (pintype "passive"))
      (node (ref "U3") (pin "47") (pinfunction "IICRST_47") (pintype "bidirectional"))
    )
    (net (code "115") (name "INTB_LED_CTRL") (class "Default")
      (node (ref "R7") (pin "2") (pinfunction "2_2") (pintype "passive"))
      (node (ref "U1") (pin "96") (pinfunction "PTB17_96") (pintype "bidirectional"))
      (node (ref "U3") (pin "45") (pinfunction "INTB_45") (pintype "bidirectional"))
    )
    (net (code "116") (name "JTAG_TCLK{slash}SWD_CLK") (class "Default")
      (node (ref "J2") (pin "4") (pinfunction "TCK_4") (pintype "bidirectional"))
      (node (ref "U1") (pin "50") (pinfunction "PTA0_50") (pintype "bidirectional"))
    )
    (net (code "117") (name "JTAG_TDI") (class "Default")
      (node (ref "J2") (pin "8") (pinfunction "TDI_8") (pintype "bidirectional"))
      (node (ref "U1") (pin "51") (pinfunction "PTA1_51") (pintype "bidirectional"))
    )
    (net (code "118") (name "JTAG_TDO{slash}TRACE_SWO") (class "Default")
      (node (ref "J2") (pin "6") (pinfunction "TDO_6") (pintype "bidirectional"))
      (node (ref "U1") (pin "52") (pinfunction "PTA2_52") (pintype "bidirectional"))
    )
    (net (code "119") (name "JTAG_TMS{slash}SWD_DIO") (class "Default")
      (node (ref "J2") (pin "2") (pinfunction "TMS_2") (pintype "bidirectional"))
      (node (ref "U1") (pin "53") (pinfunction "PTA3_53") (pintype "bidirectional"))
    )
    (net (code "120") (name "LED_SINK_1_CTRL") (class "Default")
      (node (ref "SJ85") (pin "1") (pinfunction "1_1") (pintype "passive"))
      (node (ref "U3") (pin "15") (pinfunction "SW12_15") (pintype "bidirectional"))
    )
    (net (code "121") (name "LED_SINK_1_XFUNC") (class "Default")
      (node (ref "KEY_113") (pin "LED-") (pinfunction "LED-_LED-") (pintype "bidirectional"))
      (node (ref "KEY_114") (pin "LED-") (pinfunction "LED-_LED-") (pintype "bidirectional"))
      (node (ref "KEY_133") (pin "LED-") (pinfunction "LED-_LED-") (pintype "bidirectional"))
      (node (ref "KEY_134") (pin "LED-") (pinfunction "LED-_LED-") (pintype "bidirectional"))
      (node (ref "KEY_21") (pin "LED-") (pinfunction "LED-_LED-") (pintype "bidirectional"))
      (node (ref "KEY_22") (pin "LED-") (pinfunction "LED-_LED-") (pintype "bidirectional"))
      (node (ref "KEY_45") (pin "LED-") (pinfunction "LED-_LED-") (pintype "bidirectional"))
      (node (ref "KEY_46") (pin "LED-") (pinfunction "LED-_LED-") (pintype "bidirectional"))
      (node (ref "KEY_68") (pin "LED-") (pinfunction "LED-_LED-") (pintype "bidirectional"))
      (node (ref "KEY_69") (pin "LED-") (pinfunction "LED-_LED-") (pintype "bidirectional"))
      (node (ref "KEY_91") (pin "LED-") (pinfunction "LED-_LED-") (pintype "bidirectional"))
      (node (ref "KEY_92") (pin "LED-") (pinfunction "LED-_LED-") (pintype "bidirectional"))
      (node (ref "SJ47") (pin "1") (pinfunction "1_1") (pintype "passive"))
      (node (ref "SJ85") (pin "2") (pinfunction "2_2") (pintype "passive"))
    )
    (net (code "122") (name "LED_SINK_1_XFUNC_MACRO") (class "Default")
      (node (ref "KEY_1") (pin "LED-") (pinfunction "LED-_LED-") (pintype "bidirectional"))
      (node (ref "KEY_2") (pin "LED-") (pinfunction "LED-_LED-") (pintype "bidirectional"))
      (node (ref "SJ47") (pin "2") (pinfunction "2_2") (pintype "passive"))
    )
    (net (code "123") (name "LED_SINK_2") (class "Default")
      (node (ref "KEY_115") (pin "LED-") (pinfunction "LED-_LED-") (pintype "bidirectional"))
      (node (ref "KEY_116") (pin "LED-") (pinfunction "LED-_LED-") (pintype "bidirectional"))
      (node (ref "KEY_135") (pin "LED-") (pinfunction "LED-_LED-") (pintype "bidirectional"))
      (node (ref "KEY_136") (pin "LED-") (pinfunction "LED-_LED-") (pintype "bidirectional"))
      (node (ref "KEY_23") (pin "LED-") (pinfunction "LED-_LED-") (pintype "bidirectional"))
      (node (ref "KEY_24") (pin "LED-") (pinfunction "LED-_LED-") (pintype "bidirectional"))
      (node (ref "KEY_47") (pin "LED-") (pinfunction "LED-_LED-") (pintype "bidirectional"))
      (node (ref "KEY_48") (pin "LED-") (pinfunction "LED-_LED-") (pintype "bidirectional"))
      (node (ref "KEY_70") (pin "LED-") (pinfunction "LED-_LED-") (pintype "bidirectional"))
      (node (ref "KEY_71") (pin "LED-") (pinfunction "LED-_LED-") (pintype "bidirectional"))
      (node (ref "KEY_93") (pin "LED-") (pinfunction "LED-_LED-") (pintype "bidirectional"))
      (node (ref "KEY_94") (pin "LED-") (pinfunction "LED-_LED-") (pintype "bidirectional"))
      (node (ref "SJ48") (pin "1") (pinfunction "1_1") (pintype "passive"))
      (node (ref "U3") (pin "14") (pinfunction "SW11_14") (pintype "bidirectional"))
    )
    (net (code "124") (name "LED_SINK_2_MACRO") (class "Default")
      (node (ref "KEY_3") (pin "LED-") (pinfunction "LED-_LED-") (pintype "bidirectional"))
      (node (ref "KEY_4") (pin "LED-") (pinfunction "LED-_LED-") (pintype "bidirectional"))
      (node (ref "SJ48") (pin "2") (pinfunction "2_2") (pintype "passive"))
    )
    (net (code "125") (name "LED_SINK_3") (class "Default")
      (node (ref "KEY_117") (pin "LED-") (pinfunction "LED-_LED-") (pintype "bidirectional"))
      (node (ref "KEY_118") (pin "LED-") (pinfunction "LED-_LED-") (pintype "bidirectional"))
      (node (ref "KEY_137") (pin "LED-") (pinfunction "LED-_LED-") (pintype "bidirectional"))
      (node (ref "KEY_25") (pin "LED-") (pinfunction "LED-_LED-") (pintype "bidirectional"))
      (node (ref "KEY_26") (pin "LED-") (pinfunction "LED-_LED-") (pintype "bidirectional"))
      (node (ref "KEY_49") (pin "LED-") (pinfunction "LED-_LED-") (pintype "bidirectional"))
      (node (ref "KEY_50") (pin "LED-") (pinfunction "LED-_LED-") (pintype "bidirectional"))
      (node (ref "KEY_72") (pin "LED-") (pinfunction "LED-_LED-") (pintype "bidirectional"))
      (node (ref "KEY_73") (pin "LED-") (pinfunction "LED-_LED-") (pintype "bidirectional"))
      (node (ref "KEY_95") (pin "LED-") (pinfunction "LED-_LED-") (pintype "bidirectional"))
      (node (ref "KEY_96") (pin "LED-") (pinfunction "LED-_LED-") (pintype "bidirectional"))
      (node (ref "SJ49") (pin "1") (pinfunction "1_1") (pintype "passive"))
      (node (ref "U3") (pin "13") (pinfunction "SW10_13") (pintype "bidirectional"))
    )
    (net (code "126") (name "LED_SINK_3_MACRO") (class "Default")
      (node (ref "KEY_5") (pin "LED-") (pinfunction "LED-_LED-") (pintype "bidirectional"))
      (node (ref "KEY_6") (pin "LED-") (pinfunction "LED-_LED-") (pintype "bidirectional"))
      (node (ref "SJ49") (pin "2") (pinfunction "2_2") (pintype "passive"))
    )
    (net (code "127") (name "LED_SINK_4") (class "Default")
      (node (ref "KEY_119") (pin "LED-") (pinfunction "LED-_LED-") (pintype "bidirectional"))
      (node (ref "KEY_120") (pin "LED-") (pinfunction "LED-_LED-") (pintype "bidirectional"))
      (node (ref "KEY_138") (pin "LED-") (pinfunction "LED-_LED-") (pintype "bidirectional"))
      (node (ref "KEY_27") (pin "LED-") (pinfunction "LED-_LED-") (pintype "bidirectional"))
      (node (ref "KEY_28") (pin "LED-") (pinfunction "LED-_LED-") (pintype "bidirectional"))
      (node (ref "KEY_51") (pin "LED-") (pinfunction "LED-_LED-") (pintype "bidirectional"))
      (node (ref "KEY_52") (pin "LED-") (pinfunction "LED-_LED-") (pintype "bidirectional"))
      (node (ref "KEY_74") (pin "LED-") (pinfunction "LED-_LED-") (pintype "bidirectional"))
      (node (ref "KEY_75") (pin "LED-") (pinfunction "LED-_LED-") (pintype "bidirectional"))
      (node (ref "KEY_97") (pin "LED-") (pinfunction "LED-_LED-") (pintype "bidirectional"))
      (node (ref "KEY_98") (pin "LED-") (pinfunction "LED-_LED-") (pintype "bidirectional"))
      (node (ref "SJ50") (pin "1") (pinfunction "1_1") (pintype "passive"))
      (node (ref "U3") (pin "11") (pinfunction "SW9_11") (pintype "bidirectional"))
    )
    (net (code "128") (name "LED_SINK_4_MACRO") (class "Default")
      (node (ref "KEY_7") (pin "LED-") (pinfunction "LED-_LED-") (pintype "bidirectional"))
      (node (ref "KEY_8") (pin "LED-") (pinfunction "LED-_LED-") (pintype "bidirectional"))
      (node (ref "SJ50") (pin "2") (pinfunction "2_2") (pintype "passive"))
    )
    (net (code "129") (name "LED_SINK_5") (class "Default")
      (node (ref "KEY_100") (pin "LED-") (pinfunction "LED-_LED-") (pintype "bidirectional"))
      (node (ref "KEY_121") (pin "LED-") (pinfunction "LED-_LED-") (pintype "bidirectional"))
      (node (ref "KEY_122") (pin "LED-") (pinfunction "LED-_LED-") (pintype "bidirectional"))
      (node (ref "KEY_29") (pin "LED-") (pinfunction "LED-_LED-") (pintype "bidirectional"))
      (node (ref "KEY_30") (pin "LED-") (pinfunction "LED-_LED-") (pintype "bidirectional"))
      (node (ref "KEY_30_OFFSET") (pin "LED-") (pinfunction "LED-_LED-") (pintype "bidirectional"))
      (node (ref "KEY_53") (pin "LED-") (pinfunction "LED-_LED-") (pintype "bidirectional"))
      (node (ref "KEY_54") (pin "LED-") (pinfunction "LED-_LED-") (pintype "bidirectional"))
      (node (ref "KEY_76") (pin "LED-") (pinfunction "LED-_LED-") (pintype "bidirectional"))
      (node (ref "KEY_77") (pin "LED-") (pinfunction "LED-_LED-") (pintype "bidirectional"))
      (node (ref "KEY_99") (pin "LED-") (pinfunction "LED-_LED-") (pintype "bidirectional"))
      (node (ref "SJ51") (pin "1") (pinfunction "1_1") (pintype "passive"))
      (node (ref "U3") (pin "10") (pinfunction "SW8_10") (pintype "bidirectional"))
    )
    (net (code "130") (name "LED_SINK_5_MACRO") (class "Default")
      (node (ref "KEY_10") (pin "LED-") (pinfunction "LED-_LED-") (pintype "bidirectional"))
      (node (ref "KEY_9") (pin "LED-") (pinfunction "LED-_LED-") (pintype "bidirectional"))
      (node (ref "SJ51") (pin "2") (pinfunction "2_2") (pintype "passive"))
    )
    (net (code "131") (name "LED_SINK_6") (class "Default")
      (node (ref "KEY_101") (pin "LED-") (pinfunction "LED-_LED-") (pintype "bidirectional"))
      (node (ref "KEY_102") (pin "LED-") (pinfunction "LED-_LED-") (pintype "bidirectional"))
      (node (ref "KEY_123") (pin "LED-") (pinfunction "LED-_LED-") (pintype "bidirectional"))
      (node (ref "KEY_124") (pin "LED-") (pinfunction "LED-_LED-") (pintype "bidirectional"))
      (node (ref "KEY_139") (pin "LED-") (pinfunction "LED-_LED-") (pintype "bidirectional"))
      (node (ref "KEY_31") (pin "LED-") (pinfunction "LED-_LED-") (pintype "bidirectional"))
      (node (ref "KEY_31_OFFSET") (pin "LED-") (pinfunction "LED-_LED-") (pintype "bidirectional"))
      (node (ref "KEY_32") (pin "LED-") (pinfunction "LED-_LED-") (pintype "bidirectional"))
      (node (ref "KEY_32_OFFSET") (pin "LED-") (pinfunction "LED-_LED-") (pintype "bidirectional"))
      (node (ref "KEY_55") (pin "LED-") (pinfunction "LED-_LED-") (pintype "bidirectional"))
      (node (ref "KEY_56") (pin "LED-") (pinfunction "LED-_LED-") (pintype "bidirectional"))
      (node (ref "KEY_78") (pin "LED-") (pinfunction "LED-_LED-") (pintype "bidirectional"))
      (node (ref "KEY_79") (pin "LED-") (pinfunction "LED-_LED-") (pintype "bidirectional"))
      (node (ref "SJ52") (pin "1") (pinfunction "1_1") (pintype "passive"))
      (node (ref "U3") (pin "9") (pinfunction "SW7_9") (pintype "bidirectional"))
    )
    (net (code "132") (name "LED_SINK_6_MACRO") (class "Default")
      (node (ref "KEY_11") (pin "LED-") (pinfunction "LED-_LED-") (pintype "bidirectional"))
      (node (ref "KEY_12") (pin "LED-") (pinfunction "LED-_LED-") (pintype "bidirectional"))
      (node (ref "SJ52") (pin "2") (pinfunction "2_2") (pintype "passive"))
    )
    (net (code "133") (name "LED_SINK_7") (class "Default")
      (node (ref "KEY_103") (pin "LED-") (pinfunction "LED-_LED-") (pintype "bidirectional"))
      (node (ref "KEY_104") (pin "LED-") (pinfunction "LED-_LED-") (pintype "bidirectional"))
      (node (ref "KEY_125") (pin "LED-") (pinfunction "LED-_LED-") (pintype "bidirectional"))
      (node (ref "KEY_140") (pin "LED-") (pinfunction "LED-_LED-") (pintype "bidirectional"))
      (node (ref "KEY_141") (pin "LED-") (pinfunction "LED-_LED-") (pintype "bidirectional"))
      (node (ref "KEY_33") (pin "LED-") (pinfunction "LED-_LED-") (pintype "bidirectional"))
      (node (ref "KEY_33_OFFSET") (pin "LED-") (pinfunction "LED-_LED-") (pintype "bidirectional"))
      (node (ref "KEY_34") (pin "LED-") (pinfunction "LED-_LED-") (pintype "bidirectional"))
      (node (ref "KEY_57") (pin "LED-") (pinfunction "LED-_LED-") (pintype "bidirectional"))
      (node (ref "KEY_58") (pin "LED-") (pinfunction "LED-_LED-") (pintype "bidirectional"))
      (node (ref "KEY_80") (pin "LED-") (pinfunction "LED-_LED-") (pintype "bidirectional"))
      (node (ref "KEY_81") (pin "LED-") (pinfunction "LED-_LED-") (pintype "bidirectional"))
      (node (ref "SJ53") (pin "1") (pinfunction "1_1") (pintype "passive"))
      (node (ref "U3") (pin "8") (pinfunction "SW6_8") (pintype "bidirectional"))
    )
    (net (code "134") (name "LED_SINK_7_MACRO") (class "Default")
      (node (ref "KEY_13") (pin "LED-") (pinfunction "LED-_LED-") (pintype "bidirectional"))
      (node (ref "KEY_14") (pin "LED-") (pinfunction "LED-_LED-") (pintype "bidirectional"))
      (node (ref "SJ53") (pin "2") (pinfunction "2_2") (pintype "passive"))
    )
    (net (code "135") (name "LED_SINK_8") (class "Default")
      (node (ref "KEY_35") (pin "LED-") (pinfunction "LED-_LED-") (pintype "bidirectional"))
      (node (ref "KEY_36") (pin "LED-") (pinfunction "LED-_LED-") (pintype "bidirectional"))
      (node (ref "KEY_59") (pin "LED-") (pinfunction "LED-_LED-") (pintype "bidirectional"))
      (node (ref "KEY_82") (pin "LED-") (pinfunction "LED-_LED-") (pintype "bidirectional"))
      (node (ref "SJ54") (pin "1") (pinfunction "1_1") (pintype "passive"))
      (node (ref "U3") (pin "7") (pinfunction "SW5_7") (pintype "bidirectional"))
    )
    (net (code "136") (name "LED_SINK_8_MACRO") (class "Default")
      (node (ref "KEY_15") (pin "LED-") (pinfunction "LED-_LED-") (pintype "bidirectional"))
      (node (ref "KEY_16") (pin "LED-") (pinfunction "LED-_LED-") (pintype "bidirectional"))
      (node (ref "SJ54") (pin "2") (pinfunction "2_2") (pintype "passive"))
    )
    (net (code "137") (name "LED_SINK_9") (class "Default")
      (node (ref "KEY_105") (pin "LED-") (pinfunction "LED-_LED-") (pintype "bidirectional"))
      (node (ref "KEY_106") (pin "LED-") (pinfunction "LED-_LED-") (pintype "bidirectional"))
      (node (ref "KEY_126") (pin "LED-") (pinfunction "LED-_LED-") (pintype "bidirectional"))
      (node (ref "KEY_127") (pin "LED-") (pinfunction "LED-_LED-") (pintype "bidirectional"))
      (node (ref "KEY_142") (pin "LED-") (pinfunction "LED-_LED-") (pintype "bidirectional"))
      (node (ref "KEY_143") (pin "LED-") (pinfunction "LED-_LED-") (pintype "bidirectional"))
      (node (ref "KEY_37") (pin "LED-") (pinfunction "LED-_LED-") (pintype "bidirectional"))
      (node (ref "KEY_38") (pin "LED-") (pinfunction "LED-_LED-") (pintype "bidirectional"))
      (node (ref "KEY_60") (pin "LED-") (pinfunction "LED-_LED-") (pintype "bidirectional"))
      (node (ref "KEY_61") (pin "LED-") (pinfunction "LED-_LED-") (pintype "bidirectional"))
      (node (ref "KEY_83") (pin "LED-") (pinfunction "LED-_LED-") (pintype "bidirectional"))
      (node (ref "KEY_84") (pin "LED-") (pinfunction "LED-_LED-") (pintype "bidirectional"))
      (node (ref "SJ55") (pin "1") (pinfunction "1_1") (pintype "passive"))
      (node (ref "U3") (pin "6") (pinfunction "SW4_6") (pintype "bidirectional"))
    )
    (net (code "138") (name "LED_SINK_9_MACRO") (class "Default")
      (node (ref "KEY_17") (pin "LED-") (pinfunction "LED-_LED-") (pintype "bidirectional"))
      (node (ref "KEY_18") (pin "LED-") (pinfunction "LED-_LED-") (pintype "bidirectional"))
      (node (ref "SJ55") (pin "2") (pinfunction "2_2") (pintype "passive"))
    )
    (net (code "139") (name "LED_SINK_10") (class "Default")
      (node (ref "KEY_107") (pin "LED-") (pinfunction "LED-_LED-") (pintype "bidirectional"))
      (node (ref "KEY_108") (pin "LED-") (pinfunction "LED-_LED-") (pintype "bidirectional"))
      (node (ref "KEY_128") (pin "LED-") (pinfunction "LED-_LED-") (pintype "bidirectional"))
      (node (ref "KEY_129") (pin "LED-") (pinfunction "LED-_LED-") (pintype "bidirectional"))
      (node (ref "KEY_144") (pin "LED-") (pinfunction "LED-_LED-") (pintype "bidirectional"))
      (node (ref "KEY_145") (pin "LED-") (pinfunction "LED-_LED-") (pintype "bidirectional"))
      (node (ref "KEY_39") (pin "LED-") (pinfunction "LED-_LED-") (pintype "bidirectional"))
      (node (ref "KEY_40") (pin "LED-") (pinfunction "LED-_LED-") (pintype "bidirectional"))
      (node (ref "KEY_62") (pin "LED-") (pinfunction "LED-_LED-") (pintype "bidirectional"))
      (node (ref "KEY_63") (pin "LED-") (pinfunction "LED-_LED-") (pintype "bidirectional"))
      (node (ref "KEY_85") (pin "LED-") (pinfunction "LED-_LED-") (pintype "bidirectional"))
      (node (ref "KEY_86") (pin "LED-") (pinfunction "LED-_LED-") (pintype "bidirectional"))
      (node (ref "SJ56") (pin "1") (pinfunction "1_1") (pintype "passive"))
      (node (ref "U3") (pin "4") (pinfunction "SW3_4") (pintype "bidirectional"))
    )
    (net (code "140") (name "LED_SINK_10_MACRO") (class "Default")
      (node (ref "KEY_19") (pin "LED-") (pinfunction "LED-_LED-") (pintype "bidirectional"))
      (node (ref "KEY_20") (pin "LED-") (pinfunction "LED-_LED-") (pintype "bidirectional"))
      (node (ref "SJ56") (pin "2") (pinfunction "2_2") (pintype "passive"))
    )
    (net (code "141") (name "LED_SINK_11") (class "Default")
      (node (ref "KEY_109") (pin "LED-") (pinfunction "LED-_LED-") (pintype "bidirectional"))
      (node (ref "KEY_110") (pin "LED-") (pinfunction "LED-_LED-") (pintype "bidirectional"))
      (node (ref "KEY_130") (pin "LED-") (pinfunction "LED-_LED-") (pintype "bidirectional"))
      (node (ref "KEY_131") (pin "LED-") (pinfunction "LED-_LED-") (pintype "bidirectional"))
      (node (ref "KEY_146") (pin "LED-") (pinfunction "LED-_LED-") (pintype "bidirectional"))
      (node (ref "KEY_147") (pin "LED-") (pinfunction "LED-_LED-") (pintype "bidirectional"))
      (node (ref "KEY_41") (pin "LED-") (pinfunction "LED-_LED-") (pintype "bidirectional"))
      (node (ref "KEY_42") (pin "LED-") (pinfunction "LED-_LED-") (pintype "bidirectional"))
      (node (ref "KEY_64") (pin "LED-") (pinfunction "LED-_LED-") (pintype "bidirectional"))
      (node (ref "KEY_65") (pin "LED-") (pinfunction "LED-_LED-") (pintype "bidirectional"))
      (node (ref "KEY_87") (pin "LED-") (pinfunction "LED-_LED-") (pintype "bidirectional"))
      (node (ref "KEY_88") (pin "LED-") (pinfunction "LED-_LED-") (pintype "bidirectional"))
      (node (ref "SJ57") (pin "1") (pinfunction "1_1") (pintype "passive"))
      (node (ref "SJ86") (pin "1") (pinfunction "1_1") (pintype "passive"))
    )
    (net (code "142") (name "LED_SINK_11_CTRL") (class "Default")
      (node (ref "SJ86") (pin "2") (pinfunction "2_2") (pintype "passive"))
      (node (ref "U3") (pin "3") (pinfunction "SW2_3") (pintype "bidirectional"))
    )
    (net (code "143") (name "LED_SINK_11_MACRO") (class "Default")
      (node (ref "KEY_150") (pin "LED-") (pinfunction "LED-_LED-") (pintype "bidirectional"))
      (node (ref "KEY_151") (pin "LED-") (pinfunction "LED-_LED-") (pintype "bidirectional"))
      (node (ref "SJ57") (pin "2") (pinfunction "2_2") (pintype "passive"))
    )
    (net (code "144") (name "LED_SINK_12") (class "Default")
      (node (ref "KEY_111") (pin "LED-") (pinfunction "LED-_LED-") (pintype "bidirectional"))
      (node (ref "KEY_112") (pin "LED-") (pinfunction "LED-_LED-") (pintype "bidirectional"))
      (node (ref "KEY_132") (pin "LED-") (pinfunction "LED-_LED-") (pintype "bidirectional"))
      (node (ref "KEY_148") (pin "LED-") (pinfunction "LED-_LED-") (pintype "bidirectional"))
      (node (ref "KEY_149") (pin "LED-") (pinfunction "LED-_LED-") (pintype "bidirectional"))
      (node (ref "KEY_43") (pin "LED-") (pinfunction "LED-_LED-") (pintype "bidirectional"))
      (node (ref "KEY_44") (pin "LED-") (pinfunction "LED-_LED-") (pintype "bidirectional"))
      (node (ref "KEY_66") (pin "LED-") (pinfunction "LED-_LED-") (pintype "bidirectional"))
      (node (ref "KEY_67") (pin "LED-") (pinfunction "LED-_LED-") (pintype "bidirectional"))
      (node (ref "KEY_89") (pin "LED-") (pinfunction "LED-_LED-") (pintype "bidirectional"))
      (node (ref "KEY_90") (pin "LED-") (pinfunction "LED-_LED-") (pintype "bidirectional"))
      (node (ref "SJ58") (pin "1") (pinfunction "1_1") (pintype "passive"))
      (node (ref "SJ87") (pin "1") (pinfunction "1_1") (pintype "passive"))
    )
    (net (code "145") (name "LED_SINK_12_CTRL") (class "Default")
      (node (ref "SJ87") (pin "2") (pinfunction "2_2") (pintype "passive"))
      (node (ref "U3") (pin "2") (pinfunction "SW1_2") (pintype "bidirectional"))
    )
    (net (code "146") (name "LED_SINK_12_MACRO") (class "Default")
      (node (ref "KEY_152") (pin "LED-") (pinfunction "LED-_LED-") (pintype "bidirectional"))
      (node (ref "KEY_153") (pin "LED-") (pinfunction "LED-_LED-") (pintype "bidirectional"))
      (node (ref "SJ58") (pin "2") (pinfunction "2_2") (pintype "passive"))
    )
    (net (code "147") (name "LED_SORUCE_9_NUM") (class "Default")
      (node (ref "KEY_109") (pin "LED+") (pinfunction "LED+_LED+") (pintype "bidirectional"))
      (node (ref "KEY_111") (pin "LED+") (pinfunction "LED+_LED+") (pintype "bidirectional"))
      (node (ref "SJ73") (pin "1") (pinfunction "1_1") (pintype "passive"))
    )
    (net (code "148") (name "LED_SORUCE_10_XFUNC") (class "Default")
      (node (ref "KEY_92") (pin "LED+") (pinfunction "LED+_LED+") (pintype "bidirectional"))
      (node (ref "SJ72") (pin "2") (pinfunction "2_2") (pintype "passive"))
    )
    (net (code "149") (name "LED_SOURCE_1_CTRL") (class "Default")
      (node (ref "SJ83") (pin "2") (pinfunction "2_2") (pintype "passive"))
      (node (ref "U3") (pin "16") (pinfunction "CS1_16") (pintype "bidirectional"))
    )
    (net (code "150") (name "LED_SOURCE_1_NUM") (class "Default")
      (node (ref "KEY_150") (pin "LED+") (pinfunction "LED+_LED+") (pintype "bidirectional"))
      (node (ref "KEY_152") (pin "LED+") (pinfunction "LED+_LED+") (pintype "bidirectional"))
      (node (ref "SJ44") (pin "1") (pinfunction "1_1") (pintype "passive"))
    )
    (net (code "151") (name "LED_SOURCE_1_QWERTY") (class "Default")
      (node (ref "KEY_11") (pin "LED+") (pinfunction "LED+_LED+") (pintype "bidirectional"))
      (node (ref "KEY_13") (pin "LED+") (pinfunction "LED+_LED+") (pintype "bidirectional"))
      (node (ref "KEY_15") (pin "LED+") (pinfunction "LED+_LED+") (pintype "bidirectional"))
      (node (ref "KEY_17") (pin "LED+") (pinfunction "LED+_LED+") (pintype "bidirectional"))
      (node (ref "KEY_19") (pin "LED+") (pinfunction "LED+_LED+") (pintype "bidirectional"))
      (node (ref "KEY_3") (pin "LED+") (pinfunction "LED+_LED+") (pintype "bidirectional"))
      (node (ref "KEY_5") (pin "LED+") (pinfunction "LED+_LED+") (pintype "bidirectional"))
      (node (ref "KEY_7") (pin "LED+") (pinfunction "LED+_LED+") (pintype "bidirectional"))
      (node (ref "KEY_9") (pin "LED+") (pinfunction "LED+_LED+") (pintype "bidirectional"))
      (node (ref "SJ44") (pin "2") (pinfunction "2_2") (pintype "passive"))
      (node (ref "SJ45") (pin "1") (pinfunction "1_1") (pintype "passive"))
      (node (ref "SJ83") (pin "1") (pinfunction "1_1") (pintype "passive"))
    )
    (net (code "152") (name "LED_SOURCE_1_XFUNC") (class "Default")
      (node (ref "KEY_1") (pin "LED+") (pinfunction "LED+_LED+") (pintype "bidirectional"))
      (node (ref "SJ45") (pin "2") (pinfunction "2_2") (pintype "passive"))
    )
    (net (code "153") (name "LED_SOURCE_2_CTRL") (class "Default")
      (node (ref "SJ84") (pin "2") (pinfunction "2_2") (pintype "passive"))
      (node (ref "U3") (pin "17") (pinfunction "CS2_17") (pintype "bidirectional"))
    )
    (net (code "154") (name "LED_SOURCE_2_NUM") (class "Default")
      (node (ref "KEY_151") (pin "LED+") (pinfunction "LED+_LED+") (pintype "bidirectional"))
      (node (ref "KEY_153") (pin "LED+") (pinfunction "LED+_LED+") (pintype "bidirectional"))
      (node (ref "SJ43") (pin "1") (pinfunction "1_1") (pintype "passive"))
    )
    (net (code "155") (name "LED_SOURCE_2_QWERY") (class "Default")
      (node (ref "KEY_10") (pin "LED+") (pinfunction "LED+_LED+") (pintype "bidirectional"))
      (node (ref "KEY_12") (pin "LED+") (pinfunction "LED+_LED+") (pintype "bidirectional"))
      (node (ref "KEY_14") (pin "LED+") (pinfunction "LED+_LED+") (pintype "bidirectional"))
      (node (ref "KEY_16") (pin "LED+") (pinfunction "LED+_LED+") (pintype "bidirectional"))
      (node (ref "KEY_18") (pin "LED+") (pinfunction "LED+_LED+") (pintype "bidirectional"))
      (node (ref "KEY_20") (pin "LED+") (pinfunction "LED+_LED+") (pintype "bidirectional"))
      (node (ref "KEY_4") (pin "LED+") (pinfunction "LED+_LED+") (pintype "bidirectional"))
      (node (ref "KEY_6") (pin "LED+") (pinfunction "LED+_LED+") (pintype "bidirectional"))
      (node (ref "KEY_8") (pin "LED+") (pinfunction "LED+_LED+") (pintype "bidirectional"))
      (node (ref "SJ43") (pin "2") (pinfunction "2_2") (pintype "passive"))
      (node (ref "SJ46") (pin "1") (pinfunction "1_1") (pintype "passive"))
      (node (ref "SJ84") (pin "1") (pinfunction "1_1") (pintype "passive"))
    )
    (net (code "156") (name "LED_SOURCE_2_XFUNC") (class "Default")
      (node (ref "KEY_2") (pin "LED+") (pinfunction "LED+_LED+") (pintype "bidirectional"))
      (node (ref "SJ46") (pin "2") (pinfunction "2_2") (pintype "passive"))
    )
    (net (code "157") (name "LED_SOURCE_3_NUM") (class "Default")
      (node (ref "KEY_41") (pin "LED+") (pinfunction "LED+_LED+") (pintype "bidirectional"))
      (node (ref "KEY_43") (pin "LED+") (pinfunction "LED+_LED+") (pintype "bidirectional"))
      (node (ref "SJ61") (pin "1") (pinfunction "1_1") (pintype "passive"))
    )
    (net (code "158") (name "LED_SOURCE_3_QWERTY") (class "Default")
      (node (ref "KEY_23") (pin "LED+") (pinfunction "LED+_LED+") (pintype "bidirectional"))
      (node (ref "KEY_25") (pin "LED+") (pinfunction "LED+_LED+") (pintype "bidirectional"))
      (node (ref "KEY_27") (pin "LED+") (pinfunction "LED+_LED+") (pintype "bidirectional"))
      (node (ref "KEY_29") (pin "LED+") (pinfunction "LED+_LED+") (pintype "bidirectional"))
      (node (ref "KEY_31") (pin "LED+") (pinfunction "LED+_LED+") (pintype "bidirectional"))
      (node (ref "KEY_31_OFFSET") (pin "LED+") (pinfunction "LED+_LED+") (pintype "bidirectional"))
      (node (ref "KEY_33") (pin "LED+") (pinfunction "LED+_LED+") (pintype "bidirectional"))
      (node (ref "KEY_33_OFFSET") (pin "LED+") (pinfunction "LED+_LED+") (pintype "bidirectional"))
      (node (ref "KEY_35") (pin "LED+") (pinfunction "LED+_LED+") (pintype "bidirectional"))
      (node (ref "KEY_37") (pin "LED+") (pinfunction "LED+_LED+") (pintype "bidirectional"))
      (node (ref "KEY_39") (pin "LED+") (pinfunction "LED+_LED+") (pintype "bidirectional"))
      (node (ref "SJ59") (pin "2") (pinfunction "2_2") (pintype "passive"))
      (node (ref "SJ61") (pin "2") (pinfunction "2_2") (pintype "passive"))
      (node (ref "U3") (pin "18") (pinfunction "CS3_18") (pintype "bidirectional"))
    )
    (net (code "159") (name "LED_SOURCE_3_XFUNC") (class "Default")
      (node (ref "KEY_21") (pin "LED+") (pinfunction "LED+_LED+") (pintype "bidirectional"))
      (node (ref "SJ59") (pin "1") (pinfunction "1_1") (pintype "passive"))
    )
    (net (code "160") (name "LED_SOURCE_4_NUM") (class "Default")
      (node (ref "KEY_42") (pin "LED+") (pinfunction "LED+_LED+") (pintype "bidirectional"))
      (node (ref "KEY_44") (pin "LED+") (pinfunction "LED+_LED+") (pintype "bidirectional"))
      (node (ref "SJ62") (pin "1") (pinfunction "1_1") (pintype "passive"))
    )
    (net (code "161") (name "LED_SOURCE_4_QWERTY") (class "Default")
      (node (ref "KEY_24") (pin "LED+") (pinfunction "LED+_LED+") (pintype "bidirectional"))
      (node (ref "KEY_26") (pin "LED+") (pinfunction "LED+_LED+") (pintype "bidirectional"))
      (node (ref "KEY_28") (pin "LED+") (pinfunction "LED+_LED+") (pintype "bidirectional"))
      (node (ref "KEY_30") (pin "LED+") (pinfunction "LED+_LED+") (pintype "bidirectional"))
      (node (ref "KEY_30_OFFSET") (pin "LED+") (pinfunction "LED+_LED+") (pintype "bidirectional"))
      (node (ref "KEY_32") (pin "LED+") (pinfunction "LED+_LED+") (pintype "bidirectional"))
      (node (ref "KEY_32_OFFSET") (pin "LED+") (pinfunction "LED+_LED+") (pintype "bidirectional"))
      (node (ref "KEY_34") (pin "LED+") (pinfunction "LED+_LED+") (pintype "bidirectional"))
      (node (ref "KEY_36") (pin "LED+") (pinfunction "LED+_LED+") (pintype "bidirectional"))
      (node (ref "KEY_38") (pin "LED+") (pinfunction "LED+_LED+") (pintype "bidirectional"))
      (node (ref "KEY_40") (pin "LED+") (pinfunction "LED+_LED+") (pintype "bidirectional"))
      (node (ref "SJ60") (pin "2") (pinfunction "2_2") (pintype "passive"))
      (node (ref "SJ62") (pin "2") (pinfunction "2_2") (pintype "passive"))
      (node (ref "U3") (pin "19") (pinfunction "CS4_19") (pintype "bidirectional"))
    )
    (net (code "162") (name "LED_SOURCE_4_XFUNC") (class "Default")
      (node (ref "KEY_22") (pin "LED+") (pinfunction "LED+_LED+") (pintype "bidirectional"))
      (node (ref "SJ60") (pin "1") (pinfunction "1_1") (pintype "passive"))
    )
    (net (code "163") (name "LED_SOURCE_5_NUM") (class "Default")
      (node (ref "KEY_64") (pin "LED+") (pinfunction "LED+_LED+") (pintype "bidirectional"))
      (node (ref "KEY_66") (pin "LED+") (pinfunction "LED+_LED+") (pintype "bidirectional"))
      (node (ref "SJ65") (pin "1") (pinfunction "1_1") (pintype "passive"))
    )
    (net (code "164") (name "LED_SOURCE_5_QWERTY") (class "Default")
      (node (ref "KEY_47") (pin "LED+") (pinfunction "LED+_LED+") (pintype "bidirectional"))
      (node (ref "KEY_49") (pin "LED+") (pinfunction "LED+_LED+") (pintype "bidirectional"))
      (node (ref "KEY_51") (pin "LED+") (pinfunction "LED+_LED+") (pintype "bidirectional"))
      (node (ref "KEY_53") (pin "LED+") (pinfunction "LED+_LED+") (pintype "bidirectional"))
      (node (ref "KEY_55") (pin "LED+") (pinfunction "LED+_LED+") (pintype "bidirectional"))
      (node (ref "KEY_57") (pin "LED+") (pinfunction "LED+_LED+") (pintype "bidirectional"))
      (node (ref "KEY_59") (pin "LED+") (pinfunction "LED+_LED+") (pintype "bidirectional"))
      (node (ref "KEY_60") (pin "LED+") (pinfunction "LED+_LED+") (pintype "bidirectional"))
      (node (ref "KEY_62") (pin "LED+") (pinfunction "LED+_LED+") (pintype "bidirectional"))
      (node (ref "SJ63") (pin "2") (pinfunction "2_2") (pintype "passive"))
      (node (ref "SJ65") (pin "2") (pinfunction "2_2") (pintype "passive"))
      (node (ref "U3") (pin "21") (pinfunction "CS5_21") (pintype "bidirectional"))
    )
    (net (code "165") (name "LED_SOURCE_5_XFUNC") (class "Default")
      (node (ref "KEY_45") (pin "LED+") (pinfunction "LED+_LED+") (pintype "bidirectional"))
      (node (ref "SJ63") (pin "1") (pinfunction "1_1") (pintype "passive"))
    )
    (net (code "166") (name "LED_SOURCE_6_NUM") (class "Default")
      (node (ref "KEY_65") (pin "LED+") (pinfunction "LED+_LED+") (pintype "bidirectional"))
      (node (ref "KEY_67") (pin "LED+") (pinfunction "LED+_LED+") (pintype "bidirectional"))
      (node (ref "SJ66") (pin "1") (pinfunction "1_1") (pintype "passive"))
    )
    (net (code "167") (name "LED_SOURCE_6_QWERTY") (class "Default")
      (node (ref "KEY_48") (pin "LED+") (pinfunction "LED+_LED+") (pintype "bidirectional"))
      (node (ref "KEY_50") (pin "LED+") (pinfunction "LED+_LED+") (pintype "bidirectional"))
      (node (ref "KEY_52") (pin "LED+") (pinfunction "LED+_LED+") (pintype "bidirectional"))
      (node (ref "KEY_54") (pin "LED+") (pinfunction "LED+_LED+") (pintype "bidirectional"))
      (node (ref "KEY_56") (pin "LED+") (pinfunction "LED+_LED+") (pintype "bidirectional"))
      (node (ref "KEY_58") (pin "LED+") (pinfunction "LED+_LED+") (pintype "bidirectional"))
      (node (ref "KEY_61") (pin "LED+") (pinfunction "LED+_LED+") (pintype "bidirectional"))
      (node (ref "KEY_63") (pin "LED+") (pinfunction "LED+_LED+") (pintype "bidirectional"))
      (node (ref "SJ64") (pin "2") (pinfunction "2_2") (pintype "passive"))
      (node (ref "SJ66") (pin "2") (pinfunction "2_2") (pintype "passive"))
      (node (ref "U3") (pin "22") (pinfunction "CS6_22") (pintype "bidirectional"))
    )
    (net (code "168") (name "LED_SOURCE_6_XFUNC") (class "Default")
      (node (ref "KEY_46") (pin "LED+") (pinfunction "LED+_LED+") (pintype "bidirectional"))
      (node (ref "SJ64") (pin "1") (pinfunction "1_1") (pintype "passive"))
    )
    (net (code "169") (name "LED_SOURCE_7_NUM") (class "Default")
      (node (ref "KEY_87") (pin "LED+") (pinfunction "LED+_LED+") (pintype "bidirectional"))
      (node (ref "KEY_89") (pin "LED+") (pinfunction "LED+_LED+") (pintype "bidirectional"))
      (node (ref "SJ69") (pin "1") (pinfunction "1_1") (pintype "passive"))
    )
    (net (code "170") (name "LED_SOURCE_7_QWERTY") (class "Default")
      (node (ref "KEY_70") (pin "LED+") (pinfunction "LED+_LED+") (pintype "bidirectional"))
      (node (ref "KEY_72") (pin "LED+") (pinfunction "LED+_LED+") (pintype "bidirectional"))
      (node (ref "KEY_74") (pin "LED+") (pinfunction "LED+_LED+") (pintype "bidirectional"))
      (node (ref "KEY_76") (pin "LED+") (pinfunction "LED+_LED+") (pintype "bidirectional"))
      (node (ref "KEY_78") (pin "LED+") (pinfunction "LED+_LED+") (pintype "bidirectional"))
      (node (ref "KEY_80") (pin "LED+") (pinfunction "LED+_LED+") (pintype "bidirectional"))
      (node (ref "KEY_82") (pin "LED+") (pinfunction "LED+_LED+") (pintype "bidirectional"))
      (node (ref "KEY_83") (pin "LED+") (pinfunction "LED+_LED+") (pintype "bidirectional"))
      (node (ref "KEY_85") (pin "LED+") (pinfunction "LED+_LED+") (pintype "bidirectional"))
      (node (ref "SJ67") (pin "1") (pinfunction "1_1") (pintype "passive"))
      (node (ref "SJ69") (pin "2") (pinfunction "2_2") (pintype "passive"))
      (node (ref "U3") (pin "23") (pinfunction "CS7_23") (pintype "bidirectional"))
    )
    (net (code "171") (name "LED_SOURCE_7_XFUNC") (class "Default")
      (node (ref "KEY_68") (pin "LED+") (pinfunction "LED+_LED+") (pintype "bidirectional"))
      (node (ref "SJ67") (pin "2") (pinfunction "2_2") (pintype "passive"))
    )
    (net (code "172") (name "LED_SOURCE_8_NUM") (class "Default")
      (node (ref "KEY_88") (pin "LED+") (pinfunction "LED+_LED+") (pintype "bidirectional"))
      (node (ref "KEY_90") (pin "LED+") (pinfunction "LED+_LED+") (pintype "bidirectional"))
      (node (ref "SJ70") (pin "1") (pinfunction "1_1") (pintype "passive"))
    )
    (net (code "173") (name "LED_SOURCE_8_QWERTY") (class "Default")
      (node (ref "KEY_71") (pin "LED+") (pinfunction "LED+_LED+") (pintype "bidirectional"))
      (node (ref "KEY_73") (pin "LED+") (pinfunction "LED+_LED+") (pintype "bidirectional"))
      (node (ref "KEY_75") (pin "LED+") (pinfunction "LED+_LED+") (pintype "bidirectional"))
      (node (ref "KEY_77") (pin "LED+") (pinfunction "LED+_LED+") (pintype "bidirectional"))
      (node (ref "KEY_79") (pin "LED+") (pinfunction "LED+_LED+") (pintype "bidirectional"))
      (node (ref "KEY_81") (pin "LED+") (pinfunction "LED+_LED+") (pintype "bidirectional"))
      (node (ref "KEY_84") (pin "LED+") (pinfunction "LED+_LED+") (pintype "bidirectional"))
      (node (ref "KEY_86") (pin "LED+") (pinfunction "LED+_LED+") (pintype "bidirectional"))
      (node (ref "SJ68") (pin "1") (pinfunction "1_1") (pintype "passive"))
      (node (ref "SJ70") (pin "2") (pinfunction "2_2") (pintype "passive"))
      (node (ref "U3") (pin "24") (pinfunction "CS8_24") (pintype "bidirectional"))
    )
    (net (code "174") (name "LED_SOURCE_8_XFUNC") (class "Default")
      (node (ref "KEY_69") (pin "LED+") (pinfunction "LED+_LED+") (pintype "bidirectional"))
      (node (ref "SJ68") (pin "2") (pinfunction "2_2") (pintype "passive"))
    )
    (net (code "175") (name "LED_SOURCE_9_QWERTY") (class "Default")
      (node (ref "KEY_101") (pin "LED+") (pinfunction "LED+_LED+") (pintype "bidirectional"))
      (node (ref "KEY_103") (pin "LED+") (pinfunction "LED+_LED+") (pintype "bidirectional"))
      (node (ref "KEY_105") (pin "LED+") (pinfunction "LED+_LED+") (pintype "bidirectional"))
      (node (ref "KEY_107") (pin "LED+") (pinfunction "LED+_LED+") (pintype "bidirectional"))
      (node (ref "KEY_93") (pin "LED+") (pinfunction "LED+_LED+") (pintype "bidirectional"))
      (node (ref "KEY_95") (pin "LED+") (pinfunction "LED+_LED+") (pintype "bidirectional"))
      (node (ref "KEY_97") (pin "LED+") (pinfunction "LED+_LED+") (pintype "bidirectional"))
      (node (ref "KEY_99") (pin "LED+") (pinfunction "LED+_LED+") (pintype "bidirectional"))
      (node (ref "SJ71") (pin "1") (pinfunction "1_1") (pintype "passive"))
      (node (ref "SJ73") (pin "2") (pinfunction "2_2") (pintype "passive"))
      (node (ref "U3") (pin "25") (pinfunction "CS9_25") (pintype "bidirectional"))
    )
    (net (code "176") (name "LED_SOURCE_9_XFUNC") (class "Default")
      (node (ref "KEY_91") (pin "LED+") (pinfunction "LED+_LED+") (pintype "bidirectional"))
      (node (ref "SJ71") (pin "2") (pinfunction "2_2") (pintype "passive"))
    )
    (net (code "177") (name "LED_SOURCE_10_NUM") (class "Default")
      (node (ref "KEY_110") (pin "LED+") (pinfunction "LED+_LED+") (pintype "bidirectional"))
      (node (ref "KEY_112") (pin "LED+") (pinfunction "LED+_LED+") (pintype "bidirectional"))
      (node (ref "SJ74") (pin "1") (pinfunction "1_1") (pintype "passive"))
    )
    (net (code "178") (name "LED_SOURCE_10_QWERTY") (class "Default")
      (node (ref "KEY_100") (pin "LED+") (pinfunction "LED+_LED+") (pintype "bidirectional"))
      (node (ref "KEY_102") (pin "LED+") (pinfunction "LED+_LED+") (pintype "bidirectional"))
      (node (ref "KEY_104") (pin "LED+") (pinfunction "LED+_LED+") (pintype "bidirectional"))
      (node (ref "KEY_106") (pin "LED+") (pinfunction "LED+_LED+") (pintype "bidirectional"))
      (node (ref "KEY_108") (pin "LED+") (pinfunction "LED+_LED+") (pintype "bidirectional"))
      (node (ref "KEY_94") (pin "LED+") (pinfunction "LED+_LED+") (pintype "bidirectional"))
      (node (ref "KEY_96") (pin "LED+") (pinfunction "LED+_LED+") (pintype "bidirectional"))
      (node (ref "KEY_98") (pin "LED+") (pinfunction "LED+_LED+") (pintype "bidirectional"))
      (node (ref "SJ72") (pin "1") (pinfunction "1_1") (pintype "passive"))
      (node (ref "SJ74") (pin "2") (pinfunction "2_2") (pintype "passive"))
      (node (ref "U3") (pin "26") (pinfunction "CS10_26") (pintype "bidirectional"))
    )
    (net (code "179") (name "LED_SOURCE_11_NUM") (class "Default")
      (node (ref "KEY_130") (pin "LED+") (pinfunction "LED+_LED+") (pintype "bidirectional"))
      (node (ref "KEY_132") (pin "LED+") (pinfunction "LED+_LED+") (pintype "bidirectional"))
      (node (ref "SJ77") (pin "1") (pinfunction "1_1") (pintype "passive"))
    )
    (net (code "180") (name "LED_SOURCE_11_QWERTY") (class "Default")
      (node (ref "KEY_115") (pin "LED+") (pinfunction "LED+_LED+") (pintype "bidirectional"))
      (node (ref "KEY_117") (pin "LED+") (pinfunction "LED+_LED+") (pintype "bidirectional"))
      (node (ref "KEY_119") (pin "LED+") (pinfunction "LED+_LED+") (pintype "bidirectional"))
      (node (ref "KEY_121") (pin "LED+") (pinfunction "LED+_LED+") (pintype "bidirectional"))
      (node (ref "KEY_123") (pin "LED+") (pinfunction "LED+_LED+") (pintype "bidirectional"))
      (node (ref "KEY_125") (pin "LED+") (pinfunction "LED+_LED+") (pintype "bidirectional"))
      (node (ref "KEY_126") (pin "LED+") (pinfunction "LED+_LED+") (pintype "bidirectional"))
      (node (ref "KEY_128") (pin "LED+") (pinfunction "LED+_LED+") (pintype "bidirectional"))
      (node (ref "SJ75") (pin "1") (pinfunction "1_1") (pintype "passive"))
      (node (ref "SJ77") (pin "2") (pinfunction "2_2") (pintype "passive"))
      (node (ref "U3") (pin "27") (pinfunction "CS11_27") (pintype "bidirectional"))
    )
    (net (code "181") (name "LED_SOURCE_11_XFUNC") (class "Default")
      (node (ref "KEY_113") (pin "LED+") (pinfunction "LED+_LED+") (pintype "bidirectional"))
      (node (ref "SJ75") (pin "2") (pinfunction "2_2") (pintype "passive"))
    )
    (net (code "182") (name "LED_SOURCE_12_NUM") (class "Default")
      (node (ref "KEY_131") (pin "LED+") (pinfunction "LED+_LED+") (pintype "bidirectional"))
      (node (ref "SJ78") (pin "1") (pinfunction "1_1") (pintype "passive"))
    )
    (net (code "183") (name "LED_SOURCE_12_QWERTY") (class "Default")
      (node (ref "KEY_116") (pin "LED+") (pinfunction "LED+_LED+") (pintype "bidirectional"))
      (node (ref "KEY_118") (pin "LED+") (pinfunction "LED+_LED+") (pintype "bidirectional"))
      (node (ref "KEY_120") (pin "LED+") (pinfunction "LED+_LED+") (pintype "bidirectional"))
      (node (ref "KEY_122") (pin "LED+") (pinfunction "LED+_LED+") (pintype "bidirectional"))
      (node (ref "KEY_124") (pin "LED+") (pinfunction "LED+_LED+") (pintype "bidirectional"))
      (node (ref "KEY_127") (pin "LED+") (pinfunction "LED+_LED+") (pintype "bidirectional"))
      (node (ref "KEY_129") (pin "LED+") (pinfunction "LED+_LED+") (pintype "bidirectional"))
      (node (ref "SJ76") (pin "1") (pinfunction "1_1") (pintype "passive"))
      (node (ref "SJ78") (pin "2") (pinfunction "2_2") (pintype "passive"))
      (node (ref "U3") (pin "28") (pinfunction "CS12_28") (pintype "bidirectional"))
    )
    (net (code "184") (name "LED_SOURCE_12_XFUNC") (class "Default")
      (node (ref "KEY_114") (pin "LED+") (pinfunction "LED+_LED+") (pintype "bidirectional"))
      (node (ref "SJ76") (pin "2") (pinfunction "2_2") (pintype "passive"))
    )
    (net (code "185") (name "LED_SOURCE_13_NUM") (class "Default")
      (node (ref "KEY_146") (pin "LED+") (pinfunction "LED+_LED+") (pintype "bidirectional"))
      (node (ref "KEY_148") (pin "LED+") (pinfunction "LED+_LED+") (pintype "bidirectional"))
      (node (ref "SJ81") (pin "1") (pinfunction "1_1") (pintype "passive"))
    )
    (net (code "186") (name "LED_SOURCE_13_QWERTY") (class "Default")
      (node (ref "KEY_135") (pin "LED+") (pinfunction "LED+_LED+") (pintype "bidirectional"))
      (node (ref "KEY_137") (pin "LED+") (pinfunction "LED+_LED+") (pintype "bidirectional"))
      (node (ref "KEY_140") (pin "LED+") (pinfunction "LED+_LED+") (pintype "bidirectional"))
      (node (ref "KEY_142") (pin "LED+") (pinfunction "LED+_LED+") (pintype "bidirectional"))
      (node (ref "KEY_144") (pin "LED+") (pinfunction "LED+_LED+") (pintype "bidirectional"))
      (node (ref "SJ79") (pin "1") (pinfunction "1_1") (pintype "passive"))
      (node (ref "SJ81") (pin "2") (pinfunction "2_2") (pintype "passive"))
      (node (ref "U3") (pin "30") (pinfunction "CS13_30") (pintype "bidirectional"))
    )
    (net (code "187") (name "LED_SOURCE_13_XFUNC") (class "Default")
      (node (ref "KEY_133") (pin "LED+") (pinfunction "LED+_LED+") (pintype "bidirectional"))
      (node (ref "SJ79") (pin "2") (pinfunction "2_2") (pintype "passive"))
    )
    (net (code "188") (name "LED_SOURCE_14_NUM") (class "Default")
      (node (ref "KEY_147") (pin "LED+") (pinfunction "LED+_LED+") (pintype "bidirectional"))
      (node (ref "KEY_149") (pin "LED+") (pinfunction "LED+_LED+") (pintype "bidirectional"))
      (node (ref "SJ82") (pin "1") (pinfunction "1_1") (pintype "passive"))
    )
    (net (code "189") (name "LED_SOURCE_14_QWERTY") (class "Default")
      (node (ref "KEY_136") (pin "LED+") (pinfunction "LED+_LED+") (pintype "bidirectional"))
      (node (ref "KEY_138") (pin "LED+") (pinfunction "LED+_LED+") (pintype "bidirectional"))
      (node (ref "KEY_139") (pin "LED+") (pinfunction "LED+_LED+") (pintype "bidirectional"))
      (node (ref "KEY_141") (pin "LED+") (pinfunction "LED+_LED+") (pintype "bidirectional"))
      (node (ref "KEY_143") (pin "LED+") (pinfunction "LED+_LED+") (pintype "bidirectional"))
      (node (ref "KEY_145") (pin "LED+") (pinfunction "LED+_LED+") (pintype "bidirectional"))
      (node (ref "SJ80") (pin "1") (pinfunction "1_1") (pintype "passive"))
      (node (ref "SJ82") (pin "2") (pinfunction "2_2") (pintype "passive"))
      (node (ref "U3") (pin "31") (pinfunction "CS14_31") (pintype "bidirectional"))
    )
    (net (code "190") (name "LED_SOURCE_14_XFUNC") (class "Default")
      (node (ref "KEY_134") (pin "LED+") (pinfunction "LED+_LED+") (pintype "bidirectional"))
      (node (ref "SJ80") (pin "2") (pinfunction "2_2") (pintype "passive"))
    )
    (net (code "191") (name "NMI") (class "Default")
      (node (ref "C15") (pin "1") (pinfunction "1_1") (pintype "passive"))
      (node (ref "R11") (pin "1") (pinfunction "1_1") (pintype "passive"))
      (node (ref "U1") (pin "54") (pinfunction "PTA4/LLWU_P3_54") (pintype "bidirectional"))
    )
    (net (code "192") (name "Net-(D1-C)") (class "Default")
      (node (ref "D1") (pin "3") (pinfunction "C_3") (pintype "passive"))
      (node (ref "KEY_1") (pin "SW2") (pinfunction "SW2_SW2") (pintype "bidirectional"))
    )
    (net (code "193") (name "Net-(D2-C)") (class "Default")
      (node (ref "D2") (pin "3") (pinfunction "C_3") (pintype "passive"))
      (node (ref "KEY_2") (pin "SW2") (pinfunction "SW2_SW2") (pintype "bidirectional"))
    )
    (net (code "194") (name "Net-(D3-C)") (class "Default")
      (node (ref "D3") (pin "3") (pinfunction "C_3") (pintype "passive"))
      (node (ref "KEY_3") (pin "SW2") (pinfunction "SW2_SW2") (pintype "bidirectional"))
    )
    (net (code "195") (name "Net-(D4-C)") (class "Default")
      (node (ref "D4") (pin "3") (pinfunction "C_3") (pintype "passive"))
      (node (ref "KEY_4") (pin "SW2") (pinfunction "SW2_SW2") (pintype "bidirectional"))
    )
    (net (code "196") (name "Net-(D5-C)") (class "Default")
      (node (ref "D5") (pin "3") (pinfunction "C_3") (pintype "passive"))
      (node (ref "KEY_5") (pin "SW2") (pinfunction "SW2_SW2") (pintype "bidirectional"))
    )
    (net (code "197") (name "Net-(D6-C)") (class "Default")
      (node (ref "D6") (pin "3") (pinfunction "C_3") (pintype "passive"))
      (node (ref "KEY_6") (pin "SW2") (pinfunction "SW2_SW2") (pintype "bidirectional"))
    )
    (net (code "198") (name "Net-(D7-C)") (class "Default")
      (node (ref "D7") (pin "3") (pinfunction "C_3") (pintype "passive"))
      (node (ref "KEY_7") (pin "SW2") (pinfunction "SW2_SW2") (pintype "bidirectional"))
    )
    (net (code "199") (name "Net-(D8-C)") (class "Default")
      (node (ref "D8") (pin "3") (pinfunction "C_3") (pintype "passive"))
      (node (ref "KEY_8") (pin "SW2") (pinfunction "SW2_SW2") (pintype "bidirectional"))
    )
    (net (code "200") (name "Net-(D9-C)") (class "Default")
      (node (ref "D9") (pin "3") (pinfunction "C_3") (pintype "passive"))
      (node (ref "KEY_9") (pin "SW2") (pinfunction "SW2_SW2") (pintype "bidirectional"))
    )
    (net (code "201") (name "Net-(D10-C)") (class "Default")
      (node (ref "D10") (pin "3") (pinfunction "C_3") (pintype "passive"))
      (node (ref "KEY_10") (pin "SW2") (pinfunction "SW2_SW2") (pintype "bidirectional"))
    )
    (net (code "202") (name "Net-(D11-C)") (class "Default")
      (node (ref "D11") (pin "3") (pinfunction "C_3") (pintype "passive"))
      (node (ref "KEY_11") (pin "SW2") (pinfunction "SW2_SW2") (pintype "bidirectional"))
    )
    (net (code "203") (name "Net-(D12-C)") (class "Default")
      (node (ref "D12") (pin "3") (pinfunction "C_3") (pintype "passive"))
      (node (ref "KEY_12") (pin "SW2") (pinfunction "SW2_SW2") (pintype "bidirectional"))
    )
    (net (code "204") (name "Net-(D13-C)") (class "Default")
      (node (ref "D13") (pin "3") (pinfunction "C_3") (pintype "passive"))
      (node (ref "KEY_13") (pin "SW2") (pinfunction "SW2_SW2") (pintype "bidirectional"))
    )
    (net (code "205") (name "Net-(D14-C)") (class "Default")
      (node (ref "D14") (pin "3") (pinfunction "C_3") (pintype "passive"))
      (node (ref "KEY_14") (pin "SW2") (pinfunction "SW2_SW2") (pintype "bidirectional"))
    )
    (net (code "206") (name "Net-(D15-C)") (class "Default")
      (node (ref "D15") (pin "3") (pinfunction "C_3") (pintype "passive"))
      (node (ref "KEY_15") (pin "SW2") (pinfunction "SW2_SW2") (pintype "bidirectional"))
    )
    (net (code "207") (name "Net-(D16-C)") (class "Default")
      (node (ref "D16") (pin "3") (pinfunction "C_3") (pintype "passive"))
      (node (ref "KEY_16") (pin "SW2") (pinfunction "SW2_SW2") (pintype "bidirectional"))
    )
    (net (code "208") (name "Net-(D17-C)") (class "Default")
      (node (ref "D17") (pin "3") (pinfunction "C_3") (pintype "passive"))
      (node (ref "KEY_17") (pin "SW2") (pinfunction "SW2_SW2") (pintype "bidirectional"))
    )
    (net (code "209") (name "Net-(D18-C)") (class "Default")
      (node (ref "D18") (pin "3") (pinfunction "C_3") (pintype "passive"))
      (node (ref "KEY_18") (pin "SW2") (pinfunction "SW2_SW2") (pintype "bidirectional"))
    )
    (net (code "210") (name "Net-(D19-C)") (class "Default")
      (node (ref "D19") (pin "3") (pinfunction "C_3") (pintype "passive"))
      (node (ref "KEY_19") (pin "SW2") (pinfunction "SW2_SW2") (pintype "bidirectional"))
    )
    (net (code "211") (name "Net-(D20-C)") (class "Default")
      (node (ref "D20") (pin "3") (pinfunction "C_3") (pintype "passive"))
      (node (ref "KEY_20") (pin "SW2") (pinfunction "SW2_SW2") (pintype "bidirectional"))
    )
    (net (code "212") (name "Net-(D21-C)") (class "Default")
      (node (ref "D21") (pin "3") (pinfunction "C_3") (pintype "passive"))
      (node (ref "KEY_21") (pin "SW2") (pinfunction "SW2_SW2") (pintype "bidirectional"))
    )
    (net (code "213") (name "Net-(D22-C)") (class "Default")
      (node (ref "D22") (pin "3") (pinfunction "C_3") (pintype "passive"))
      (node (ref "KEY_22") (pin "SW2") (pinfunction "SW2_SW2") (pintype "bidirectional"))
    )
    (net (code "214") (name "Net-(D23-C)") (class "Default")
      (node (ref "D23") (pin "3") (pinfunction "C_3") (pintype "passive"))
      (node (ref "KEY_23") (pin "SW2") (pinfunction "SW2_SW2") (pintype "bidirectional"))
    )
    (net (code "215") (name "Net-(D24-C)") (class "Default")
      (node (ref "D24") (pin "3") (pinfunction "C_3") (pintype "passive"))
      (node (ref "KEY_24") (pin "SW2") (pinfunction "SW2_SW2") (pintype "bidirectional"))
    )
    (net (code "216") (name "Net-(D25-C)") (class "Default")
      (node (ref "D25") (pin "3") (pinfunction "C_3") (pintype "passive"))
      (node (ref "KEY_25") (pin "SW2") (pinfunction "SW2_SW2") (pintype "bidirectional"))
    )
    (net (code "217") (name "Net-(D26-C)") (class "Default")
      (node (ref "D26") (pin "3") (pinfunction "C_3") (pintype "passive"))
      (node (ref "KEY_26") (pin "SW2") (pinfunction "SW2_SW2") (pintype "bidirectional"))
    )
    (net (code "218") (name "Net-(D27-C)") (class "Default")
      (node (ref "D27") (pin "3") (pinfunction "C_3") (pintype "passive"))
      (node (ref "KEY_27") (pin "SW2") (pinfunction "SW2_SW2") (pintype "bidirectional"))
    )
    (net (code "219") (name "Net-(D28-C)") (class "Default")
      (node (ref "D28") (pin "3") (pinfunction "C_3") (pintype "passive"))
      (node (ref "KEY_28") (pin "SW2") (pinfunction "SW2_SW2") (pintype "bidirectional"))
    )
    (net (code "220") (name "Net-(D29-C)") (class "Default")
      (node (ref "D29") (pin "3") (pinfunction "C_3") (pintype "passive"))
      (node (ref "KEY_29") (pin "SW2") (pinfunction "SW2_SW2") (pintype "bidirectional"))
    )
    (net (code "221") (name "Net-(D30-C)") (class "Default")
      (node (ref "D30") (pin "3") (pinfunction "C_3") (pintype "passive"))
      (node (ref "KEY_30") (pin "SW2") (pinfunction "SW2_SW2") (pintype "bidirectional"))
      (node (ref "KEY_30_OFFSET") (pin "SW2") (pinfunction "SW2_SW2") (pintype "bidirectional"))
    )
    (net (code "222") (name "Net-(D31-C)") (class "Default")
      (node (ref "D31") (pin "3") (pinfunction "C_3") (pintype "passive"))
      (node (ref "KEY_31") (pin "SW2") (pinfunction "SW2_SW2") (pintype "bidirectional"))
      (node (ref "KEY_31_OFFSET") (pin "SW2") (pinfunction "SW2_SW2") (pintype "bidirectional"))
    )
    (net (code "223") (name "Net-(D32-C)") (class "Default")
      (node (ref "D32") (pin "3") (pinfunction "C_3") (pintype "passive"))
      (node (ref "KEY_32") (pin "SW2") (pinfunction "SW2_SW2") (pintype "bidirectional"))
      (node (ref "KEY_32_OFFSET") (pin "SW2") (pinfunction "SW2_SW2") (pintype "bidirectional"))
    )
    (net (code "224") (name "Net-(D33-C)") (class "Default")
      (node (ref "D33") (pin "3") (pinfunction "C_3") (pintype "passive"))
      (node (ref "KEY_33") (pin "SW2") (pinfunction "SW2_SW2") (pintype "bidirectional"))
      (node (ref "KEY_33_OFFSET") (pin "SW2") (pinfunction "SW2_SW2") (pintype "bidirectional"))
    )
    (net (code "225") (name "Net-(D34-C)") (class "Default")
      (node (ref "D34") (pin "3") (pinfunction "C_3") (pintype "passive"))
      (node (ref "KEY_34") (pin "SW2") (pinfunction "SW2_SW2") (pintype "bidirectional"))
    )
    (net (code "226") (name "Net-(D35-C)") (class "Default")
      (node (ref "D35") (pin "3") (pinfunction "C_3") (pintype "passive"))
      (node (ref "KEY_35") (pin "SW2") (pinfunction "SW2_SW2") (pintype "bidirectional"))
    )
    (net (code "227") (name "Net-(D36-C)") (class "Default")
      (node (ref "D36") (pin "3") (pinfunction "C_3") (pintype "passive"))
      (node (ref "KEY_36") (pin "SW2") (pinfunction "SW2_SW2") (pintype "bidirectional"))
    )
    (net (code "228") (name "Net-(D37-C)") (class "Default")
      (node (ref "D37") (pin "3") (pinfunction "C_3") (pintype "passive"))
      (node (ref "KEY_37") (pin "SW2") (pinfunction "SW2_SW2") (pintype "bidirectional"))
    )
    (net (code "229") (name "Net-(D38-C)") (class "Default")
      (node (ref "D38") (pin "3") (pinfunction "C_3") (pintype "passive"))
      (node (ref "KEY_38") (pin "SW2") (pinfunction "SW2_SW2") (pintype "bidirectional"))
    )
    (net (code "230") (name "Net-(D39-C)") (class "Default")
      (node (ref "D39") (pin "3") (pinfunction "C_3") (pintype "passive"))
      (node (ref "KEY_39") (pin "SW2") (pinfunction "SW2_SW2") (pintype "bidirectional"))
    )
    (net (code "231") (name "Net-(D40-C)") (class "Default")
      (node (ref "D40") (pin "3") (pinfunction "C_3") (pintype "passive"))
      (node (ref "KEY_40") (pin "SW2") (pinfunction "SW2_SW2") (pintype "bidirectional"))
    )
    (net (code "232") (name "Net-(D41-C)") (class "Default")
      (node (ref "D41") (pin "3") (pinfunction "C_3") (pintype "passive"))
      (node (ref "KEY_41") (pin "SW2") (pinfunction "SW2_SW2") (pintype "bidirectional"))
    )
    (net (code "233") (name "Net-(D42-C)") (class "Default")
      (node (ref "D42") (pin "3") (pinfunction "C_3") (pintype "passive"))
      (node (ref "KEY_42") (pin "SW2") (pinfunction "SW2_SW2") (pintype "bidirectional"))
    )
    (net (code "234") (name "Net-(D43-C)") (class "Default")
      (node (ref "D43") (pin "3") (pinfunction "C_3") (pintype "passive"))
      (node (ref "KEY_43") (pin "SW2") (pinfunction "SW2_SW2") (pintype "bidirectional"))
    )
    (net (code "235") (name "Net-(D44-C)") (class "Default")
      (node (ref "D44") (pin "3") (pinfunction "C_3") (pintype "passive"))
      (node (ref "KEY_44") (pin "SW2") (pinfunction "SW2_SW2") (pintype "bidirectional"))
    )
    (net (code "236") (name "Net-(D45-C)") (class "Default")
      (node (ref "D45") (pin "3") (pinfunction "C_3") (pintype "passive"))
      (node (ref "KEY_45") (pin "SW2") (pinfunction "SW2_SW2") (pintype "bidirectional"))
    )
    (net (code "237") (name "Net-(D46-C)") (class "Default")
      (node (ref "D46") (pin "3") (pinfunction "C_3") (pintype "passive"))
      (node (ref "KEY_46") (pin "SW2") (pinfunction "SW2_SW2") (pintype "bidirectional"))
    )
    (net (code "238") (name "Net-(D47-C)") (class "Default")
      (node (ref "D47") (pin "3") (pinfunction "C_3") (pintype "passive"))
      (node (ref "KEY_47") (pin "SW2") (pinfunction "SW2_SW2") (pintype "bidirectional"))
    )
    (net (code "239") (name "Net-(D48-C)") (class "Default")
      (node (ref "D48") (pin "3") (pinfunction "C_3") (pintype "passive"))
      (node (ref "KEY_48") (pin "SW2") (pinfunction "SW2_SW2") (pintype "bidirectional"))
    )
    (net (code "240") (name "Net-(D49-C)") (class "Default")
      (node (ref "D49") (pin "3") (pinfunction "C_3") (pintype "passive"))
      (node (ref "KEY_49") (pin "SW2") (pinfunction "SW2_SW2") (pintype "bidirectional"))
    )
    (net (code "241") (name "Net-(D50-C)") (class "Default")
      (node (ref "D50") (pin "3") (pinfunction "C_3") (pintype "passive"))
      (node (ref "KEY_50") (pin "SW2") (pinfunction "SW2_SW2") (pintype "bidirectional"))
    )
    (net (code "242") (name "Net-(D51-C)") (class "Default")
      (node (ref "D51") (pin "3") (pinfunction "C_3") (pintype "passive"))
      (node (ref "KEY_51") (pin "SW2") (pinfunction "SW2_SW2") (pintype "bidirectional"))
    )
    (net (code "243") (name "Net-(D52-C)") (class "Default")
      (node (ref "D52") (pin "3") (pinfunction "C_3") (pintype "passive"))
      (node (ref "KEY_52") (pin "SW2") (pinfunction "SW2_SW2") (pintype "bidirectional"))
    )
    (net (code "244") (name "Net-(D53-C)") (class "Default")
      (node (ref "D53") (pin "3") (pinfunction "C_3") (pintype "passive"))
      (node (ref "KEY_53") (pin "SW2") (pinfunction "SW2_SW2") (pintype "bidirectional"))
    )
    (net (code "245") (name "Net-(D54-C)") (class "Default")
      (node (ref "D54") (pin "3") (pinfunction "C_3") (pintype "passive"))
      (node (ref "KEY_54") (pin "SW2") (pinfunction "SW2_SW2") (pintype "bidirectional"))
    )
    (net (code "246") (name "Net-(D55-C)") (class "Default")
      (node (ref "D55") (pin "3") (pinfunction "C_3") (pintype "passive"))
      (node (ref "KEY_55") (pin "SW2") (pinfunction "SW2_SW2") (pintype "bidirectional"))
    )
    (net (code "247") (name "Net-(D56-C)") (class "Default")
      (node (ref "D56") (pin "3") (pinfunction "C_3") (pintype "passive"))
      (node (ref "KEY_56") (pin "SW2") (pinfunction "SW2_SW2") (pintype "bidirectional"))
    )
    (net (code "248") (name "Net-(D57-C)") (class "Default")
      (node (ref "D57") (pin "3") (pinfunction "C_3") (pintype "passive"))
      (node (ref "KEY_57") (pin "SW2") (pinfunction "SW2_SW2") (pintype "bidirectional"))
    )
    (net (code "249") (name "Net-(D58-C)") (class "Default")
      (node (ref "D58") (pin "3") (pinfunction "C_3") (pintype "passive"))
      (node (ref "KEY_58") (pin "SW2") (pinfunction "SW2_SW2") (pintype "bidirectional"))
    )
    (net (code "250") (name "Net-(D59-C)") (class "Default")
      (node (ref "D59") (pin "3") (pinfunction "C_3") (pintype "passive"))
      (node (ref "KEY_59") (pin "SW2") (pinfunction "SW2_SW2") (pintype "bidirectional"))
    )
    (net (code "251") (name "Net-(D60-C)") (class "Default")
      (node (ref "D60") (pin "3") (pinfunction "C_3") (pintype "passive"))
      (node (ref "KEY_60") (pin "SW2") (pinfunction "SW2_SW2") (pintype "bidirectional"))
    )
    (net (code "252") (name "Net-(D61-C)") (class "Default")
      (node (ref "D61") (pin "3") (pinfunction "C_3") (pintype "passive"))
      (node (ref "KEY_61") (pin "SW2") (pinfunction "SW2_SW2") (pintype "bidirectional"))
    )
    (net (code "253") (name "Net-(D62-C)") (class "Default")
      (node (ref "D62") (pin "3") (pinfunction "C_3") (pintype "passive"))
      (node (ref "KEY_62") (pin "SW2") (pinfunction "SW2_SW2") (pintype "bidirectional"))
    )
    (net (code "254") (name "Net-(D63-C)") (class "Default")
      (node (ref "D63") (pin "3") (pinfunction "C_3") (pintype "passive"))
      (node (ref "KEY_63") (pin "SW2") (pinfunction "SW2_SW2") (pintype "bidirectional"))
    )
    (net (code "255") (name "Net-(D64-C)") (class "Default")
      (node (ref "D64") (pin "3") (pinfunction "C_3") (pintype "passive"))
      (node (ref "KEY_64") (pin "SW2") (pinfunction "SW2_SW2") (pintype "bidirectional"))
    )
    (net (code "256") (name "Net-(D65-C)") (class "Default")
      (node (ref "D65") (pin "3") (pinfunction "C_3") (pintype "passive"))
      (node (ref "KEY_65") (pin "SW2") (pinfunction "SW2_SW2") (pintype "bidirectional"))
    )
    (net (code "257") (name "Net-(D66-C)") (class "Default")
      (node (ref "D66") (pin "3") (pinfunction "C_3") (pintype "passive"))
      (node (ref "KEY_66") (pin "SW2") (pinfunction "SW2_SW2") (pintype "bidirectional"))
    )
    (net (code "258") (name "Net-(D67-C)") (class "Default")
      (node (ref "D67") (pin "3") (pinfunction "C_3") (pintype "passive"))
      (node (ref "KEY_67") (pin "SW2") (pinfunction "SW2_SW2") (pintype "bidirectional"))
    )
    (net (code "259") (name "Net-(D68-C)") (class "Default")
      (node (ref "D68") (pin "3") (pinfunction "C_3") (pintype "passive"))
      (node (ref "KEY_68") (pin "SW2") (pinfunction "SW2_SW2") (pintype "bidirectional"))
    )
    (net (code "260") (name "Net-(D69-C)") (class "Default")
      (node (ref "D69") (pin "3") (pinfunction "C_3") (pintype "passive"))
      (node (ref "KEY_69") (pin "SW2") (pinfunction "SW2_SW2") (pintype "bidirectional"))
    )
    (net (code "261") (name "Net-(D70-C)") (class "Default")
      (node (ref "D70") (pin "3") (pinfunction "C_3") (pintype "passive"))
      (node (ref "KEY_70") (pin "SW2") (pinfunction "SW2_SW2") (pintype "bidirectional"))
    )
    (net (code "262") (name "Net-(D71-C)") (class "Default")
      (node (ref "D71") (pin "3") (pinfunction "C_3") (pintype "passive"))
      (node (ref "KEY_71") (pin "SW2") (pinfunction "SW2_SW2") (pintype "bidirectional"))
    )
    (net (code "263") (name "Net-(D72-C)") (class "Default")
      (node (ref "D72") (pin "3") (pinfunction "C_3") (pintype "passive"))
      (node (ref "KEY_72") (pin "SW2") (pinfunction "SW2_SW2") (pintype "bidirectional"))
    )
    (net (code "264") (name "Net-(D73-C)") (class "Default")
      (node (ref "D73") (pin "3") (pinfunction "C_3") (pintype "passive"))
      (node (ref "KEY_73") (pin "SW2") (pinfunction "SW2_SW2") (pintype "bidirectional"))
    )
    (net (code "265") (name "Net-(D74-C)") (class "Default")
      (node (ref "D74") (pin "3") (pinfunction "C_3") (pintype "passive"))
      (node (ref "KEY_74") (pin "SW2") (pinfunction "SW2_SW2") (pintype "bidirectional"))
    )
    (net (code "266") (name "Net-(D75-C)") (class "Default")
      (node (ref "D75") (pin "3") (pinfunction "C_3") (pintype "passive"))
      (node (ref "KEY_75") (pin "SW2") (pinfunction "SW2_SW2") (pintype "bidirectional"))
    )
    (net (code "267") (name "Net-(D76-C)") (class "Default")
      (node (ref "D76") (pin "3") (pinfunction "C_3") (pintype "passive"))
      (node (ref "KEY_76") (pin "SW2") (pinfunction "SW2_SW2") (pintype "bidirectional"))
    )
    (net (code "268") (name "Net-(D77-C)") (class "Default")
      (node (ref "D77") (pin "3") (pinfunction "C_3") (pintype "passive"))
      (node (ref "KEY_77") (pin "SW2") (pinfunction "SW2_SW2") (pintype "bidirectional"))
    )
    (net (code "269") (name "Net-(D78-C)") (class "Default")
      (node (ref "D78") (pin "3") (pinfunction "C_3") (pintype "passive"))
      (node (ref "KEY_78") (pin "SW2") (pinfunction "SW2_SW2") (pintype "bidirectional"))
    )
    (net (code "270") (name "Net-(D79-C)") (class "Default")
      (node (ref "D79") (pin "3") (pinfunction "C_3") (pintype "passive"))
      (node (ref "KEY_79") (pin "SW2") (pinfunction "SW2_SW2") (pintype "bidirectional"))
    )
    (net (code "271") (name "Net-(D80-C)") (class "Default")
      (node (ref "D80") (pin "3") (pinfunction "C_3") (pintype "passive"))
      (node (ref "KEY_80") (pin "SW2") (pinfunction "SW2_SW2") (pintype "bidirectional"))
    )
    (net (code "272") (name "Net-(D81-C)") (class "Default")
      (node (ref "D81") (pin "3") (pinfunction "C_3") (pintype "passive"))
      (node (ref "KEY_81") (pin "SW2") (pinfunction "SW2_SW2") (pintype "bidirectional"))
    )
    (net (code "273") (name "Net-(D82-C)") (class "Default")
      (node (ref "D82") (pin "3") (pinfunction "C_3") (pintype "passive"))
      (node (ref "KEY_82") (pin "SW2") (pinfunction "SW2_SW2") (pintype "bidirectional"))
    )
    (net (code "274") (name "Net-(D83-C)") (class "Default")
      (node (ref "D83") (pin "3") (pinfunction "C_3") (pintype "passive"))
      (node (ref "KEY_83") (pin "SW2") (pinfunction "SW2_SW2") (pintype "bidirectional"))
    )
    (net (code "275") (name "Net-(D84-C)") (class "Default")
      (node (ref "D84") (pin "3") (pinfunction "C_3") (pintype "passive"))
      (node (ref "KEY_84") (pin "SW2") (pinfunction "SW2_SW2") (pintype "bidirectional"))
    )
    (net (code "276") (name "Net-(D85-C)") (class "Default")
      (node (ref "D85") (pin "3") (pinfunction "C_3") (pintype "passive"))
      (node (ref "KEY_85") (pin "SW2") (pinfunction "SW2_SW2") (pintype "bidirectional"))
    )
    (net (code "277") (name "Net-(D86-C)") (class "Default")
      (node (ref "D86") (pin "3") (pinfunction "C_3") (pintype "passive"))
      (node (ref "KEY_86") (pin "SW2") (pinfunction "SW2_SW2") (pintype "bidirectional"))
    )
    (net (code "278") (name "Net-(D87-C)") (class "Default")
      (node (ref "D87") (pin "3") (pinfunction "C_3") (pintype "passive"))
      (node (ref "KEY_87") (pin "SW2") (pinfunction "SW2_SW2") (pintype "bidirectional"))
    )
    (net (code "279") (name "Net-(D88-C)") (class "Default")
      (node (ref "D88") (pin "3") (pinfunction "C_3") (pintype "passive"))
      (node (ref "KEY_88") (pin "SW2") (pinfunction "SW2_SW2") (pintype "bidirectional"))
    )
    (net (code "280") (name "Net-(D89-C)") (class "Default")
      (node (ref "D89") (pin "3") (pinfunction "C_3") (pintype "passive"))
      (node (ref "KEY_89") (pin "SW2") (pinfunction "SW2_SW2") (pintype "bidirectional"))
    )
    (net (code "281") (name "Net-(D90-C)") (class "Default")
      (node (ref "D90") (pin "3") (pinfunction "C_3") (pintype "passive"))
      (node (ref "KEY_90") (pin "SW2") (pinfunction "SW2_SW2") (pintype "bidirectional"))
    )
    (net (code "282") (name "Net-(D91-C)") (class "Default")
      (node (ref "D91") (pin "3") (pinfunction "C_3") (pintype "passive"))
      (node (ref "KEY_91") (pin "SW2") (pinfunction "SW2_SW2") (pintype "bidirectional"))
    )
    (net (code "283") (name "Net-(D92-C)") (class "Default")
      (node (ref "D92") (pin "3") (pinfunction "C_3") (pintype "passive"))
      (node (ref "KEY_92") (pin "SW2") (pinfunction "SW2_SW2") (pintype "bidirectional"))
    )
    (net (code "284") (name "Net-(D93-C)") (class "Default")
      (node (ref "D93") (pin "3") (pinfunction "C_3") (pintype "passive"))
      (node (ref "KEY_93") (pin "SW2") (pinfunction "SW2_SW2") (pintype "bidirectional"))
    )
    (net (code "285") (name "Net-(D94-C)") (class "Default")
      (node (ref "D94") (pin "3") (pinfunction "C_3") (pintype "passive"))
      (node (ref "KEY_94") (pin "SW2") (pinfunction "SW2_SW2") (pintype "bidirectional"))
    )
    (net (code "286") (name "Net-(D95-C)") (class "Default")
      (node (ref "D95") (pin "3") (pinfunction "C_3") (pintype "passive"))
      (node (ref "KEY_95") (pin "SW2") (pinfunction "SW2_SW2") (pintype "bidirectional"))
    )
    (net (code "287") (name "Net-(D96-C)") (class "Default")
      (node (ref "D96") (pin "3") (pinfunction "C_3") (pintype "passive"))
      (node (ref "KEY_96") (pin "SW2") (pinfunction "SW2_SW2") (pintype "bidirectional"))
    )
    (net (code "288") (name "Net-(D97-C)") (class "Default")
      (node (ref "D97") (pin "3") (pinfunction "C_3") (pintype "passive"))
      (node (ref "KEY_97") (pin "SW2") (pinfunction "SW2_SW2") (pintype "bidirectional"))
    )
    (net (code "289") (name "Net-(D98-C)") (class "Default")
      (node (ref "D98") (pin "3") (pinfunction "C_3") (pintype "passive"))
      (node (ref "KEY_98") (pin "SW2") (pinfunction "SW2_SW2") (pintype "bidirectional"))
    )
    (net (code "290") (name "Net-(D99-C)") (class "Default")
      (node (ref "D99") (pin "3") (pinfunction "C_3") (pintype "passive"))
      (node (ref "KEY_99") (pin "SW2") (pinfunction "SW2_SW2") (pintype "bidirectional"))
    )
    (net (code "291") (name "Net-(D100-C)") (class "Default")
      (node (ref "D100") (pin "3") (pinfunction "C_3") (pintype "passive"))
      (node (ref "KEY_100") (pin "SW2") (pinfunction "SW2_SW2") (pintype "bidirectional"))
    )
    (net (code "292") (name "Net-(D101-C)") (class "Default")
      (node (ref "D101") (pin "3") (pinfunction "C_3") (pintype "passive"))
      (node (ref "KEY_101") (pin "SW2") (pinfunction "SW2_SW2") (pintype "bidirectional"))
    )
    (net (code "293") (name "Net-(D102-C)") (class "Default")
      (node (ref "D102") (pin "3") (pinfunction "C_3") (pintype "passive"))
      (node (ref "KEY_102") (pin "SW2") (pinfunction "SW2_SW2") (pintype "bidirectional"))
    )
    (net (code "294") (name "Net-(D103-C)") (class "Default")
      (node (ref "D103") (pin "3") (pinfunction "C_3") (pintype "passive"))
      (node (ref "KEY_103") (pin "SW2") (pinfunction "SW2_SW2") (pintype "bidirectional"))
    )
    (net (code "295") (name "Net-(D104-C)") (class "Default")
      (node (ref "D104") (pin "3") (pinfunction "C_3") (pintype "passive"))
      (node (ref "KEY_104") (pin "SW2") (pinfunction "SW2_SW2") (pintype "bidirectional"))
    )
    (net (code "296") (name "Net-(D105-C)") (class "Default")
      (node (ref "D105") (pin "3") (pinfunction "C_3") (pintype "passive"))
      (node (ref "KEY_105") (pin "SW2") (pinfunction "SW2_SW2") (pintype "bidirectional"))
    )
    (net (code "297") (name "Net-(D106-C)") (class "Default")
      (node (ref "D106") (pin "3") (pinfunction "C_3") (pintype "passive"))
      (node (ref "KEY_106") (pin "SW2") (pinfunction "SW2_SW2") (pintype "bidirectional"))
    )
    (net (code "298") (name "Net-(D107-C)") (class "Default")
      (node (ref "D107") (pin "3") (pinfunction "C_3") (pintype "passive"))
      (node (ref "KEY_107") (pin "SW2") (pinfunction "SW2_SW2") (pintype "bidirectional"))
    )
    (net (code "299") (name "Net-(D108-C)") (class "Default")
      (node (ref "D108") (pin "3") (pinfunction "C_3") (pintype "passive"))
      (node (ref "KEY_108") (pin "SW2") (pinfunction "SW2_SW2") (pintype "bidirectional"))
    )
    (net (code "300") (name "Net-(D109-C)") (class "Default")
      (node (ref "D109") (pin "3") (pinfunction "C_3") (pintype "passive"))
      (node (ref "KEY_109") (pin "SW2") (pinfunction "SW2_SW2") (pintype "bidirectional"))
    )
    (net (code "301") (name "Net-(D110-C)") (class "Default")
      (node (ref "D110") (pin "3") (pinfunction "C_3") (pintype "passive"))
      (node (ref "KEY_110") (pin "SW2") (pinfunction "SW2_SW2") (pintype "bidirectional"))
    )
    (net (code "302") (name "Net-(D111-C)") (class "Default")
      (node (ref "D111") (pin "3") (pinfunction "C_3") (pintype "passive"))
      (node (ref "KEY_111") (pin "SW2") (pinfunction "SW2_SW2") (pintype "bidirectional"))
    )
    (net (code "303") (name "Net-(D112-C)") (class "Default")
      (node (ref "D112") (pin "3") (pinfunction "C_3") (pintype "passive"))
      (node (ref "KEY_112") (pin "SW2") (pinfunction "SW2_SW2") (pintype "bidirectional"))
    )
    (net (code "304") (name "Net-(D113-C)") (class "Default")
      (node (ref "D113") (pin "3") (pinfunction "C_3") (pintype "passive"))
      (node (ref "KEY_113") (pin "SW2") (pinfunction "SW2_SW2") (pintype "bidirectional"))
    )
    (net (code "305") (name "Net-(D114-C)") (class "Default")
      (node (ref "D114") (pin "3") (pinfunction "C_3") (pintype "passive"))
      (node (ref "KEY_114") (pin "SW2") (pinfunction "SW2_SW2") (pintype "bidirectional"))
    )
    (net (code "306") (name "Net-(D115-C)") (class "Default")
      (node (ref "D115") (pin "3") (pinfunction "C_3") (pintype "passive"))
      (node (ref "KEY_115") (pin "SW2") (pinfunction "SW2_SW2") (pintype "bidirectional"))
    )
    (net (code "307") (name "Net-(D116-C)") (class "Default")
      (node (ref "D116") (pin "3") (pinfunction "C_3") (pintype "passive"))
      (node (ref "KEY_116") (pin "SW2") (pinfunction "SW2_SW2") (pintype "bidirectional"))
    )
    (net (code "308") (name "Net-(D117-C)") (class "Default")
      (node (ref "D117") (pin "3") (pinfunction "C_3") (pintype "passive"))
      (node (ref "KEY_117") (pin "SW2") (pinfunction "SW2_SW2") (pintype "bidirectional"))
    )
    (net (code "309") (name "Net-(D118-C)") (class "Default")
      (node (ref "D118") (pin "3") (pinfunction "C_3") (pintype "passive"))
      (node (ref "KEY_118") (pin "SW2") (pinfunction "SW2_SW2") (pintype "bidirectional"))
    )
    (net (code "310") (name "Net-(D119-C)") (class "Default")
      (node (ref "D119") (pin "3") (pinfunction "C_3") (pintype "passive"))
      (node (ref "KEY_119") (pin "SW2") (pinfunction "SW2_SW2") (pintype "bidirectional"))
    )
    (net (code "311") (name "Net-(D120-C)") (class "Default")
      (node (ref "D120") (pin "3") (pinfunction "C_3") (pintype "passive"))
      (node (ref "KEY_120") (pin "SW2") (pinfunction "SW2_SW2") (pintype "bidirectional"))
    )
    (net (code "312") (name "Net-(D121-C)") (class "Default")
      (node (ref "D121") (pin "3") (pinfunction "C_3") (pintype "passive"))
      (node (ref "KEY_121") (pin "SW2") (pinfunction "SW2_SW2") (pintype "bidirectional"))
    )
    (net (code "313") (name "Net-(D122-C)") (class "Default")
      (node (ref "D122") (pin "3") (pinfunction "C_3") (pintype "passive"))
      (node (ref "KEY_122") (pin "SW2") (pinfunction "SW2_SW2") (pintype "bidirectional"))
    )
    (net (code "314") (name "Net-(D123-C)") (class "Default")
      (node (ref "D123") (pin "3") (pinfunction "C_3") (pintype "passive"))
      (node (ref "KEY_123") (pin "SW2") (pinfunction "SW2_SW2") (pintype "bidirectional"))
    )
    (net (code "315") (name "Net-(D124-C)") (class "Default")
      (node (ref "D124") (pin "3") (pinfunction "C_3") (pintype "passive"))
      (node (ref "KEY_124") (pin "SW2") (pinfunction "SW2_SW2") (pintype "bidirectional"))
    )
    (net (code "316") (name "Net-(D125-C)") (class "Default")
      (node (ref "D125") (pin "3") (pinfunction "C_3") (pintype "passive"))
      (node (ref "KEY_125") (pin "SW2") (pinfunction "SW2_SW2") (pintype "bidirectional"))
    )
    (net (code "317") (name "Net-(D126-C)") (class "Default")
      (node (ref "D126") (pin "3") (pinfunction "C_3") (pintype "passive"))
      (node (ref "KEY_126") (pin "SW2") (pinfunction "SW2_SW2") (pintype "bidirectional"))
    )
    (net (code "318") (name "Net-(D127-C)") (class "Default")
      (node (ref "D127") (pin "3") (pinfunction "C_3") (pintype "passive"))
      (node (ref "KEY_127") (pin "SW2") (pinfunction "SW2_SW2") (pintype "bidirectional"))
    )
    (net (code "319") (name "Net-(D128-C)") (class "Default")
      (node (ref "D128") (pin "3") (pinfunction "C_3") (pintype "passive"))
      (node (ref "KEY_128") (pin "SW2") (pinfunction "SW2_SW2") (pintype "bidirectional"))
    )
    (net (code "320") (name "Net-(D129-C)") (class "Default")
      (node (ref "D129") (pin "3") (pinfunction "C_3") (pintype "passive"))
      (node (ref "KEY_129") (pin "SW2") (pinfunction "SW2_SW2") (pintype "bidirectional"))
    )
    (net (code "321") (name "Net-(D130-C)") (class "Default")
      (node (ref "D130") (pin "3") (pinfunction "C_3") (pintype "passive"))
      (node (ref "KEY_130") (pin "SW2") (pinfunction "SW2_SW2") (pintype "bidirectional"))
    )
    (net (code "322") (name "Net-(D131-C)") (class "Default")
      (node (ref "D131") (pin "3") (pinfunction "C_3") (pintype "passive"))
      (node (ref "KEY_131") (pin "SW2") (pinfunction "SW2_SW2") (pintype "bidirectional"))
    )
    (net (code "323") (name "Net-(D132-C)") (class "Default")
      (node (ref "D132") (pin "3") (pinfunction "C_3") (pintype "passive"))
      (node (ref "KEY_132") (pin "SW2") (pinfunction "SW2_SW2") (pintype "bidirectional"))
    )
    (net (code "324") (name "Net-(D133-C)") (class "Default")
      (node (ref "D133") (pin "3") (pinfunction "C_3") (pintype "passive"))
      (node (ref "KEY_133") (pin "SW2") (pinfunction "SW2_SW2") (pintype "bidirectional"))
    )
    (net (code "325") (name "Net-(D134-C)") (class "Default")
      (node (ref "D134") (pin "3") (pinfunction "C_3") (pintype "passive"))
      (node (ref "KEY_134") (pin "SW2") (pinfunction "SW2_SW2") (pintype "bidirectional"))
    )
    (net (code "326") (name "Net-(D135-C)") (class "Default")
      (node (ref "D135") (pin "3") (pinfunction "C_3") (pintype "passive"))
      (node (ref "KEY_135") (pin "SW2") (pinfunction "SW2_SW2") (pintype "bidirectional"))
    )
    (net (code "327") (name "Net-(D136-C)") (class "Default")
      (node (ref "D136") (pin "3") (pinfunction "C_3") (pintype "passive"))
      (node (ref "KEY_136") (pin "SW2") (pinfunction "SW2_SW2") (pintype "bidirectional"))
    )
    (net (code "328") (name "Net-(D137-C)") (class "Default")
      (node (ref "D137") (pin "3") (pinfunction "C_3") (pintype "passive"))
      (node (ref "KEY_137") (pin "SW2") (pinfunction "SW2_SW2") (pintype "bidirectional"))
    )
    (net (code "329") (name "Net-(D138-C)") (class "Default")
      (node (ref "D138") (pin "3") (pinfunction "C_3") (pintype "passive"))
      (node (ref "KEY_138") (pin "SW2") (pinfunction "SW2_SW2") (pintype "bidirectional"))
    )
    (net (code "330") (name "Net-(D139-C)") (class "Default")
      (node (ref "D139") (pin "3") (pinfunction "C_3") (pintype "passive"))
      (node (ref "KEY_139") (pin "SW2") (pinfunction "SW2_SW2") (pintype "bidirectional"))
    )
    (net (code "331") (name "Net-(D140-C)") (class "Default")
      (node (ref "D140") (pin "3") (pinfunction "C_3") (pintype "passive"))
      (node (ref "KEY_140") (pin "SW2") (pinfunction "SW2_SW2") (pintype "bidirectional"))
    )
    (net (code "332") (name "Net-(D141-C)") (class "Default")
      (node (ref "D141") (pin "3") (pinfunction "C_3") (pintype "passive"))
      (node (ref "KEY_141") (pin "SW2") (pinfunction "SW2_SW2") (pintype "bidirectional"))
    )
    (net (code "333") (name "Net-(D142-C)") (class "Default")
      (node (ref "D142") (pin "3") (pinfunction "C_3") (pintype "passive"))
      (node (ref "KEY_142") (pin "SW2") (pinfunction "SW2_SW2") (pintype "bidirectional"))
    )
    (net (code "334") (name "Net-(D143-C)") (class "Default")
      (node (ref "D143") (pin "3") (pinfunction "C_3") (pintype "passive"))
      (node (ref "KEY_143") (pin "SW2") (pinfunction "SW2_SW2") (pintype "bidirectional"))
    )
    (net (code "335") (name "Net-(D144-C)") (class "Default")
      (node (ref "D144") (pin "3") (pinfunction "C_3") (pintype "passive"))
      (node (ref "KEY_144") (pin "SW2") (pinfunction "SW2_SW2") (pintype "bidirectional"))
    )
    (net (code "336") (name "Net-(D145-C)") (class "Default")
      (node (ref "D145") (pin "3") (pinfunction "C_3") (pintype "passive"))
      (node (ref "KEY_145") (pin "SW2") (pinfunction "SW2_SW2") (pintype "bidirectional"))
    )
    (net (code "337") (name "Net-(D146-C)") (class "Default")
      (node (ref "D146") (pin "3") (pinfunction "C_3") (pintype "passive"))
      (node (ref "KEY_146") (pin "SW2") (pinfunction "SW2_SW2") (pintype "bidirectional"))
    )
    (net (code "338") (name "Net-(D147-C)") (class "Default")
      (node (ref "D147") (pin "3") (pinfunction "C_3") (pintype "passive"))
      (node (ref "KEY_147") (pin "SW2") (pinfunction "SW2_SW2") (pintype "bidirectional"))
    )
    (net (code "339") (name "Net-(D148-C)") (class "Default")
      (node (ref "D148") (pin "3") (pinfunction "C_3") (pintype "passive"))
      (node (ref "KEY_148") (pin "SW2") (pinfunction "SW2_SW2") (pintype "bidirectional"))
    )
    (net (code "340") (name "Net-(D149-C)") (class "Default")
      (node (ref "D149") (pin "3") (pinfunction "C_3") (pintype "passive"))
      (node (ref "KEY_149") (pin "SW2") (pinfunction "SW2_SW2") (pintype "bidirectional"))
    )
    (net (code "341") (name "Net-(D150-C)") (class "Default")
      (node (ref "D150") (pin "3") (pinfunction "C_3") (pintype "passive"))
      (node (ref "KEY_150") (pin "SW2") (pinfunction "SW2_SW2") (pintype "bidirectional"))
    )
    (net (code "342") (name "Net-(D151-C)") (class "Default")
      (node (ref "D151") (pin "3") (pinfunction "C_3") (pintype "passive"))
      (node (ref "KEY_151") (pin "SW2") (pinfunction "SW2_SW2") (pintype "bidirectional"))
    )
    (net (code "343") (name "Net-(D152-C)") (class "Default")
      (node (ref "D152") (pin "3") (pinfunction "C_3") (pintype "passive"))
      (node (ref "KEY_152") (pin "SW2") (pinfunction "SW2_SW2") (pintype "bidirectional"))
    )
    (net (code "344") (name "Net-(D153-C)") (class "Default")
      (node (ref "D153") (pin "3") (pinfunction "C_3") (pintype "passive"))
      (node (ref "KEY_153") (pin "SW2") (pinfunction "SW2_SW2") (pintype "bidirectional"))
    )
    (net (code "345") (name "Net-(J1-CC1)") (class "Default")
      (node (ref "J1") (pin "A5") (pinfunction "CC1_A5") (pintype "bidirectional"))
      (node (ref "R12") (pin "2") (pinfunction "2_2") (pintype "passive"))
    )
    (net (code "346") (name "Net-(J1-CC2)") (class "Default")
      (node (ref "J1") (pin "B5") (pinfunction "CC2_B5") (pintype "bidirectional"))
      (node (ref "R13") (pin "1") (pinfunction "1_1") (pintype "passive"))
    )
    (net (code "347") (name "Net-(J1-SHELL_GND-PadS1)") (class "Default")
      (node (ref "J1") (pin "S1") (pinfunction "SHELL_GND_S1") (pintype "power_in"))
      (node (ref "J1") (pin "S2") (pinfunction "SHELL_GND_S2") (pintype "power_in"))
      (node (ref "J1") (pin "S3") (pinfunction "SHELL_GND_S3") (pintype "power_in"))
      (node (ref "J1") (pin "S4") (pinfunction "SHELL_GND_S4") (pintype "power_in"))
      (node (ref "L2") (pin "1") (pinfunction "1_1") (pintype "bidirectional"))
    )
    (net (code "348") (name "Net-(U3-ISET)") (class "Default")
      (node (ref "R4") (pin "2") (pinfunction "2_2") (pintype "passive"))
      (node (ref "U3") (pin "35") (pinfunction "ISET_35") (pintype "bidirectional"))
    )
    (net (code "349") (name "RESET") (class "Default")
      (node (ref "C1") (pin "1") (pinfunction "1_1") (pintype "passive"))
      (node (ref "J2") (pin "10") (pinfunction "NRESET_10") (pintype "bidirectional"))
      (node (ref "R1") (pin "1") (pinfunction "1_1") (pintype "passive"))
      (node (ref "SW1") (pin "1") (pinfunction "1_1") (pintype "passive"))
      (node (ref "SW1") (pin "2") (pinfunction "2_2") (pintype "passive"))
      (node (ref "U1") (pin "74") (pinfunction "RESET_B_74") (pintype "passive"))
    )
    (net (code "350") (name "ROW_1") (class "Default")
      (node (ref "SJ35") (pin "2") (pinfunction "2_2") (pintype "passive"))
      (node (ref "SJ_MCU_ROW1") (pin "1") (pinfunction "1_1") (pintype "passive"))
    )
    (net (code "351") (name "ROW_1_NUM") (class "Default")
      (node (ref "D150") (pin "1") (pinfunction "A_1") (pintype "passive"))
      (node (ref "D151") (pin "1") (pinfunction "A_1") (pintype "passive"))
      (node (ref "D152") (pin "1") (pinfunction "A_1") (pintype "passive"))
      (node (ref "D153") (pin "1") (pinfunction "A_1") (pintype "passive"))
      (node (ref "SJ36") (pin "1") (pinfunction "1_1") (pintype "passive"))
    )
    (net (code "352") (name "ROW_1_QWERTY") (class "Default")
      (node (ref "D10") (pin "1") (pinfunction "A_1") (pintype "passive"))
      (node (ref "D11") (pin "1") (pinfunction "A_1") (pintype "passive"))
      (node (ref "D12") (pin "1") (pinfunction "A_1") (pintype "passive"))
      (node (ref "D13") (pin "1") (pinfunction "A_1") (pintype "passive"))
      (node (ref "D14") (pin "1") (pinfunction "A_1") (pintype "passive"))
      (node (ref "D15") (pin "1") (pinfunction "A_1") (pintype "passive"))
      (node (ref "D16") (pin "1") (pinfunction "A_1") (pintype "passive"))
      (node (ref "D17") (pin "1") (pinfunction "A_1") (pintype "passive"))
      (node (ref "D18") (pin "1") (pinfunction "A_1") (pintype "passive"))
      (node (ref "D19") (pin "1") (pinfunction "A_1") (pintype "passive"))
      (node (ref "D20") (pin "1") (pinfunction "A_1") (pintype "passive"))
      (node (ref "D3") (pin "1") (pinfunction "A_1") (pintype "passive"))
      (node (ref "D4") (pin "1") (pinfunction "A_1") (pintype "passive"))
      (node (ref "D5") (pin "1") (pinfunction "A_1") (pintype "passive"))
      (node (ref "D6") (pin "1") (pinfunction "A_1") (pintype "passive"))
      (node (ref "D7") (pin "1") (pinfunction "A_1") (pintype "passive"))
      (node (ref "D8") (pin "1") (pinfunction "A_1") (pintype "passive"))
      (node (ref "D9") (pin "1") (pinfunction "A_1") (pintype "passive"))
      (node (ref "SJ26") (pin "1") (pinfunction "1_1") (pintype "passive"))
      (node (ref "SJ35") (pin "1") (pinfunction "1_1") (pintype "passive"))
      (node (ref "SJ36") (pin "2") (pinfunction "2_2") (pintype "passive"))
    )
    (net (code "353") (name "ROW_1_XFUNC") (class "Default")
      (node (ref "D1") (pin "1") (pinfunction "A_1") (pintype "passive"))
      (node (ref "D2") (pin "1") (pinfunction "A_1") (pintype "passive"))
      (node (ref "SJ26") (pin "2") (pinfunction "2_2") (pintype "passive"))
    )
    (net (code "354") (name "ROW_1{MCU}") (class "Default")
      (node (ref "SJ_MCU_ROW1") (pin "2") (pinfunction "2_2") (pintype "passive"))
      (node (ref "U1") (pin "8") (pinfunction "PTE5_8") (pintype "bidirectional"))
    )
    (net (code "355") (name "ROW_2_NUM") (class "Default")
      (node (ref "D41") (pin "1") (pinfunction "A_1") (pintype "passive"))
      (node (ref "D42") (pin "1") (pinfunction "A_1") (pintype "passive"))
      (node (ref "D43") (pin "1") (pinfunction "A_1") (pintype "passive"))
      (node (ref "D44") (pin "1") (pinfunction "A_1") (pintype "passive"))
      (node (ref "SJ37") (pin "1") (pinfunction "1_1") (pintype "passive"))
    )
    (net (code "356") (name "ROW_2_QWERTY") (class "Default")
      (node (ref "D23") (pin "1") (pinfunction "A_1") (pintype "passive"))
      (node (ref "D24") (pin "1") (pinfunction "A_1") (pintype "passive"))
      (node (ref "D25") (pin "1") (pinfunction "A_1") (pintype "passive"))
      (node (ref "D26") (pin "1") (pinfunction "A_1") (pintype "passive"))
      (node (ref "D27") (pin "1") (pinfunction "A_1") (pintype "passive"))
      (node (ref "D28") (pin "1") (pinfunction "A_1") (pintype "passive"))
      (node (ref "D29") (pin "1") (pinfunction "A_1") (pintype "passive"))
      (node (ref "D30") (pin "1") (pinfunction "A_1") (pintype "passive"))
      (node (ref "D31") (pin "1") (pinfunction "A_1") (pintype "passive"))
      (node (ref "D32") (pin "1") (pinfunction "A_1") (pintype "passive"))
      (node (ref "D33") (pin "1") (pinfunction "A_1") (pintype "passive"))
      (node (ref "D34") (pin "1") (pinfunction "A_1") (pintype "passive"))
      (node (ref "D35") (pin "1") (pinfunction "A_1") (pintype "passive"))
      (node (ref "D36") (pin "1") (pinfunction "A_1") (pintype "passive"))
      (node (ref "D37") (pin "1") (pinfunction "A_1") (pintype "passive"))
      (node (ref "D38") (pin "1") (pinfunction "A_1") (pintype "passive"))
      (node (ref "D39") (pin "1") (pinfunction "A_1") (pintype "passive"))
      (node (ref "D40") (pin "1") (pinfunction "A_1") (pintype "passive"))
      (node (ref "SJ27") (pin "1") (pinfunction "1_1") (pintype "passive"))
      (node (ref "SJ37") (pin "2") (pinfunction "2_2") (pintype "passive"))
      (node (ref "SJ_MCU_ROW2") (pin "1") (pinfunction "1_1") (pintype "passive"))
    )
    (net (code "357") (name "ROW_2_XFUNC") (class "Default")
      (node (ref "D21") (pin "1") (pinfunction "A_1") (pintype "passive"))
      (node (ref "D22") (pin "1") (pinfunction "A_1") (pintype "passive"))
      (node (ref "SJ27") (pin "2") (pinfunction "2_2") (pintype "passive"))
    )
    (net (code "358") (name "ROW_2{MCU}") (class "Default")
      (node (ref "SJ_MCU_ROW2") (pin "2") (pinfunction "2_2") (pintype "passive"))
      (node (ref "U1") (pin "9") (pinfunction "PTE6_9") (pintype "bidirectional"))
    )
    (net (code "359") (name "ROW_3_NUM") (class "Default")
      (node (ref "D64") (pin "1") (pinfunction "A_1") (pintype "passive"))
      (node (ref "D65") (pin "1") (pinfunction "A_1") (pintype "passive"))
      (node (ref "D66") (pin "1") (pinfunction "A_1") (pintype "passive"))
      (node (ref "D67") (pin "1") (pinfunction "A_1") (pintype "passive"))
      (node (ref "SJ38") (pin "1") (pinfunction "1_1") (pintype "passive"))
    )
    (net (code "360") (name "ROW_3_QWERTY") (class "Default")
      (node (ref "D47") (pin "1") (pinfunction "A_1") (pintype "passive"))
      (node (ref "D48") (pin "1") (pinfunction "A_1") (pintype "passive"))
      (node (ref "D49") (pin "1") (pinfunction "A_1") (pintype "passive"))
      (node (ref "D50") (pin "1") (pinfunction "A_1") (pintype "passive"))
      (node (ref "D51") (pin "1") (pinfunction "A_1") (pintype "passive"))
      (node (ref "D52") (pin "1") (pinfunction "A_1") (pintype "passive"))
      (node (ref "D53") (pin "1") (pinfunction "A_1") (pintype "passive"))
      (node (ref "D54") (pin "1") (pinfunction "A_1") (pintype "passive"))
      (node (ref "D55") (pin "1") (pinfunction "A_1") (pintype "passive"))
      (node (ref "D56") (pin "1") (pinfunction "A_1") (pintype "passive"))
      (node (ref "D57") (pin "1") (pinfunction "A_1") (pintype "passive"))
      (node (ref "D58") (pin "1") (pinfunction "A_1") (pintype "passive"))
      (node (ref "D59") (pin "1") (pinfunction "A_1") (pintype "passive"))
      (node (ref "D60") (pin "1") (pinfunction "A_1") (pintype "passive"))
      (node (ref "D61") (pin "1") (pinfunction "A_1") (pintype "passive"))
      (node (ref "D62") (pin "1") (pinfunction "A_1") (pintype "passive"))
      (node (ref "D63") (pin "1") (pinfunction "A_1") (pintype "passive"))
      (node (ref "SJ28") (pin "1") (pinfunction "1_1") (pintype "passive"))
      (node (ref "SJ38") (pin "2") (pinfunction "2_2") (pintype "passive"))
      (node (ref "SJ_MCU_ROW3") (pin "1") (pinfunction "1_1") (pintype "passive"))
    )
    (net (code "361") (name "ROW_3_XFUNC") (class "Default")
      (node (ref "D45") (pin "1") (pinfunction "A_1") (pintype "passive"))
      (node (ref "D46") (pin "1") (pinfunction "A_1") (pintype "passive"))
      (node (ref "SJ28") (pin "2") (pinfunction "2_2") (pintype "passive"))
    )
    (net (code "362") (name "ROW_3{MCU}") (class "Default")
      (node (ref "SJ_MCU_ROW3") (pin "2") (pinfunction "2_2") (pintype "passive"))
      (node (ref "U1") (pin "100") (pinfunction "PTB21_100") (pintype "bidirectional"))
    )
    (net (code "363") (name "ROW_4_NUM") (class "Default")
      (node (ref "D87") (pin "1") (pinfunction "A_1") (pintype "passive"))
      (node (ref "D88") (pin "1") (pinfunction "A_1") (pintype "passive"))
      (node (ref "D89") (pin "1") (pinfunction "A_1") (pintype "passive"))
      (node (ref "D90") (pin "1") (pinfunction "A_1") (pintype "passive"))
      (node (ref "SJ39") (pin "1") (pinfunction "1_1") (pintype "passive"))
    )
    (net (code "364") (name "ROW_4_QWERTY") (class "Default")
      (node (ref "D70") (pin "1") (pinfunction "A_1") (pintype "passive"))
      (node (ref "D71") (pin "1") (pinfunction "A_1") (pintype "passive"))
      (node (ref "D72") (pin "1") (pinfunction "A_1") (pintype "passive"))
      (node (ref "D73") (pin "1") (pinfunction "A_1") (pintype "passive"))
      (node (ref "D74") (pin "1") (pinfunction "A_1") (pintype "passive"))
      (node (ref "D75") (pin "1") (pinfunction "A_1") (pintype "passive"))
      (node (ref "D76") (pin "1") (pinfunction "A_1") (pintype "passive"))
      (node (ref "D77") (pin "1") (pinfunction "A_1") (pintype "passive"))
      (node (ref "D78") (pin "1") (pinfunction "A_1") (pintype "passive"))
      (node (ref "D79") (pin "1") (pinfunction "A_1") (pintype "passive"))
      (node (ref "D80") (pin "1") (pinfunction "A_1") (pintype "passive"))
      (node (ref "D81") (pin "1") (pinfunction "A_1") (pintype "passive"))
      (node (ref "D82") (pin "1") (pinfunction "A_1") (pintype "passive"))
      (node (ref "D83") (pin "1") (pinfunction "A_1") (pintype "passive"))
      (node (ref "D84") (pin "1") (pinfunction "A_1") (pintype "passive"))
      (node (ref "D85") (pin "1") (pinfunction "A_1") (pintype "passive"))
      (node (ref "D86") (pin "1") (pinfunction "A_1") (pintype "passive"))
      (node (ref "SJ29") (pin "1") (pinfunction "1_1") (pintype "passive"))
      (node (ref "SJ39") (pin "2") (pinfunction "2_2") (pintype "passive"))
      (node (ref "SJ_MCU_ROW4") (pin "1") (pinfunction "1_1") (pintype "passive"))
    )
    (net (code "365") (name "ROW_4_XFUNC") (class "Default")
      (node (ref "D68") (pin "1") (pinfunction "A_1") (pintype "passive"))
      (node (ref "D69") (pin "1") (pinfunction "A_1") (pintype "passive"))
      (node (ref "SJ29") (pin "2") (pinfunction "2_2") (pintype "passive"))
    )
    (net (code "366") (name "ROW_4{MCU}") (class "Default")
      (node (ref "SJ_MCU_ROW4") (pin "2") (pinfunction "2_2") (pintype "passive"))
      (node (ref "U1") (pin "99") (pinfunction "PTB20_99") (pintype "bidirectional"))
    )
    (net (code "367") (name "ROW_5_NUM") (class "Default")
      (node (ref "D109") (pin "1") (pinfunction "A_1") (pintype "passive"))
      (node (ref "D110") (pin "1") (pinfunction "A_1") (pintype "passive"))
      (node (ref "D111") (pin "1") (pinfunction "A_1") (pintype "passive"))
      (node (ref "D112") (pin "1") (pinfunction "A_1") (pintype "passive"))
      (node (ref "SJ40") (pin "1") (pinfunction "1_1") (pintype "passive"))
    )
    (net (code "368") (name "ROW_5_QWERTY") (class "Default")
      (node (ref "D100") (pin "1") (pinfunction "A_1") (pintype "passive"))
      (node (ref "D101") (pin "1") (pinfunction "A_1") (pintype "passive"))
      (node (ref "D102") (pin "1") (pinfunction "A_1") (pintype "passive"))
      (node (ref "D103") (pin "1") (pinfunction "A_1") (pintype "passive"))
      (node (ref "D104") (pin "1") (pinfunction "A_1") (pintype "passive"))
      (node (ref "D105") (pin "1") (pinfunction "A_1") (pintype "passive"))
      (node (ref "D106") (pin "1") (pinfunction "A_1") (pintype "passive"))
      (node (ref "D107") (pin "1") (pinfunction "A_1") (pintype "passive"))
      (node (ref "D108") (pin "1") (pinfunction "A_1") (pintype "passive"))
      (node (ref "D93") (pin "1") (pinfunction "A_1") (pintype "passive"))
      (node (ref "D94") (pin "1") (pinfunction "A_1") (pintype "passive"))
      (node (ref "D95") (pin "1") (pinfunction "A_1") (pintype "passive"))
      (node (ref "D96") (pin "1") (pinfunction "A_1") (pintype "passive"))
      (node (ref "D97") (pin "1") (pinfunction "A_1") (pintype "passive"))
      (node (ref "D98") (pin "1") (pinfunction "A_1") (pintype "passive"))
      (node (ref "D99") (pin "1") (pinfunction "A_1") (pintype "passive"))
      (node (ref "SJ30") (pin "1") (pinfunction "1_1") (pintype "passive"))
      (node (ref "SJ40") (pin "2") (pinfunction "2_2") (pintype "passive"))
      (node (ref "SJ_MCU_ROW5") (pin "1") (pinfunction "1_1") (pintype "passive"))
    )
    (net (code "369") (name "ROW_5_XFUNC") (class "Default")
      (node (ref "D91") (pin "1") (pinfunction "A_1") (pintype "passive"))
      (node (ref "D92") (pin "1") (pinfunction "A_1") (pintype "passive"))
      (node (ref "SJ30") (pin "2") (pinfunction "2_2") (pintype "passive"))
    )
    (net (code "370") (name "ROW_5{MCU}") (class "Default")
      (node (ref "SJ_MCU_ROW5") (pin "2") (pinfunction "2_2") (pintype "passive"))
      (node (ref "U1") (pin "87") (pinfunction "PTB6_87") (pintype "bidirectional"))
    )
    (net (code "371") (name "ROW_6_NUM") (class "Default")
      (node (ref "D130") (pin "1") (pinfunction "A_1") (pintype "passive"))
      (node (ref "D131") (pin "1") (pinfunction "A_1") (pintype "passive"))
      (node (ref "D132") (pin "1") (pinfunction "A_1") (pintype "passive"))
      (node (ref "SJ41") (pin "1") (pinfunction "1_1") (pintype "passive"))
    )
    (net (code "372") (name "ROW_6_QWERTY") (class "Default")
      (node (ref "D115") (pin "1") (pinfunction "A_1") (pintype "passive"))
      (node (ref "D116") (pin "1") (pinfunction "A_1") (pintype "passive"))
      (node (ref "D117") (pin "1") (pinfunction "A_1") (pintype "passive"))
      (node (ref "D118") (pin "1") (pinfunction "A_1") (pintype "passive"))
      (node (ref "D119") (pin "1") (pinfunction "A_1") (pintype "passive"))
      (node (ref "D120") (pin "1") (pinfunction "A_1") (pintype "passive"))
      (node (ref "D121") (pin "1") (pinfunction "A_1") (pintype "passive"))
      (node (ref "D122") (pin "1") (pinfunction "A_1") (pintype "passive"))
      (node (ref "D123") (pin "1") (pinfunction "A_1") (pintype "passive"))
      (node (ref "D124") (pin "1") (pinfunction "A_1") (pintype "passive"))
      (node (ref "D125") (pin "1") (pinfunction "A_1") (pintype "passive"))
      (node (ref "D126") (pin "1") (pinfunction "A_1") (pintype "passive"))
      (node (ref "D127") (pin "1") (pinfunction "A_1") (pintype "passive"))
      (node (ref "D128") (pin "1") (pinfunction "A_1") (pintype "passive"))
      (node (ref "D129") (pin "1") (pinfunction "A_1") (pintype "passive"))
      (node (ref "SJ31") (pin "1") (pinfunction "1_1") (pintype "passive"))
      (node (ref "SJ41") (pin "2") (pinfunction "2_2") (pintype "passive"))
      (node (ref "SJ_MCU_ROW6") (pin "1") (pinfunction "1_1") (pintype "passive"))
    )
    (net (code "373") (name "ROW_6_XFUNC") (class "Default")
      (node (ref "D113") (pin "1") (pinfunction "A_1") (pintype "passive"))
      (node (ref "D114") (pin "1") (pinfunction "A_1") (pintype "passive"))
      (node (ref "SJ31") (pin "2") (pinfunction "2_2") (pintype "passive"))
    )
    (net (code "374") (name "ROW_6{MCU}") (class "Default")
      (node (ref "SJ_MCU_ROW6") (pin "2") (pinfunction "2_2") (pintype "passive"))
      (node (ref "U1") (pin "85") (pinfunction "PTB4_85") (pintype "bidirectional"))
    )
    (net (code "375") (name "ROW_7_NUM") (class "Default")
      (node (ref "D146") (pin "1") (pinfunction "A_1") (pintype "passive"))
      (node (ref "D147") (pin "1") (pinfunction "A_1") (pintype "passive"))
      (node (ref "D148") (pin "1") (pinfunction "A_1") (pintype "passive"))
      (node (ref "D149") (pin "1") (pinfunction "A_1") (pintype "passive"))
      (node (ref "SJ42") (pin "1") (pinfunction "1_1") (pintype "passive"))
    )
    (net (code "376") (name "ROW_7_QWERTY") (class "Default")
      (node (ref "D135") (pin "1") (pinfunction "A_1") (pintype "passive"))
      (node (ref "D136") (pin "1") (pinfunction "A_1") (pintype "passive"))
      (node (ref "D137") (pin "1") (pinfunction "A_1") (pintype "passive"))
      (node (ref "D138") (pin "1") (pinfunction "A_1") (pintype "passive"))
      (node (ref "D139") (pin "1") (pinfunction "A_1") (pintype "passive"))
      (node (ref "D140") (pin "1") (pinfunction "A_1") (pintype "passive"))
      (node (ref "D141") (pin "1") (pinfunction "A_1") (pintype "passive"))
      (node (ref "D142") (pin "1") (pinfunction "A_1") (pintype "passive"))
      (node (ref "D143") (pin "1") (pinfunction "A_1") (pintype "passive"))
      (node (ref "D144") (pin "1") (pinfunction "A_1") (pintype "passive"))
      (node (ref "D145") (pin "1") (pinfunction "A_1") (pintype "passive"))
      (node (ref "SJ32") (pin "1") (pinfunction "1_1") (pintype "passive"))
      (node (ref "SJ42") (pin "2") (pinfunction "2_2") (pintype "passive"))
      (node (ref "SJ_MCU_ROW7") (pin "1") (pinfunction "1_1") (pintype "passive"))
    )
    (net (code "377") (name "ROW_7_XFUNC") (class "Default")
      (node (ref "D133") (pin "1") (pinfunction "A_1") (pintype "passive"))
      (node (ref "D134") (pin "1") (pinfunction "A_1") (pintype "passive"))
      (node (ref "SJ32") (pin "2") (pinfunction "2_2") (pintype "passive"))
    )
    (net (code "378") (name "ROW_7{MCU}") (class "Default")
      (node (ref "SJ_MCU_ROW7") (pin "2") (pinfunction "2_2") (pintype "passive"))
      (node (ref "U1") (pin "84") (pinfunction "PTB3_84") (pintype "bidirectional"))
    )
    (net (code "379") (name "SDB_LED_CTRL") (class "Default")
      (node (ref "R8") (pin "1") (pinfunction "1_1") (pintype "passive"))
      (node (ref "U1") (pin "97") (pinfunction "PTB18_97") (pintype "bidirectional"))
      (node (ref "U3") (pin "46") (pinfunction "SDB_46") (pintype "bidirectional"))
    )
    (net (code "380") (name "SPI0_SCK") (class "Default")
      (node (ref "J3") (pin "10") (pinfunction "P$10_10") (pintype "bidirectional"))
      (node (ref "U1") (pin "110") (pinfunction "PTC5/LLWU_P9_110") (pintype "bidirectional"))
    )
    (net (code "381") (name "SPI0_SIN") (class "Default")
      (node (ref "J3") (pin "8") (pinfunction "P$8_8") (pintype "bidirectional"))
      (node (ref "U1") (pin "112") (pinfunction "PTC7_112") (pintype "bidirectional"))
    )
    (net (code "382") (name "SPI0_SOUT") (class "Default")
      (node (ref "J3") (pin "9") (pinfunction "P$9_9") (pintype "bidirectional"))
      (node (ref "U1") (pin "111") (pinfunction "PTC6/LLWU_P10_111") (pintype "bidirectional"))
    )
    (net (code "383") (name "UART2_RX") (class "Default")
      (node (ref "J3") (pin "4") (pinfunction "P$4_4") (pintype "bidirectional"))
      (node (ref "U1") (pin "129") (pinfunction "PTD2/LLWU_P13_129") (pintype "bidirectional"))
    )
    (net (code "384") (name "UART2_TX") (class "Default")
      (node (ref "J3") (pin "3") (pinfunction "P$3_3") (pintype "bidirectional"))
      (node (ref "U1") (pin "130") (pinfunction "PTD3_130") (pintype "bidirectional"))
    )
    (net (code "385") (name "UART3_RX") (class "Default")
      (node (ref "SV1") (pin "3") (pinfunction "3_3") (pintype "passive"))
      (node (ref "U1") (pin "91") (pinfunction "PTB10_91") (pintype "bidirectional"))
    )
    (net (code "386") (name "UART3_TX") (class "Default")
      (node (ref "SV1") (pin "2") (pinfunction "2_2") (pintype "passive"))
      (node (ref "U1") (pin "92") (pinfunction "PTB11_92") (pintype "bidirectional"))
    )
    (net (code "387") (name "USB_MCU_N") (class "Default")
      (node (ref "R3") (pin "2") (pinfunction "2_2") (pintype "passive"))
      (node (ref "U1") (pin "20") (pinfunction "USB0_DM_20") (pintype "bidirectional"))
    )
    (net (code "388") (name "USB_MCU_P") (class "Default")
      (node (ref "R2") (pin "2") (pinfunction "2_2") (pintype "passive"))
      (node (ref "U1") (pin "19") (pinfunction "USB0_DP_19") (pintype "bidirectional"))
    )
    (net (code "389") (name "USB_N") (class "Default")
      (node (ref "J1") (pin "A7") (pinfunction "DN1_A7") (pintype "bidirectional"))
      (node (ref "J1") (pin "B7") (pinfunction "DN2_B7") (pintype "bidirectional"))
      (node (ref "R3") (pin "1") (pinfunction "1_1") (pintype "passive"))
      (node (ref "TVS2") (pin "2") (pinfunction "2_2") (pintype "bidirectional"))
    )
    (net (code "390") (name "USB_P") (class "Default")
      (node (ref "J1") (pin "A6") (pinfunction "DP1_A6") (pintype "bidirectional"))
      (node (ref "J1") (pin "B6") (pinfunction "DP2_B6") (pintype "bidirectional"))
      (node (ref "R2") (pin "1") (pinfunction "1_1") (pintype "passive"))
      (node (ref "TVS3") (pin "2") (pinfunction "2_2") (pintype "bidirectional"))
    )
    (net (code "391") (name "VBUS") (class "Default")
      (node (ref "J1") (pin "A4_B9") (pinfunction "VBUS_A4_B9") (pintype "power_in"))
      (node (ref "J1") (pin "B4_A9") (pinfunction "VBUS_B4_A9") (pintype "power_in"))
      (node (ref "L1") (pin "1") (pinfunction "1_1") (pintype "bidirectional"))
      (node (ref "TVS1") (pin "1") (pinfunction "1_1") (pintype "bidirectional"))
    )
    (net (code "392") (name "VDD_3V3") (class "Default")
      (node (ref "C16") (pin "1") (pinfunction "1_1") (pintype "passive"))
      (node (ref "C2") (pin "1") (pinfunction "1_1") (pintype "passive"))
      (node (ref "C3") (pin "1") (pinfunction "1_1") (pintype "passive"))
      (node (ref "C4") (pin "1") (pinfunction "1_1") (pintype "passive"))
      (node (ref "C5") (pin "2") (pinfunction "2_2") (pintype "passive"))
      (node (ref "C6") (pin "2") (pinfunction "2_2") (pintype "passive"))
      (node (ref "C7") (pin "2") (pinfunction "2_2") (pintype "passive"))
      (node (ref "C8") (pin "1") (pinfunction "1_1") (pintype "passive"))
      (node (ref "C9") (pin "2") (pinfunction "2_2") (pintype "passive"))
      (node (ref "J2") (pin "1") (pinfunction "VCC_1") (pintype "bidirectional"))
      (node (ref "J3") (pin "1") (pinfunction "P$1_1") (pintype "bidirectional"))
      (node (ref "R1") (pin "2") (pinfunction "2_2") (pintype "passive"))
      (node (ref "R11") (pin "2") (pinfunction "2_2") (pintype "passive"))
      (node (ref "R5") (pin "1") (pinfunction "1_1") (pintype "passive"))
      (node (ref "R6") (pin "1") (pinfunction "1_1") (pintype "passive"))
      (node (ref "R7") (pin "1") (pinfunction "1_1") (pintype "passive"))
      (node (ref "SJ1") (pin "2") (pinfunction "2_2") (pintype "passive"))
      (node (ref "SV1") (pin "1") (pinfunction "1_1") (pintype "passive"))
      (node (ref "U1") (pin "108") (pinfunction "VDD_3_108") (pintype "power_in"))
      (node (ref "U1") (pin "122") (pinfunction "VDD_4_122") (pintype "power_in"))
      (node (ref "U1") (pin "135") (pinfunction "VDD_135") (pintype "power_in"))
      (node (ref "U1") (pin "16") (pinfunction "VDD_3_16") (pintype "power_in"))
      (node (ref "U1") (pin "31") (pinfunction "VDDA_31") (pintype "power_in"))
      (node (ref "U1") (pin "32") (pinfunction "VREFH_32") (pintype "power_in"))
      (node (ref "U1") (pin "42") (pinfunction "VBAT_42") (pintype "power_in"))
      (node (ref "U1") (pin "43") (pinfunction "VDD_4_43") (pintype "power_in"))
      (node (ref "U1") (pin "5") (pinfunction "VDD_2_5") (pintype "power_in"))
      (node (ref "U1") (pin "56") (pinfunction "VDD_5_56") (pintype "power_in"))
      (node (ref "U1") (pin "70") (pinfunction "VDD_70") (pintype "power_in"))
      (node (ref "U1") (pin "94") (pinfunction "VDD_2_94") (pintype "power_in"))
      (node (ref "U3") (pin "39") (pinfunction "VIO_39") (pintype "bidirectional"))
      (node (ref "VDD_3V3") (pin "TP") (pinfunction "TP_TP") (pintype "input"))
    )
    (net (code "393") (name "VLDO_5V") (class "Default")
      (node (ref "C17") (pin "1") (pinfunction "1_1") (pintype "passive"))
      (node (ref "C18") (pin "1") (pinfunction "1_1") (pintype "passive"))
      (node (ref "C19") (pin "1") (pinfunction "1_1") (pintype "passive"))
      (node (ref "C20") (pin "1") (pinfunction "1_1") (pintype "passive"))
      (node (ref "C21") (pin "1") (pinfunction "1_1") (pintype "passive"))
      (node (ref "C22") (pin "1") (pinfunction "1_1") (pintype "passive"))
      (node (ref "C23") (pin "+") (pinfunction "+_+") (pintype "passive"))
      (node (ref "D154") (pin "2") (pinfunction "CATHODE_2") (pintype "bidirectional"))
      (node (ref "U2") (pin "5") (pinfunction "EN_5") (pintype "bidirectional"))
      (node (ref "U2") (pin "8") (pinfunction "VIN_8") (pintype "bidirectional"))
      (node (ref "U3") (pin "20") (pinfunction "PVCC_20") (pintype "bidirectional"))
      (node (ref "U3") (pin "29") (pinfunction "PVCC_2_29") (pintype "bidirectional"))
      (node (ref "U3") (pin "37") (pinfunction "AVCC_37") (pintype "bidirectional"))
      (node (ref "U3") (pin "38") (pinfunction "DVCC_38") (pintype "bidirectional"))
      (node (ref "VLDO_5V") (pin "TP") (pinfunction "TP_TP") (pintype "input"))
    )
    (net (code "394") (name "VLDO_33") (class "Default")
      (node (ref "C14") (pin "1") (pinfunction "1_1") (pintype "passive"))
      (node (ref "SJ1") (pin "1") (pinfunction "1_1") (pintype "passive"))
      (node (ref "U2") (pin "1") (pinfunction "VOUT_1") (pintype "bidirectional"))
    )
    (net (code "395") (name "VOUT_33") (class "Default")
      (node (ref "C12") (pin "1") (pinfunction "1_1") (pintype "passive"))
      (node (ref "SJ1") (pin "3") (pinfunction "3_3") (pintype "passive"))
      (node (ref "U1") (pin "21") (pinfunction "VOUT33_21") (pintype "power_in"))
    )
    (net (code "396") (name "VSYS_5V") (class "Default")
      (node (ref "C13") (pin "1") (pinfunction "1_1") (pintype "passive"))
      (node (ref "D154") (pin "1") (pinfunction "ANODE_1") (pintype "bidirectional"))
      (node (ref "L1") (pin "2") (pinfunction "2_2") (pintype "bidirectional"))
      (node (ref "U1") (pin "22") (pinfunction "VREGIN_22") (pintype "power_in"))
    )
    (net (code "397") (name "XTAL") (class "Default")
      (node (ref "C10") (pin "2") (pinfunction "2_2") (pintype "passive"))
      (node (ref "U1") (pin "73") (pinfunction "PTA19_73") (pintype "bidirectional"))
      (node (ref "Y1") (pin "1") (pinfunction "1_1") (pintype "passive"))
    )
    (net (code "398") (name "XTAL32") (class "Default")
      (node (ref "C25") (pin "1") (pinfunction "1_1") (pintype "passive"))
      (node (ref "U1") (pin "40") (pinfunction "XTAL32_40") (pintype "passive"))
      (node (ref "Y2") (pin "2") (pinfunction "2_2") (pintype "passive"))
    )
    (net (code "399") (name "unconnected-(J1-SBU1-PadA8)") (class "Default")
      (node (ref "J1") (pin "A8") (pinfunction "SBU1_A8") (pintype "bidirectional"))
    )
    (net (code "400") (name "unconnected-(J1-SBU2-PadB8)") (class "Default")
      (node (ref "J1") (pin "B8") (pinfunction "SBU2_B8") (pintype "bidirectional"))
    )
    (net (code "401") (name "unconnected-(J2-GNDDETECT-Pad9)") (class "Default")
      (node (ref "J2") (pin "9") (pinfunction "GNDDETECT_9") (pintype "bidirectional"))
    )
    (net (code "402") (name "unconnected-(J2-KEY-Pad7)") (class "Default")
      (node (ref "J2") (pin "7") (pinfunction "KEY_7") (pintype "bidirectional"))
    )
    (net (code "403") (name "unconnected-(U1A-ADC0_DM0{slash}ADC1_DM3-Pad28)") (class "Default")
      (node (ref "U1") (pin "28") (pinfunction "ADC0_DM0/ADC1_DM3_28") (pintype "bidirectional"))
    )
    (net (code "404") (name "unconnected-(U1A-ADC0_DM1-Pad24)") (class "Default")
      (node (ref "U1") (pin "24") (pinfunction "ADC0_DM1_24") (pintype "bidirectional"))
    )
    (net (code "405") (name "unconnected-(U1A-ADC0_DP0{slash}ADC1_DP3-Pad27)") (class "Default")
      (node (ref "U1") (pin "27") (pinfunction "ADC0_DP0/ADC1_DP3_27") (pintype "bidirectional"))
    )
    (net (code "406") (name "unconnected-(U1A-ADC0_DP1-Pad23)") (class "Default")
      (node (ref "U1") (pin "23") (pinfunction "ADC0_DP1_23") (pintype "bidirectional"))
    )
    (net (code "407") (name "unconnected-(U1A-ADC0_SE16{slash}CMP1_IN2{slash}ADC0_SE21-Pad36)") (class "Default")
      (node (ref "U1") (pin "36") (pinfunction "ADC0_SE16/CMP1_IN2/ADC0_SE21_36") (pintype "bidirectional"))
    )
    (net (code "408") (name "unconnected-(U1A-ADC1_DM0{slash}ADC0_DM3-Pad30)") (class "Default")
      (node (ref "U1") (pin "30") (pinfunction "ADC1_DM0/ADC0_DM3_30") (pintype "bidirectional"))
    )
    (net (code "409") (name "unconnected-(U1A-ADC1_DM1-Pad26)") (class "Default")
      (node (ref "U1") (pin "26") (pinfunction "ADC1_DM1_26") (pintype "bidirectional"))
    )
    (net (code "410") (name "unconnected-(U1A-ADC1_DP0{slash}ADC0_DP3-Pad29)") (class "Default")
      (node (ref "U1") (pin "29") (pinfunction "ADC1_DP0/ADC0_DP3_29") (pintype "bidirectional"))
    )
    (net (code "411") (name "unconnected-(U1A-ADC1_DP1-Pad25)") (class "Default")
      (node (ref "U1") (pin "25") (pinfunction "ADC1_DP1_25") (pintype "bidirectional"))
    )
    (net (code "412") (name "unconnected-(U1A-ADC1_SE16{slash}CMP2_IN2{slash}ADC0_SE22-Pad35)") (class "Default")
      (node (ref "U1") (pin "35") (pinfunction "ADC1_SE16/CMP2_IN2/ADC0_SE22_35") (pintype "bidirectional"))
    )
    (net (code "413") (name "unconnected-(U1A-DAC0_OUT{slash}CMP1_IN3{slash}ADC0_SE23-Pad38)") (class "Default")
      (node (ref "U1") (pin "38") (pinfunction "DAC0_OUT/CMP1_IN3/ADC0_SE23_38") (pintype "bidirectional"))
    )
    (net (code "414") (name "unconnected-(U1A-DAC1_OUT{slash}CMP0_IN4{slash}CMP2_IN3{slash}ADC1_SE23-Pad39)") (class "Default")
      (node (ref "U1") (pin "39") (pinfunction "DAC1_OUT/CMP0_IN4/CMP2_IN3/ADC1_SE23_39") (pintype "bidirectional"))
    )
    (net (code "415") (name "unconnected-(U1A-DAC1_OUT{slash}CMP1_IN5{slash}CMP0_IN5{slash}ADC1_SE18-Pad37)") (class "Default")
      (node (ref "U1") (pin "37") (pinfunction "DAC1_OUT/CMP1_IN5/CMP0_IN5/ADC1_SE18_37") (pintype "bidirectional"))
    )
    (net (code "416") (name "unconnected-(U1A-PTA8-Pad60)") (class "Default")
      (node (ref "U1") (pin "60") (pinfunction "PTA8_60") (pintype "bidirectional"))
    )
    (net (code "417") (name "unconnected-(U1A-PTA9-Pad61)") (class "Default")
      (node (ref "U1") (pin "61") (pinfunction "PTA9_61") (pintype "bidirectional"))
    )
    (net (code "418") (name "unconnected-(U1A-PTA10-Pad62)") (class "Default")
      (node (ref "U1") (pin "62") (pinfunction "PTA10_62") (pintype "bidirectional"))
    )
    (net (code "419") (name "unconnected-(U1A-PTA11-Pad63)") (class "Default")
      (node (ref "U1") (pin "63") (pinfunction "PTA11_63") (pintype "bidirectional"))
    )
    (net (code "420") (name "unconnected-(U1A-PTA13{slash}LLWU_P4-Pad65)") (class "Default")
      (node (ref "U1") (pin "65") (pinfunction "PTA13/LLWU_P4_65") (pintype "bidirectional"))
    )
    (net (code "421") (name "unconnected-(U1A-PTA15-Pad67)") (class "Default")
      (node (ref "U1") (pin "67") (pinfunction "PTA15_67") (pintype "bidirectional"))
    )
    (net (code "422") (name "unconnected-(U1A-PTA16-Pad68)") (class "Default")
      (node (ref "U1") (pin "68") (pinfunction "PTA16_68") (pintype "bidirectional"))
    )
    (net (code "423") (name "unconnected-(U1A-PTA17-Pad69)") (class "Default")
      (node (ref "U1") (pin "69") (pinfunction "PTA17_69") (pintype "bidirectional"))
    )
    (net (code "424") (name "unconnected-(U1A-PTE7-Pad10)") (class "Default")
      (node (ref "U1") (pin "10") (pinfunction "PTE7_10") (pintype "bidirectional"))
    )
    (net (code "425") (name "unconnected-(U1A-PTE8-Pad11)") (class "Default")
      (node (ref "U1") (pin "11") (pinfunction "PTE8_11") (pintype "bidirectional"))
    )
    (net (code "426") (name "unconnected-(U1A-PTE9-Pad12)") (class "Default")
      (node (ref "U1") (pin "12") (pinfunction "PTE9_12") (pintype "bidirectional"))
    )
    (net (code "427") (name "unconnected-(U1A-PTE10-Pad13)") (class "Default")
      (node (ref "U1") (pin "13") (pinfunction "PTE10_13") (pintype "bidirectional"))
    )
    (net (code "428") (name "unconnected-(U1A-PTE11-Pad14)") (class "Default")
      (node (ref "U1") (pin "14") (pinfunction "PTE11_14") (pintype "bidirectional"))
    )
    (net (code "429") (name "unconnected-(U1A-PTE12-Pad15)") (class "Default")
      (node (ref "U1") (pin "15") (pinfunction "PTE12_15") (pintype "bidirectional"))
    )
    (net (code "430") (name "unconnected-(U1A-PTE24-Pad45)") (class "Default")
      (node (ref "U1") (pin "45") (pinfunction "PTE24_45") (pintype "bidirectional"))
    )
    (net (code "431") (name "unconnected-(U1A-PTE25-Pad46)") (class "Default")
      (node (ref "U1") (pin "46") (pinfunction "PTE25_46") (pintype "bidirectional"))
    )
    (net (code "432") (name "unconnected-(U1A-PTE28-Pad49)") (class "Default")
      (node (ref "U1") (pin "49") (pinfunction "PTE28_49") (pintype "bidirectional"))
    )
    (net (code "433") (name "unconnected-(U1B-PTA24-Pad75)") (class "Default")
      (node (ref "U1") (pin "75") (pinfunction "PTA24_75") (pintype "bidirectional"))
    )
    (net (code "434") (name "unconnected-(U1B-PTA25-Pad76)") (class "Default")
      (node (ref "U1") (pin "76") (pinfunction "PTA25_76") (pintype "bidirectional"))
    )
    (net (code "435") (name "unconnected-(U1B-PTA26-Pad77)") (class "Default")
      (node (ref "U1") (pin "77") (pinfunction "PTA26_77") (pintype "bidirectional"))
    )
    (net (code "436") (name "unconnected-(U1B-PTA27-Pad78)") (class "Default")
      (node (ref "U1") (pin "78") (pinfunction "PTA27_78") (pintype "bidirectional"))
    )
    (net (code "437") (name "unconnected-(U1B-PTA28-Pad79)") (class "Default")
      (node (ref "U1") (pin "79") (pinfunction "PTA28_79") (pintype "bidirectional"))
    )
    (net (code "438") (name "unconnected-(U1B-PTA29-Pad80)") (class "Default")
      (node (ref "U1") (pin "80") (pinfunction "PTA29_80") (pintype "bidirectional"))
    )
    (net (code "439") (name "unconnected-(U1B-PTB0{slash}LLWU_P5-Pad81)") (class "Default")
      (node (ref "U1") (pin "81") (pinfunction "PTB0/LLWU_P5_81") (pintype "bidirectional"))
    )
    (net (code "440") (name "unconnected-(U1B-PTB5-Pad86)") (class "Default")
      (node (ref "U1") (pin "86") (pinfunction "PTB5_86") (pintype "bidirectional"))
    )
    (net (code "441") (name "unconnected-(U1B-PTB7-Pad88)") (class "Default")
      (node (ref "U1") (pin "88") (pinfunction "PTB7_88") (pintype "bidirectional"))
    )
    (net (code "442") (name "unconnected-(U1B-PTB8-Pad89)") (class "Default")
      (node (ref "U1") (pin "89") (pinfunction "PTB8_89") (pintype "bidirectional"))
    )
    (net (code "443") (name "unconnected-(U1B-PTB9-Pad90)") (class "Default")
      (node (ref "U1") (pin "90") (pinfunction "PTB9_90") (pintype "bidirectional"))
    )
    (net (code "444") (name "unconnected-(U1B-PTB16-Pad95)") (class "Default")
      (node (ref "U1") (pin "95") (pinfunction "PTB16_95") (pintype "bidirectional"))
    )
    (net (code "445") (name "unconnected-(U1B-PTB19-Pad98)") (class "Default")
      (node (ref "U1") (pin "98") (pinfunction "PTB19_98") (pintype "bidirectional"))
    )
    (net (code "446") (name "unconnected-(U1B-PTB22-Pad101)") (class "Default")
      (node (ref "U1") (pin "101") (pinfunction "PTB22_101") (pintype "bidirectional"))
    )
    (net (code "447") (name "unconnected-(U1B-PTB23-Pad102)") (class "Default")
      (node (ref "U1") (pin "102") (pinfunction "PTB23_102") (pintype "bidirectional"))
    )
    (net (code "448") (name "unconnected-(U1B-PTC0-Pad103)") (class "Default")
      (node (ref "U1") (pin "103") (pinfunction "PTC0_103") (pintype "bidirectional"))
    )
    (net (code "449") (name "unconnected-(U1B-PTC1{slash}LLWU_P6-Pad104)") (class "Default")
      (node (ref "U1") (pin "104") (pinfunction "PTC1/LLWU_P6_104") (pintype "bidirectional"))
    )
    (net (code "450") (name "unconnected-(U1B-PTC2-Pad105)") (class "Default")
      (node (ref "U1") (pin "105") (pinfunction "PTC2_105") (pintype "bidirectional"))
    )
    (net (code "451") (name "unconnected-(U1B-PTC3{slash}LLWU_P7-Pad106)") (class "Default")
      (node (ref "U1") (pin "106") (pinfunction "PTC3/LLWU_P7_106") (pintype "bidirectional"))
    )
    (net (code "452") (name "unconnected-(U1B-PTC4{slash}LLWU_P8-Pad109)") (class "Default")
      (node (ref "U1") (pin "109") (pinfunction "PTC4/LLWU_P8_109") (pintype "bidirectional"))
    )
    (net (code "453") (name "unconnected-(U1B-PTC9-Pad114)") (class "Default")
      (node (ref "U1") (pin "114") (pinfunction "PTC9_114") (pintype "bidirectional"))
    )
    (net (code "454") (name "unconnected-(U1B-PTC12-Pad117)") (class "Default")
      (node (ref "U1") (pin "117") (pinfunction "PTC12_117") (pintype "bidirectional"))
    )
    (net (code "455") (name "unconnected-(U1B-PTC13-Pad118)") (class "Default")
      (node (ref "U1") (pin "118") (pinfunction "PTC13_118") (pintype "bidirectional"))
    )
    (net (code "456") (name "unconnected-(U1B-PTC14-Pad119)") (class "Default")
      (node (ref "U1") (pin "119") (pinfunction "PTC14_119") (pintype "bidirectional"))
    )
    (net (code "457") (name "unconnected-(U1B-PTC15-Pad120)") (class "Default")
      (node (ref "U1") (pin "120") (pinfunction "PTC15_120") (pintype "bidirectional"))
    )
    (net (code "458") (name "unconnected-(U1B-PTC16-Pad123)") (class "Default")
      (node (ref "U1") (pin "123") (pinfunction "PTC16_123") (pintype "bidirectional"))
    )
    (net (code "459") (name "unconnected-(U1B-PTC17-Pad124)") (class "Default")
      (node (ref "U1") (pin "124") (pinfunction "PTC17_124") (pintype "bidirectional"))
    )
    (net (code "460") (name "unconnected-(U1B-PTC18-Pad125)") (class "Default")
      (node (ref "U1") (pin "125") (pinfunction "PTC18_125") (pintype "bidirectional"))
    )
    (net (code "461") (name "unconnected-(U1B-PTC19-Pad126)") (class "Default")
      (node (ref "U1") (pin "126") (pinfunction "PTC19_126") (pintype "bidirectional"))
    )
    (net (code "462") (name "unconnected-(U1B-PTD0{slash}LLWU_P12-Pad127)") (class "Default")
      (node (ref "U1") (pin "127") (pinfunction "PTD0/LLWU_P12_127") (pintype "bidirectional"))
    )
    (net (code "463") (name "unconnected-(U1B-PTD1-Pad128)") (class "Default")
      (node (ref "U1") (pin "128") (pinfunction "PTD1_128") (pintype "bidirectional"))
    )
    (net (code "464") (name "unconnected-(U2-NC-Pad2)") (class "Default")
      (node (ref "U2") (pin "2") (pinfunction "NC_2") (pintype "no_connect"))
    )
    (net (code "465") (name "unconnected-(U2-NC_2-Pad3)") (class "Default")
      (node (ref "U2") (pin "3") (pinfunction "NC_2_3") (pintype "no_connect"))
    )
    (net (code "466") (name "unconnected-(U2-NC_3-Pad4)") (class "Default")
      (node (ref "U2") (pin "4") (pinfunction "NC_3_4") (pintype "no_connect"))
    )
    (net (code "467") (name "unconnected-(U3-CS15-Pad32)") (class "Default")
      (node (ref "U3") (pin "32") (pinfunction "CS15_32") (pintype "bidirectional"))
    )
    (net (code "468") (name "unconnected-(U3-CS16-Pad33)") (class "Default")
      (node (ref "U3") (pin "33") (pinfunction "CS16_33") (pintype "bidirectional"))
    )
    (net (code "469") (name "unconnected-(U3-NC-Pad1)") (class "Default")
      (node (ref "U3") (pin "1") (pinfunction "NC_1") (pintype "no_connect"))
    )
    (net (code "470") (name "unconnected-(U3-NC_2-Pad36)") (class "Default")
      (node (ref "U3") (pin "36") (pinfunction "NC_2_36") (pintype "no_connect"))
    )
    (net (code "471") (name "unconnected-(U3-SYNC-Pad40)") (class "Default")
      (node (ref "U3") (pin "40") (pinfunction "SYNC_40") (pintype "bidirectional"))
    )
  )
)
